# ME461_F28379D.net
KiCad netlist of a schematic drawn in EAGLE
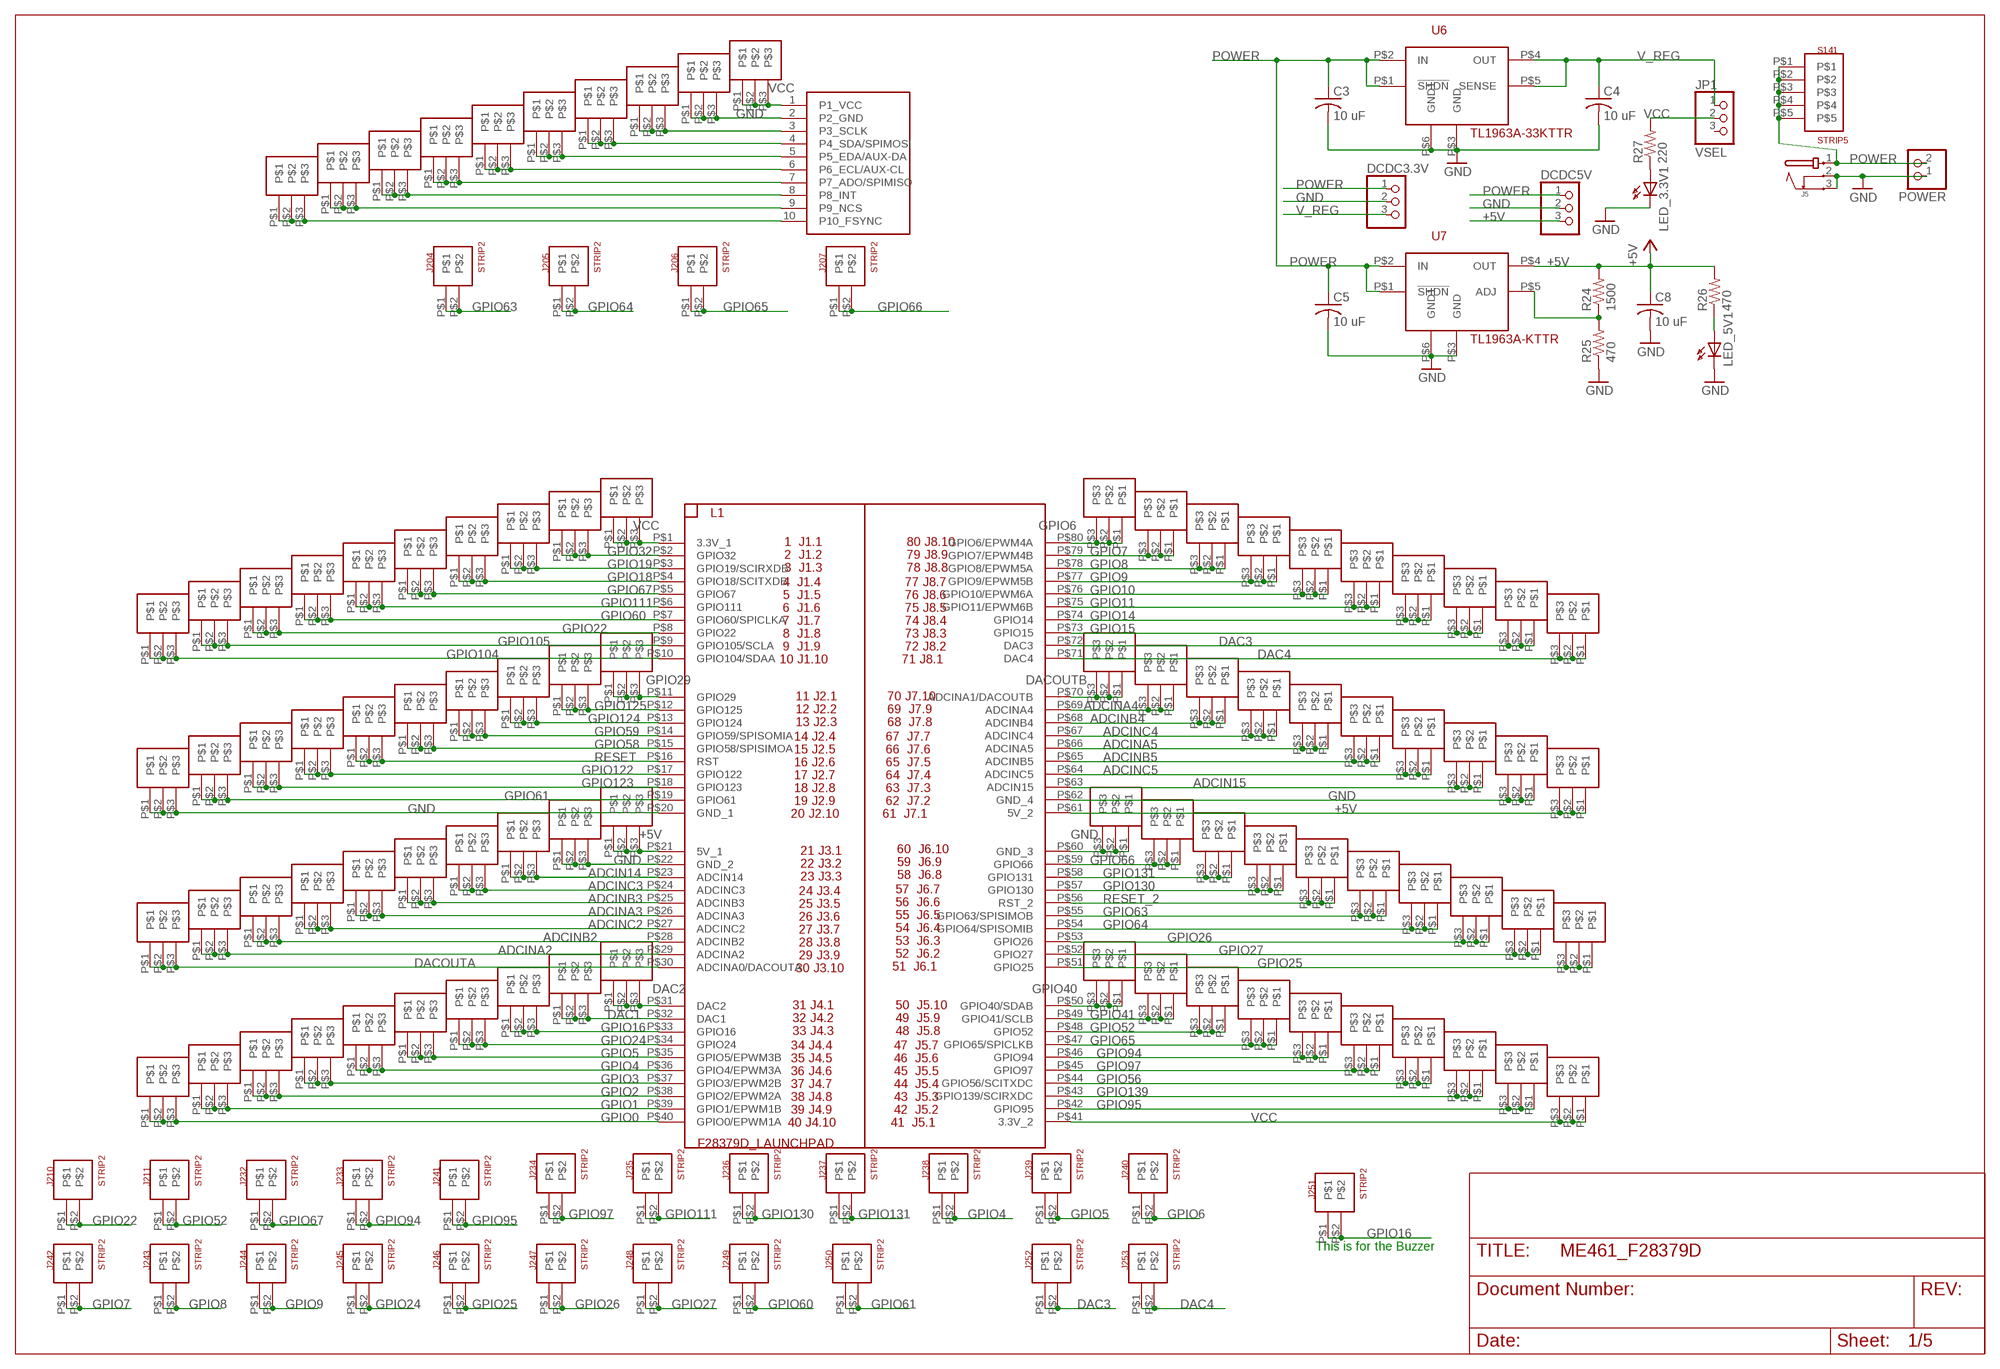
[diagram p0: schematic, sheet 1]
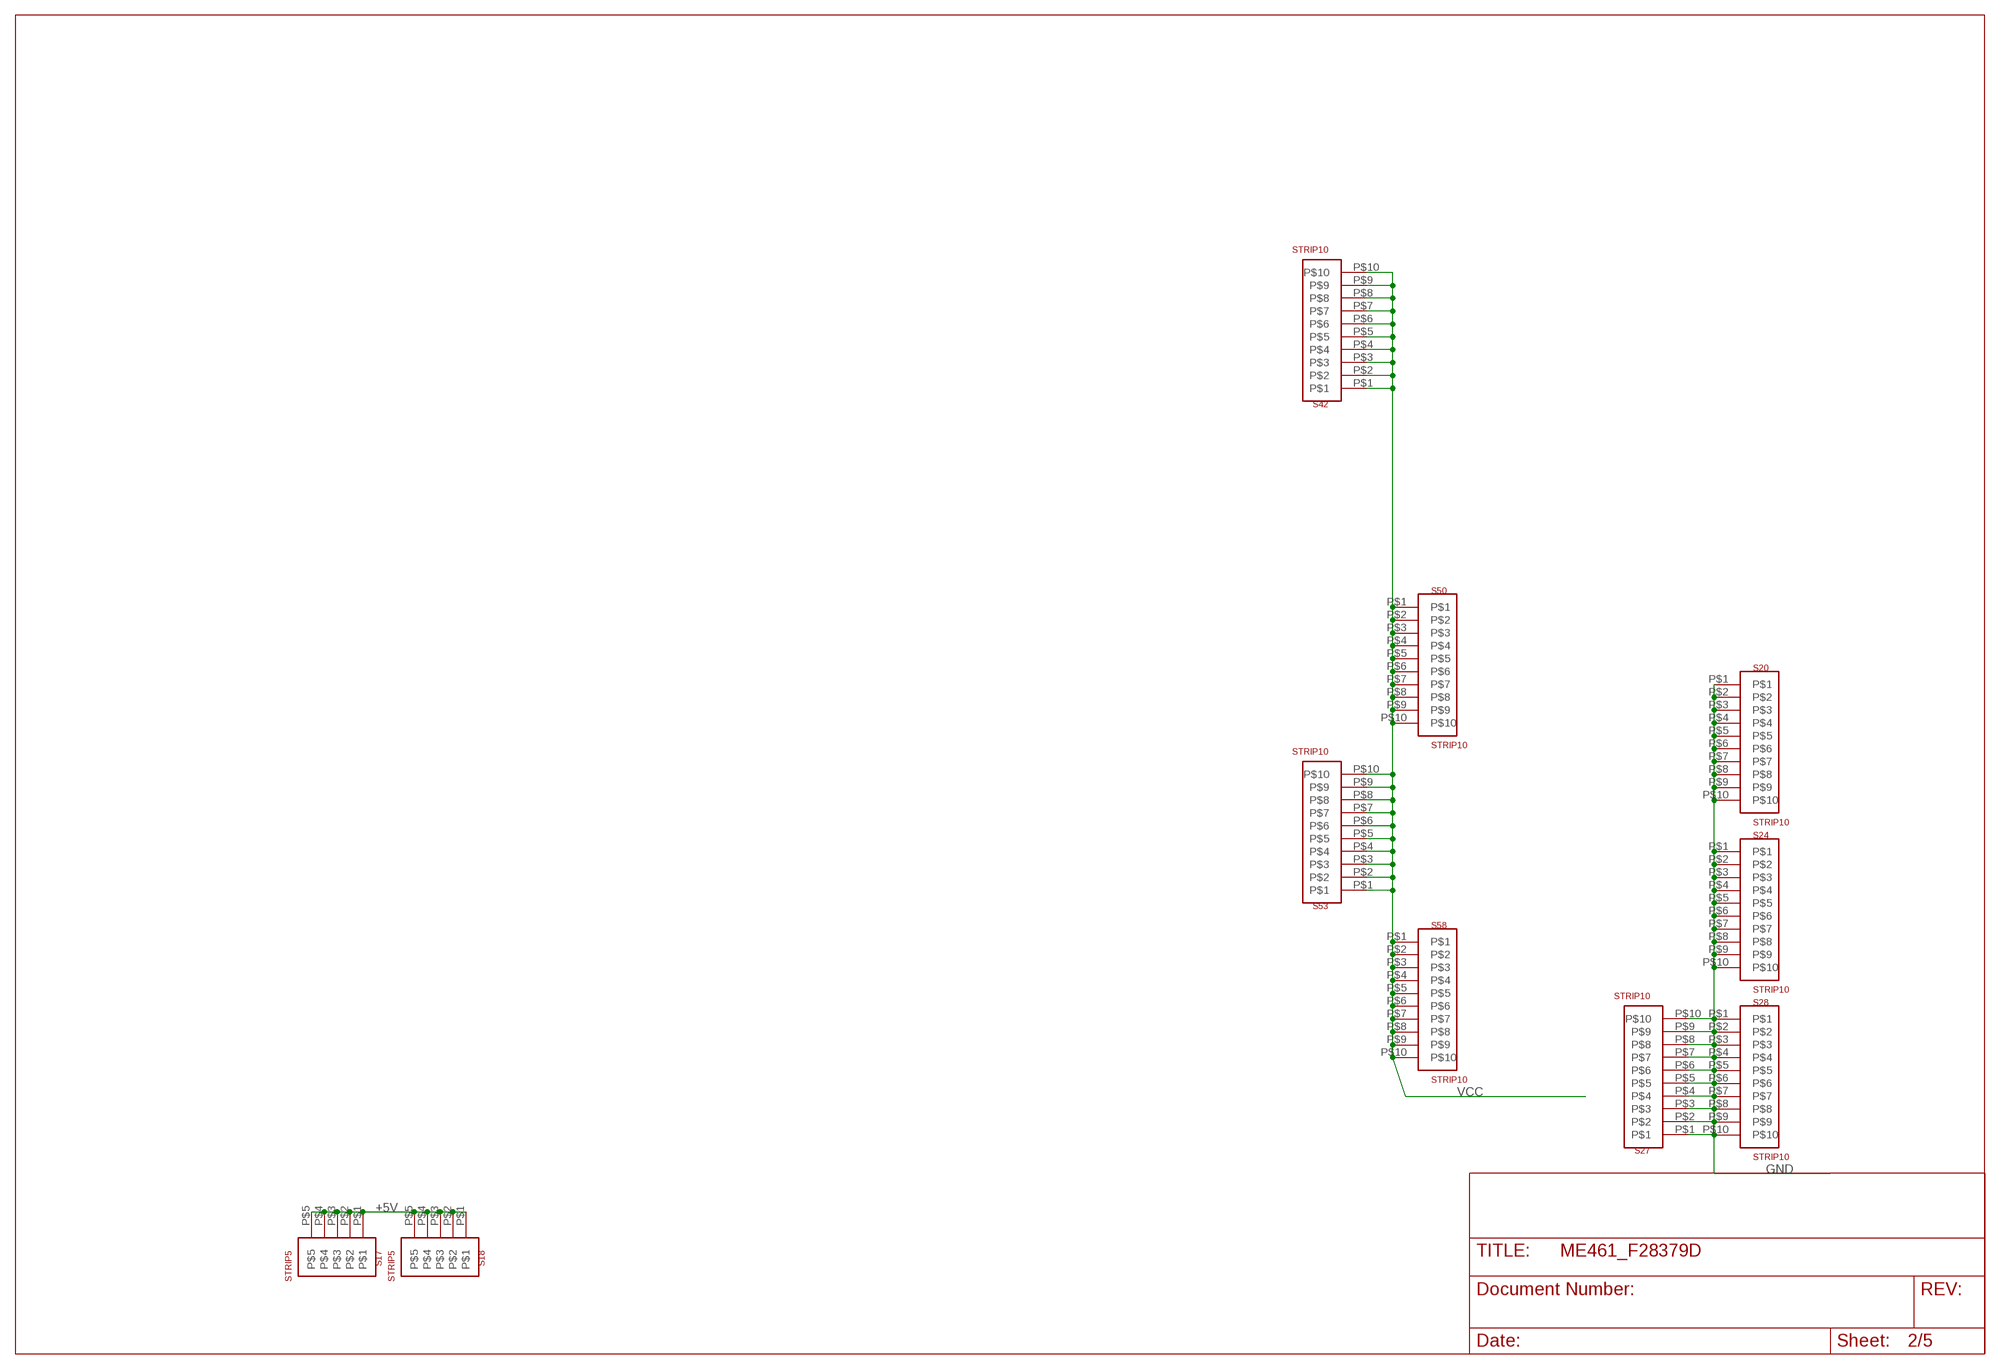
[diagram p1: schematic, sheet 2]
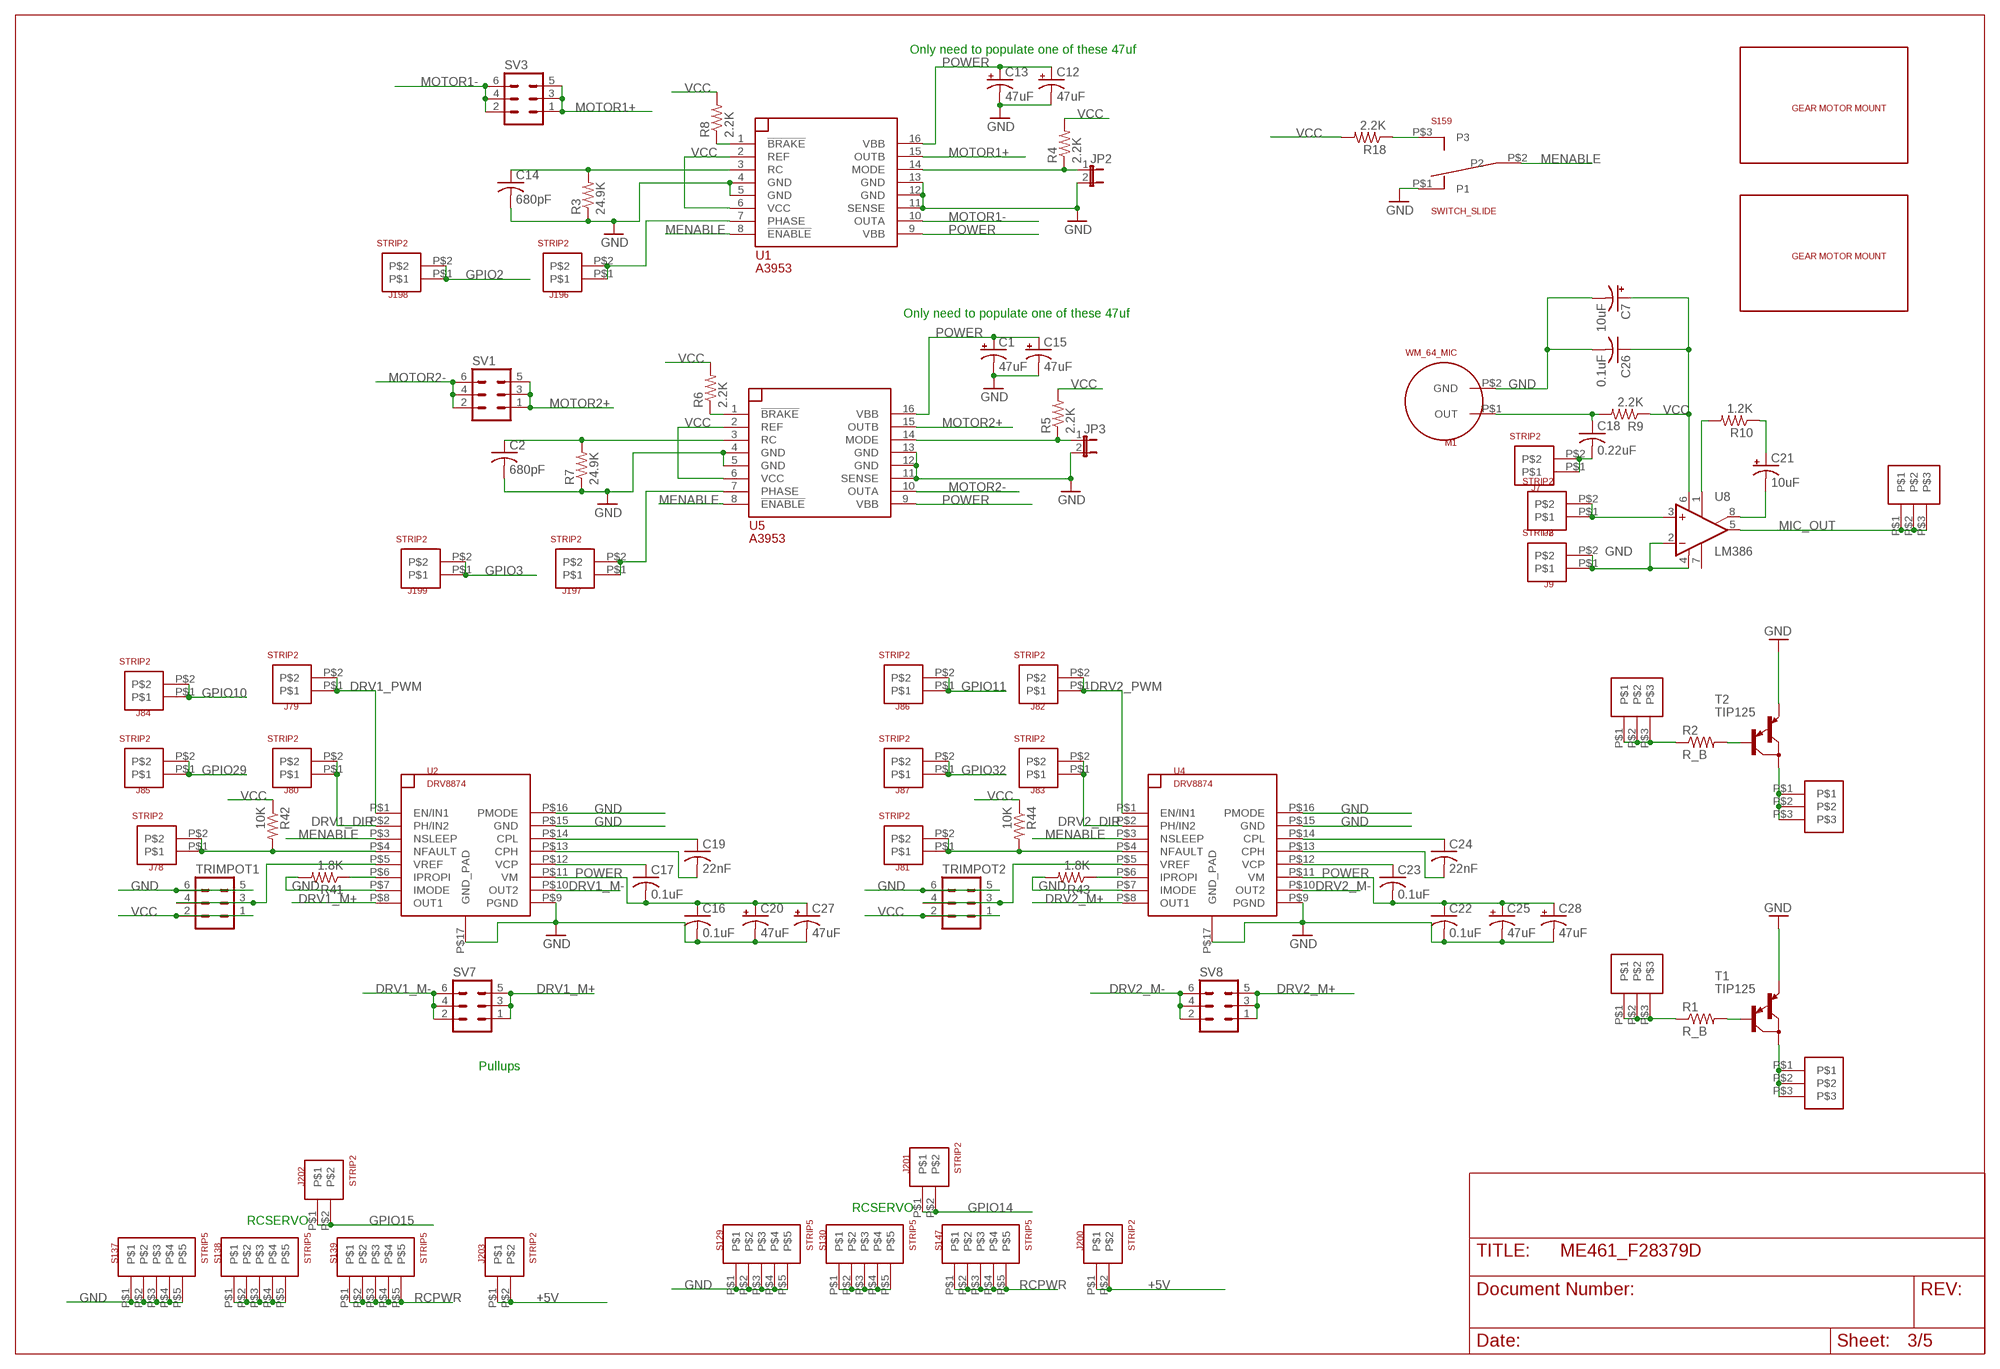
[diagram p2: schematic, sheet 3]
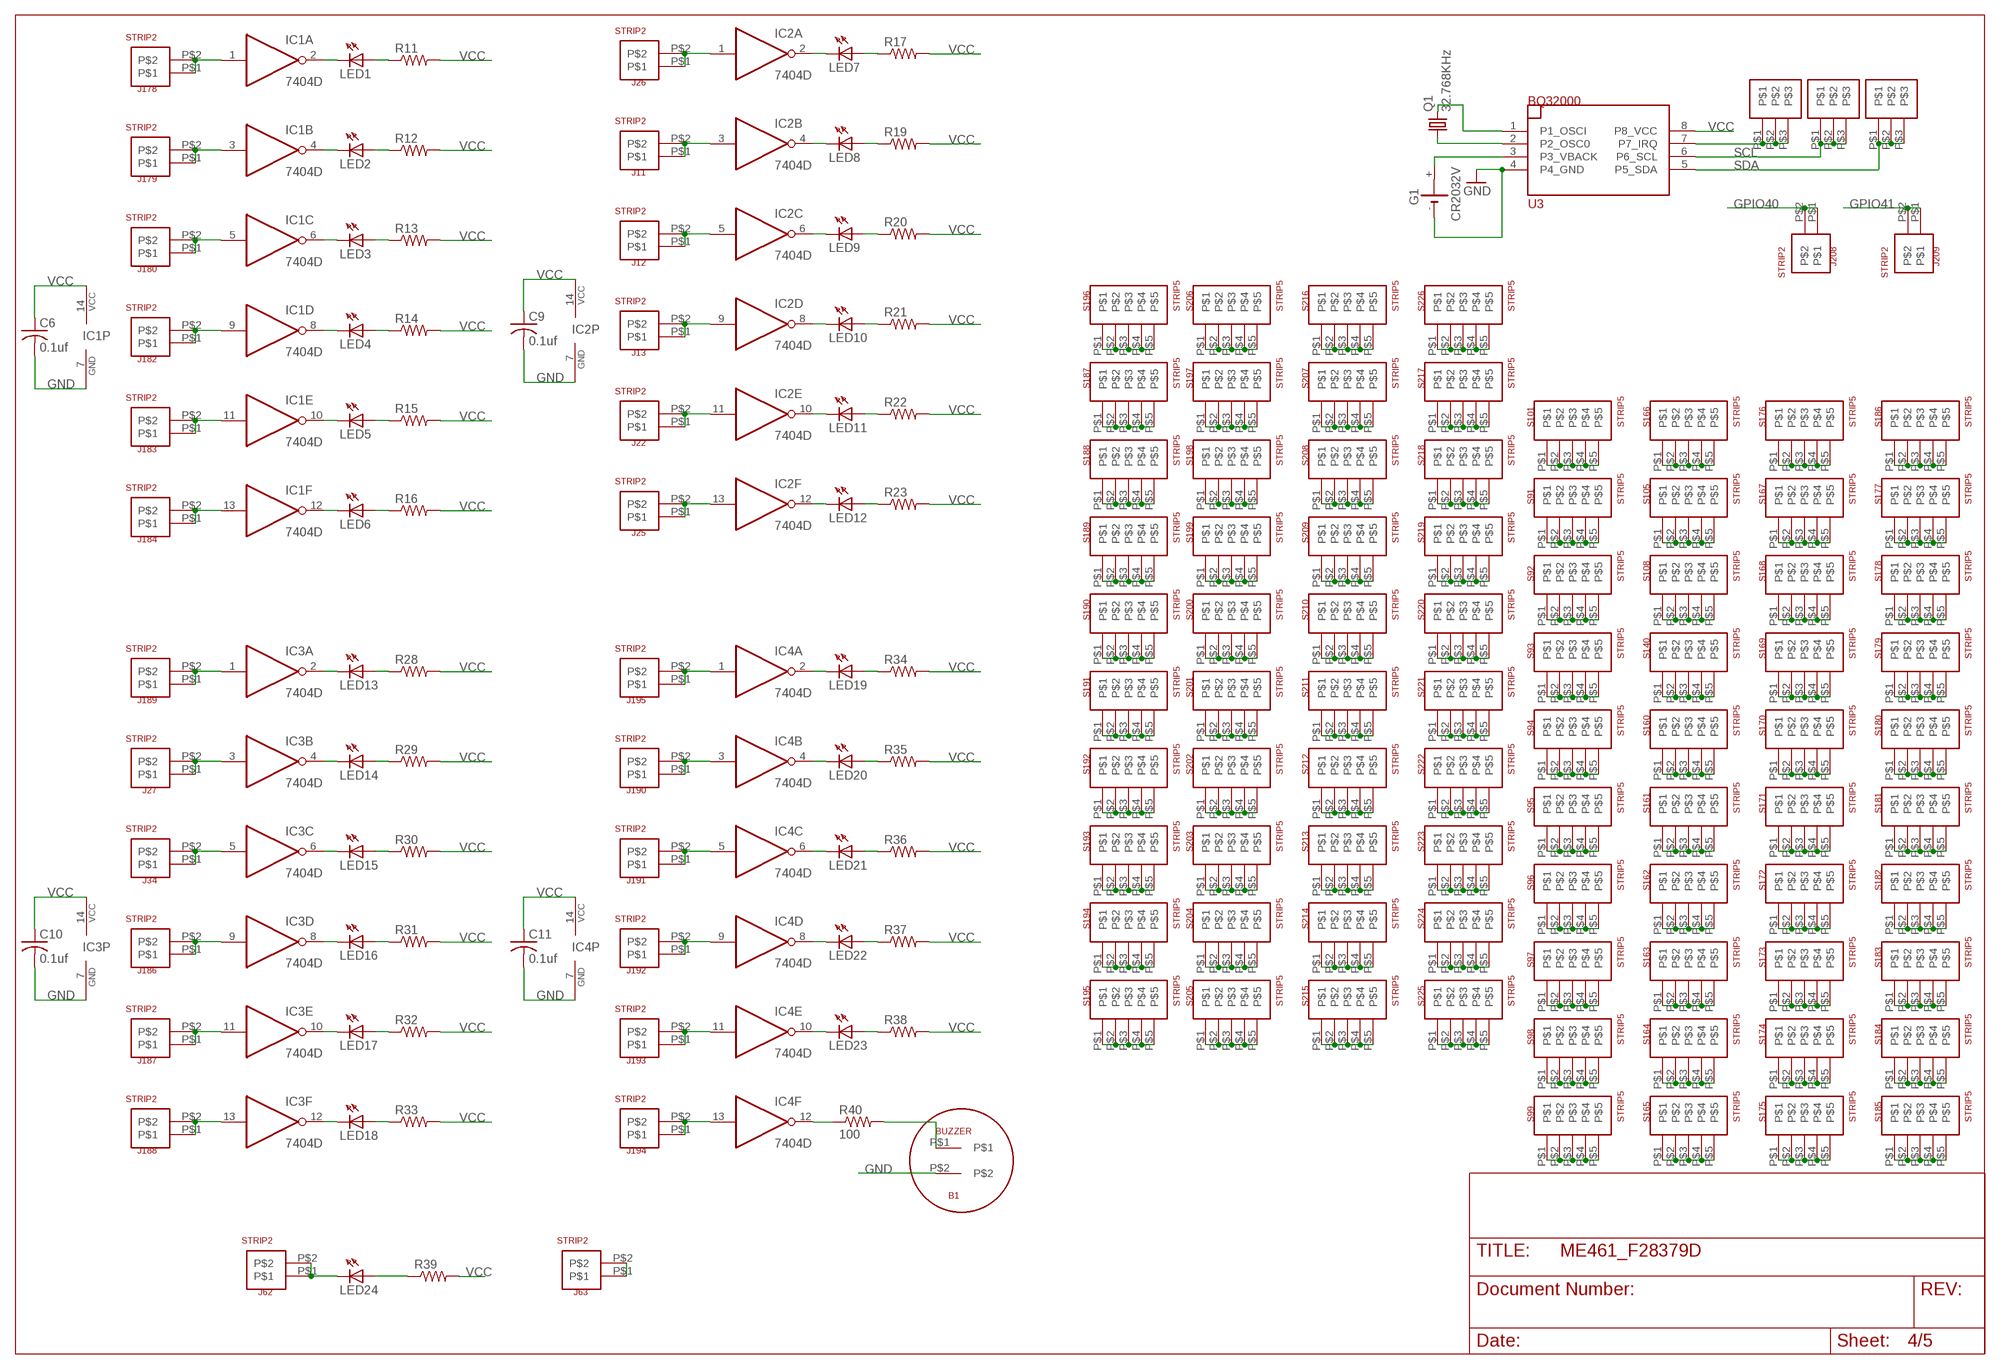
[diagram p3: schematic, sheet 4]
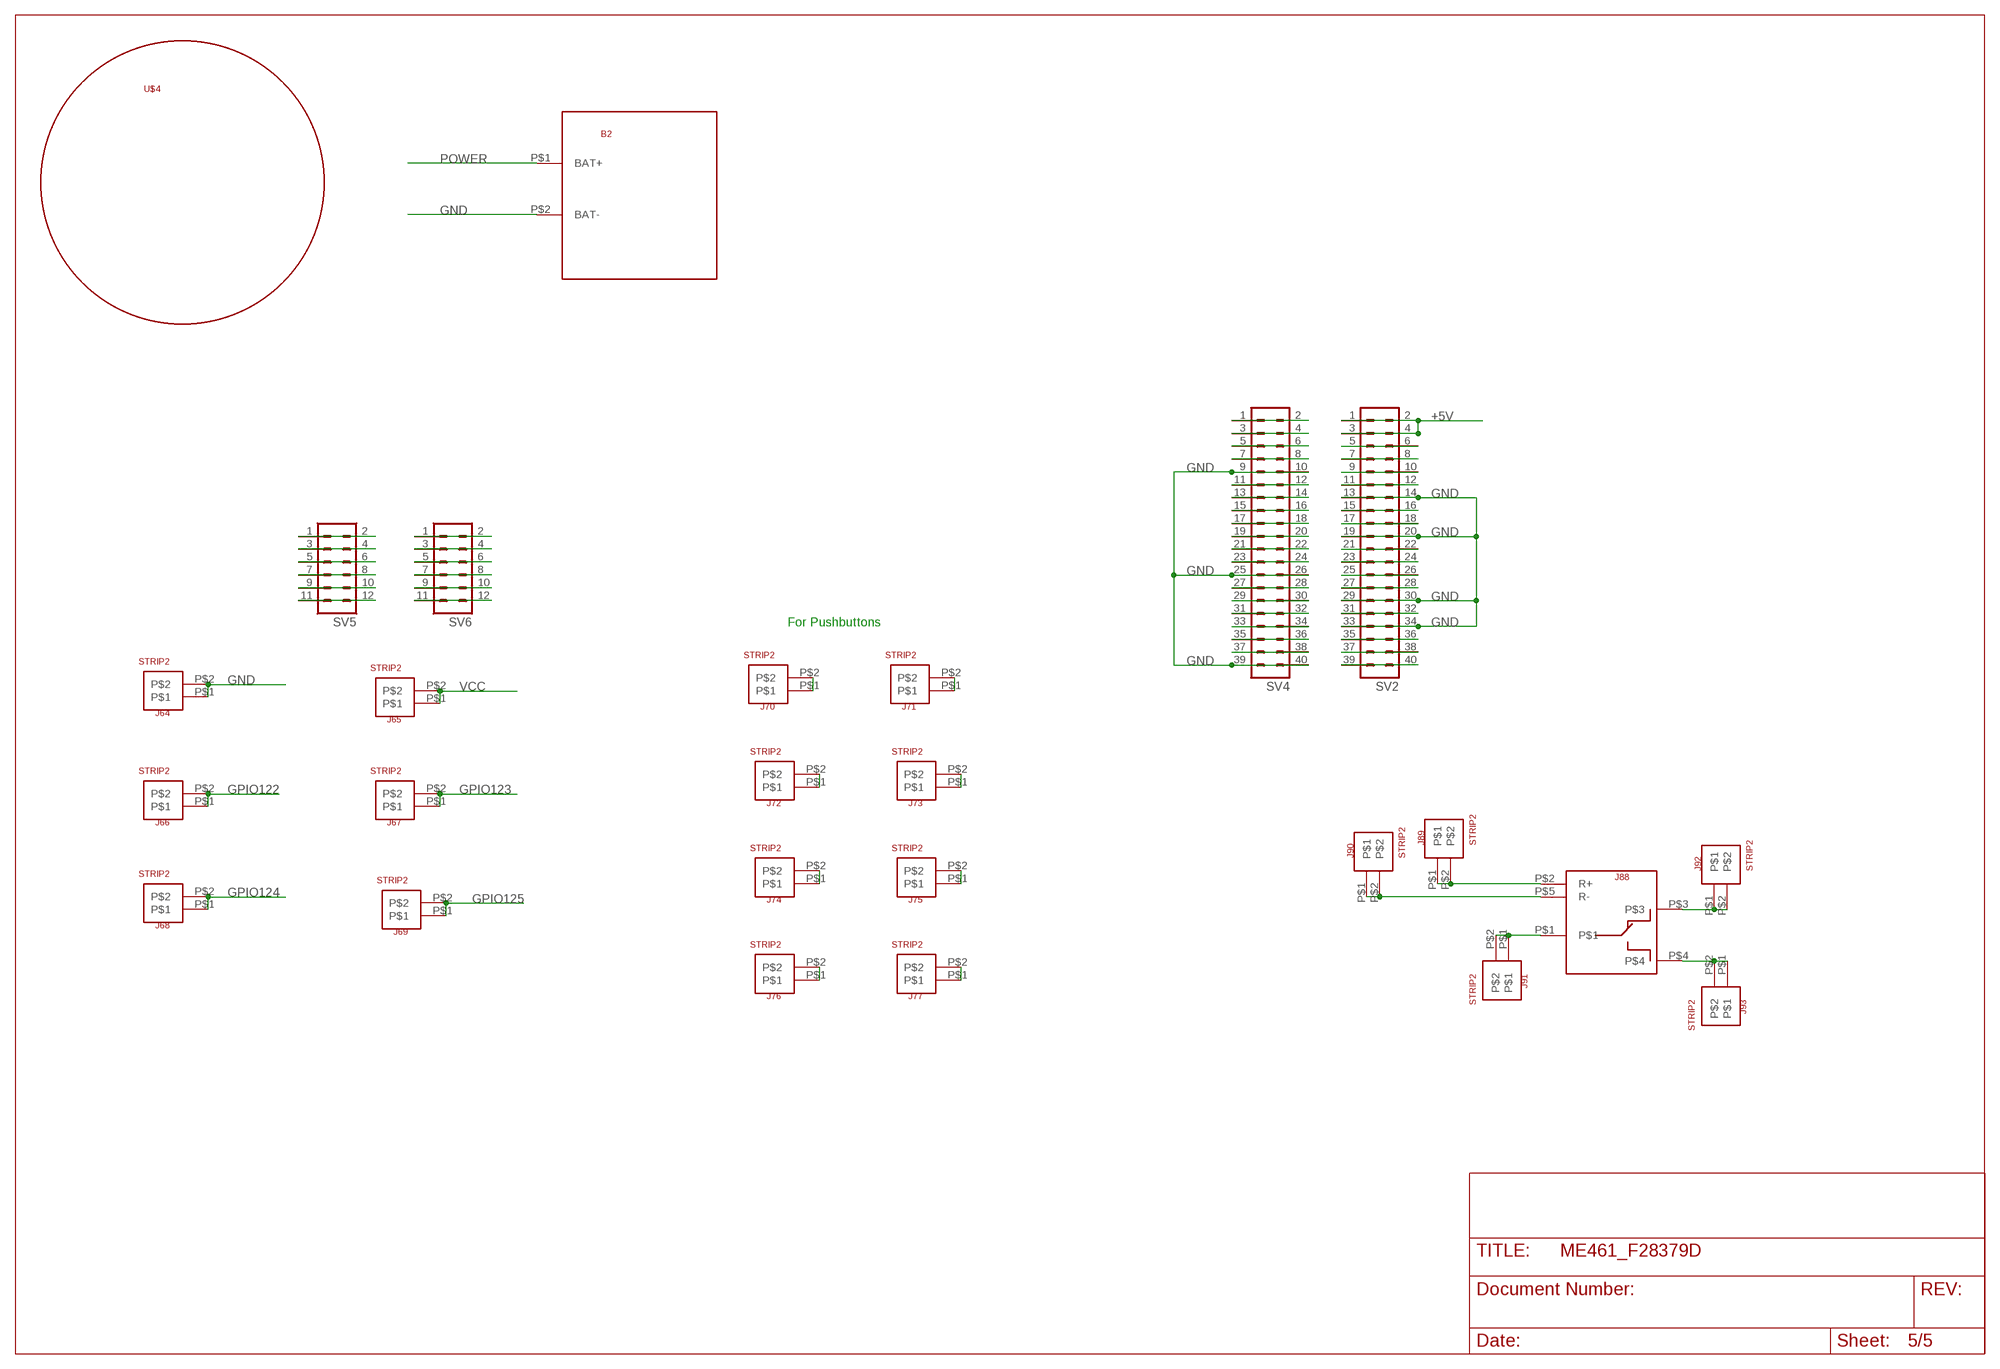
[diagram p4: schematic, sheet 5]

(export (version "E")
  (design (tool "Eeschema 10.0.6"))
  (components
    (comp (ref "B1")
      (value "BUZZER")
      (footprint "eagle-import:BUZZER")
      (libsource (lib "eagle-import") (part "BUZZER"))
    )
    (comp (ref "C6")
      (value "0.1uf")
      (footprint "eagle-import:C1206")
      (libsource (lib "eagle-import") (part "C-USC1206"))
    )
    (comp (ref "C9")
      (value "0.1uf")
      (footprint "eagle-import:C1206")
      (libsource (lib "eagle-import") (part "C-USC1206"))
    )
    (comp (ref "C10")
      (value "0.1uf")
      (footprint "eagle-import:C1206")
      (libsource (lib "eagle-import") (part "C-USC1206"))
    )
    (comp (ref "C11")
      (value "0.1uf")
      (footprint "eagle-import:C1206")
      (libsource (lib "eagle-import") (part "C-USC1206"))
    )
    (comp (ref "G1")
      (value "CR2032V")
      (footprint "eagle-import:CR2032V")
      (libsource (lib "eagle-import") (part "CR2032V"))
    )
    (comp (ref "IC1")
      (value "7404D")
      (footprint "eagle-import:SO14")
      (libsource (lib "eagle-import") (part "7404D"))
    )
    (comp (ref "IC2")
      (value "7404D")
      (footprint "eagle-import:SO14")
      (libsource (lib "eagle-import") (part "7404D"))
    )
    (comp (ref "IC3")
      (value "7404D")
      (footprint "eagle-import:SO14")
      (libsource (lib "eagle-import") (part "7404D"))
    )
    (comp (ref "IC4")
      (value "7404D")
      (footprint "eagle-import:SO14")
      (libsource (lib "eagle-import") (part "7404D"))
    )
    (comp (ref "J1")
      (value "STRIP3")
      (footprint "eagle-import:STRIP3")
      (libsource (lib "eagle-import") (part "STRIP3"))
    )
    (comp (ref "J2")
      (value "STRIP3")
      (footprint "eagle-import:STRIP3")
      (libsource (lib "eagle-import") (part "STRIP3"))
    )
    (comp (ref "J3")
      (value "STRIP3")
      (footprint "eagle-import:STRIP3")
      (libsource (lib "eagle-import") (part "STRIP3"))
    )
    (comp (ref "J11")
      (value "STRIP2")
      (footprint "eagle-import:STRIP2")
      (libsource (lib "eagle-import") (part "STRIP2"))
    )
    (comp (ref "J12")
      (value "STRIP2")
      (footprint "eagle-import:STRIP2")
      (libsource (lib "eagle-import") (part "STRIP2"))
    )
    (comp (ref "J13")
      (value "STRIP2")
      (footprint "eagle-import:STRIP2")
      (libsource (lib "eagle-import") (part "STRIP2"))
    )
    (comp (ref "J22")
      (value "STRIP2")
      (footprint "eagle-import:STRIP2")
      (libsource (lib "eagle-import") (part "STRIP2"))
    )
    (comp (ref "J25")
      (value "STRIP2")
      (footprint "eagle-import:STRIP2")
      (libsource (lib "eagle-import") (part "STRIP2"))
    )
    (comp (ref "J26")
      (value "STRIP2")
      (footprint "eagle-import:STRIP2")
      (libsource (lib "eagle-import") (part "STRIP2"))
    )
    (comp (ref "J27")
      (value "STRIP2")
      (footprint "eagle-import:STRIP2")
      (libsource (lib "eagle-import") (part "STRIP2"))
    )
    (comp (ref "J34")
      (value "STRIP2")
      (footprint "eagle-import:STRIP2")
      (libsource (lib "eagle-import") (part "STRIP2"))
    )
    (comp (ref "J62")
      (value "STRIP2")
      (footprint "eagle-import:STRIP2")
      (libsource (lib "eagle-import") (part "STRIP2"))
    )
    (comp (ref "J63")
      (value "STRIP2")
      (footprint "eagle-import:STRIP2")
      (libsource (lib "eagle-import") (part "STRIP2"))
    )
    (comp (ref "J178")
      (value "STRIP2")
      (footprint "eagle-import:STRIP2")
      (libsource (lib "eagle-import") (part "STRIP2"))
    )
    (comp (ref "J179")
      (value "STRIP2")
      (footprint "eagle-import:STRIP2")
      (libsource (lib "eagle-import") (part "STRIP2"))
    )
    (comp (ref "J180")
      (value "STRIP2")
      (footprint "eagle-import:STRIP2")
      (libsource (lib "eagle-import") (part "STRIP2"))
    )
    (comp (ref "J182")
      (value "STRIP2")
      (footprint "eagle-import:STRIP2")
      (libsource (lib "eagle-import") (part "STRIP2"))
    )
    (comp (ref "J183")
      (value "STRIP2")
      (footprint "eagle-import:STRIP2")
      (libsource (lib "eagle-import") (part "STRIP2"))
    )
    (comp (ref "J184")
      (value "STRIP2")
      (footprint "eagle-import:STRIP2")
      (libsource (lib "eagle-import") (part "STRIP2"))
    )
    (comp (ref "J186")
      (value "STRIP2")
      (footprint "eagle-import:STRIP2")
      (libsource (lib "eagle-import") (part "STRIP2"))
    )
    (comp (ref "J187")
      (value "STRIP2")
      (footprint "eagle-import:STRIP2")
      (libsource (lib "eagle-import") (part "STRIP2"))
    )
    (comp (ref "J188")
      (value "STRIP2")
      (footprint "eagle-import:STRIP2")
      (libsource (lib "eagle-import") (part "STRIP2"))
    )
    (comp (ref "J189")
      (value "STRIP2")
      (footprint "eagle-import:STRIP2")
      (libsource (lib "eagle-import") (part "STRIP2"))
    )
    (comp (ref "J190")
      (value "STRIP2")
      (footprint "eagle-import:STRIP2")
      (libsource (lib "eagle-import") (part "STRIP2"))
    )
    (comp (ref "J191")
      (value "STRIP2")
      (footprint "eagle-import:STRIP2")
      (libsource (lib "eagle-import") (part "STRIP2"))
    )
    (comp (ref "J192")
      (value "STRIP2")
      (footprint "eagle-import:STRIP2")
      (libsource (lib "eagle-import") (part "STRIP2"))
    )
    (comp (ref "J193")
      (value "STRIP2")
      (footprint "eagle-import:STRIP2")
      (libsource (lib "eagle-import") (part "STRIP2"))
    )
    (comp (ref "J194")
      (value "STRIP2")
      (footprint "eagle-import:STRIP2")
      (libsource (lib "eagle-import") (part "STRIP2"))
    )
    (comp (ref "J195")
      (value "STRIP2")
      (footprint "eagle-import:STRIP2")
      (libsource (lib "eagle-import") (part "STRIP2"))
    )
    (comp (ref "J208")
      (value "STRIP2")
      (footprint "eagle-import:STRIP2")
      (libsource (lib "eagle-import") (part "STRIP2"))
    )
    (comp (ref "J209")
      (value "STRIP2")
      (footprint "eagle-import:STRIP2")
      (libsource (lib "eagle-import") (part "STRIP2"))
    )
    (comp (ref "LED1")
      (value "LED3MM")
      (footprint "eagle-import:LED3MM")
      (libsource (lib "eagle-import") (part "LED3MM"))
    )
    (comp (ref "LED2")
      (value "LED3MM")
      (footprint "eagle-import:LED3MM")
      (libsource (lib "eagle-import") (part "LED3MM"))
    )
    (comp (ref "LED3")
      (value "LED3MM")
      (footprint "eagle-import:LED3MM")
      (libsource (lib "eagle-import") (part "LED3MM"))
    )
    (comp (ref "LED4")
      (value "LED3MM")
      (footprint "eagle-import:LED3MM")
      (libsource (lib "eagle-import") (part "LED3MM"))
    )
    (comp (ref "LED5")
      (value "LED3MM")
      (footprint "eagle-import:LED3MM")
      (libsource (lib "eagle-import") (part "LED3MM"))
    )
    (comp (ref "LED6")
      (value "LED3MM")
      (footprint "eagle-import:LED3MM")
      (libsource (lib "eagle-import") (part "LED3MM"))
    )
    (comp (ref "LED7")
      (value "LED3MM")
      (footprint "eagle-import:LED3MM")
      (libsource (lib "eagle-import") (part "LED3MM"))
    )
    (comp (ref "LED8")
      (value "LED3MM")
      (footprint "eagle-import:LED3MM")
      (libsource (lib "eagle-import") (part "LED3MM"))
    )
    (comp (ref "LED9")
      (value "LED3MM")
      (footprint "eagle-import:LED3MM")
      (libsource (lib "eagle-import") (part "LED3MM"))
    )
    (comp (ref "LED10")
      (value "LED3MM")
      (footprint "eagle-import:LED3MM")
      (libsource (lib "eagle-import") (part "LED3MM"))
    )
    (comp (ref "LED11")
      (value "LED3MM")
      (footprint "eagle-import:LED3MM")
      (libsource (lib "eagle-import") (part "LED3MM"))
    )
    (comp (ref "LED12")
      (value "LED3MM")
      (footprint "eagle-import:LED3MM")
      (libsource (lib "eagle-import") (part "LED3MM"))
    )
    (comp (ref "LED13")
      (value "LED3MM")
      (footprint "eagle-import:LED3MM")
      (libsource (lib "eagle-import") (part "LED3MM"))
    )
    (comp (ref "LED14")
      (value "LED3MM")
      (footprint "eagle-import:LED3MM")
      (libsource (lib "eagle-import") (part "LED3MM"))
    )
    (comp (ref "LED15")
      (value "LED3MM")
      (footprint "eagle-import:LED3MM")
      (libsource (lib "eagle-import") (part "LED3MM"))
    )
    (comp (ref "LED16")
      (value "LED3MM")
      (footprint "eagle-import:LED3MM")
      (libsource (lib "eagle-import") (part "LED3MM"))
    )
    (comp (ref "LED17")
      (value "LED3MM")
      (footprint "eagle-import:LED3MM")
      (libsource (lib "eagle-import") (part "LED3MM"))
    )
    (comp (ref "LED18")
      (value "LED3MM")
      (footprint "eagle-import:LED3MM")
      (libsource (lib "eagle-import") (part "LED3MM"))
    )
    (comp (ref "LED19")
      (value "LED3MM")
      (footprint "eagle-import:LED3MM")
      (libsource (lib "eagle-import") (part "LED3MM"))
    )
    (comp (ref "LED20")
      (value "LED3MM")
      (footprint "eagle-import:LED3MM")
      (libsource (lib "eagle-import") (part "LED3MM"))
    )
    (comp (ref "LED21")
      (value "LED3MM")
      (footprint "eagle-import:LED3MM")
      (libsource (lib "eagle-import") (part "LED3MM"))
    )
    (comp (ref "LED22")
      (value "LED3MM")
      (footprint "eagle-import:LED3MM")
      (libsource (lib "eagle-import") (part "LED3MM"))
    )
    (comp (ref "LED23")
      (value "LED3MM")
      (footprint "eagle-import:LED3MM")
      (libsource (lib "eagle-import") (part "LED3MM"))
    )
    (comp (ref "LED24")
      (value "LED3MM")
      (footprint "eagle-import:LED3MM")
      (libsource (lib "eagle-import") (part "LED3MM"))
    )
    (comp (ref "Q1")
      (value "32.768KHz")
      (footprint "eagle-import:TC26H")
      (libsource (lib "eagle-import") (part "CRYTALTC26H"))
    )
    (comp (ref "R11")
      (value "R-US_R1206")
      (footprint "eagle-import:R1206")
      (libsource (lib "eagle-import") (part "R-US_R1206"))
    )
    (comp (ref "R12")
      (value "R-US_R1206")
      (footprint "eagle-import:R1206")
      (libsource (lib "eagle-import") (part "R-US_R1206"))
    )
    (comp (ref "R13")
      (value "R-US_R1206")
      (footprint "eagle-import:R1206")
      (libsource (lib "eagle-import") (part "R-US_R1206"))
    )
    (comp (ref "R14")
      (value "R-US_R1206")
      (footprint "eagle-import:R1206")
      (libsource (lib "eagle-import") (part "R-US_R1206"))
    )
    (comp (ref "R15")
      (value "R-US_R1206")
      (footprint "eagle-import:R1206")
      (libsource (lib "eagle-import") (part "R-US_R1206"))
    )
    (comp (ref "R16")
      (value "R-US_R1206")
      (footprint "eagle-import:R1206")
      (libsource (lib "eagle-import") (part "R-US_R1206"))
    )
    (comp (ref "R17")
      (value "R-US_R1206")
      (footprint "eagle-import:R1206")
      (libsource (lib "eagle-import") (part "R-US_R1206"))
    )
    (comp (ref "R19")
      (value "R-US_R1206")
      (footprint "eagle-import:R1206")
      (libsource (lib "eagle-import") (part "R-US_R1206"))
    )
    (comp (ref "R20")
      (value "R-US_R1206")
      (footprint "eagle-import:R1206")
      (libsource (lib "eagle-import") (part "R-US_R1206"))
    )
    (comp (ref "R21")
      (value "R-US_R1206")
      (footprint "eagle-import:R1206")
      (libsource (lib "eagle-import") (part "R-US_R1206"))
    )
    (comp (ref "R22")
      (value "R-US_R1206")
      (footprint "eagle-import:R1206")
      (libsource (lib "eagle-import") (part "R-US_R1206"))
    )
    (comp (ref "R23")
      (value "R-US_R1206")
      (footprint "eagle-import:R1206")
      (libsource (lib "eagle-import") (part "R-US_R1206"))
    )
    (comp (ref "R28")
      (value "R-US_R1206")
      (footprint "eagle-import:R1206")
      (libsource (lib "eagle-import") (part "R-US_R1206"))
    )
    (comp (ref "R29")
      (value "R-US_R1206")
      (footprint "eagle-import:R1206")
      (libsource (lib "eagle-import") (part "R-US_R1206"))
    )
    (comp (ref "R30")
      (value "R-US_R1206")
      (footprint "eagle-import:R1206")
      (libsource (lib "eagle-import") (part "R-US_R1206"))
    )
    (comp (ref "R31")
      (value "R-US_R1206")
      (footprint "eagle-import:R1206")
      (libsource (lib "eagle-import") (part "R-US_R1206"))
    )
    (comp (ref "R32")
      (value "R-US_R1206")
      (footprint "eagle-import:R1206")
      (libsource (lib "eagle-import") (part "R-US_R1206"))
    )
    (comp (ref "R33")
      (value "R-US_R1206")
      (footprint "eagle-import:R1206")
      (libsource (lib "eagle-import") (part "R-US_R1206"))
    )
    (comp (ref "R34")
      (value "R-US_R1206")
      (footprint "eagle-import:R1206")
      (libsource (lib "eagle-import") (part "R-US_R1206"))
    )
    (comp (ref "R35")
      (value "R-US_R1206")
      (footprint "eagle-import:R1206")
      (libsource (lib "eagle-import") (part "R-US_R1206"))
    )
    (comp (ref "R36")
      (value "R-US_R1206")
      (footprint "eagle-import:R1206")
      (libsource (lib "eagle-import") (part "R-US_R1206"))
    )
    (comp (ref "R37")
      (value "R-US_R1206")
      (footprint "eagle-import:R1206")
      (libsource (lib "eagle-import") (part "R-US_R1206"))
    )
    (comp (ref "R38")
      (value "R-US_R1206")
      (footprint "eagle-import:R1206")
      (libsource (lib "eagle-import") (part "R-US_R1206"))
    )
    (comp (ref "R39")
      (value "R-US_R1206")
      (footprint "eagle-import:R1206")
      (libsource (lib "eagle-import") (part "R-US_R1206"))
    )
    (comp (ref "R40")
      (value "100")
      (footprint "eagle-import:R1206")
      (libsource (lib "eagle-import") (part "R-US_R1206"))
    )
    (comp (ref "S91")
      (value "STRIP5")
      (footprint "eagle-import:STRIP5")
      (libsource (lib "eagle-import") (part "STRIP5"))
    )
    (comp (ref "S92")
      (value "STRIP5")
      (footprint "eagle-import:STRIP5")
      (libsource (lib "eagle-import") (part "STRIP5"))
    )
    (comp (ref "S93")
      (value "STRIP5")
      (footprint "eagle-import:STRIP5")
      (libsource (lib "eagle-import") (part "STRIP5"))
    )
    (comp (ref "S94")
      (value "STRIP5")
      (footprint "eagle-import:STRIP5")
      (libsource (lib "eagle-import") (part "STRIP5"))
    )
    (comp (ref "S95")
      (value "STRIP5")
      (footprint "eagle-import:STRIP5")
      (libsource (lib "eagle-import") (part "STRIP5"))
    )
    (comp (ref "S96")
      (value "STRIP5")
      (footprint "eagle-import:STRIP5")
      (libsource (lib "eagle-import") (part "STRIP5"))
    )
    (comp (ref "S97")
      (value "STRIP5")
      (footprint "eagle-import:STRIP5")
      (libsource (lib "eagle-import") (part "STRIP5"))
    )
    (comp (ref "S98")
      (value "STRIP5")
      (footprint "eagle-import:STRIP5")
      (libsource (lib "eagle-import") (part "STRIP5"))
    )
    (comp (ref "S99")
      (value "STRIP5")
      (footprint "eagle-import:STRIP5")
      (libsource (lib "eagle-import") (part "STRIP5"))
    )
    (comp (ref "S101")
      (value "STRIP5")
      (footprint "eagle-import:STRIP5")
      (libsource (lib "eagle-import") (part "STRIP5"))
    )
    (comp (ref "S105")
      (value "STRIP5")
      (footprint "eagle-import:STRIP5")
      (libsource (lib "eagle-import") (part "STRIP5"))
    )
    (comp (ref "S108")
      (value "STRIP5")
      (footprint "eagle-import:STRIP5")
      (libsource (lib "eagle-import") (part "STRIP5"))
    )
    (comp (ref "S140")
      (value "STRIP5")
      (footprint "eagle-import:STRIP5")
      (libsource (lib "eagle-import") (part "STRIP5"))
    )
    (comp (ref "S160")
      (value "STRIP5")
      (footprint "eagle-import:STRIP5")
      (libsource (lib "eagle-import") (part "STRIP5"))
    )
    (comp (ref "S161")
      (value "STRIP5")
      (footprint "eagle-import:STRIP5")
      (libsource (lib "eagle-import") (part "STRIP5"))
    )
    (comp (ref "S162")
      (value "STRIP5")
      (footprint "eagle-import:STRIP5")
      (libsource (lib "eagle-import") (part "STRIP5"))
    )
    (comp (ref "S163")
      (value "STRIP5")
      (footprint "eagle-import:STRIP5")
      (libsource (lib "eagle-import") (part "STRIP5"))
    )
    (comp (ref "S164")
      (value "STRIP5")
      (footprint "eagle-import:STRIP5")
      (libsource (lib "eagle-import") (part "STRIP5"))
    )
    (comp (ref "S165")
      (value "STRIP5")
      (footprint "eagle-import:STRIP5")
      (libsource (lib "eagle-import") (part "STRIP5"))
    )
    (comp (ref "S166")
      (value "STRIP5")
      (footprint "eagle-import:STRIP5")
      (libsource (lib "eagle-import") (part "STRIP5"))
    )
    (comp (ref "S167")
      (value "STRIP5")
      (footprint "eagle-import:STRIP5")
      (libsource (lib "eagle-import") (part "STRIP5"))
    )
    (comp (ref "S168")
      (value "STRIP5")
      (footprint "eagle-import:STRIP5")
      (libsource (lib "eagle-import") (part "STRIP5"))
    )
    (comp (ref "S169")
      (value "STRIP5")
      (footprint "eagle-import:STRIP5")
      (libsource (lib "eagle-import") (part "STRIP5"))
    )
    (comp (ref "S170")
      (value "STRIP5")
      (footprint "eagle-import:STRIP5")
      (libsource (lib "eagle-import") (part "STRIP5"))
    )
    (comp (ref "S171")
      (value "STRIP5")
      (footprint "eagle-import:STRIP5")
      (libsource (lib "eagle-import") (part "STRIP5"))
    )
    (comp (ref "S172")
      (value "STRIP5")
      (footprint "eagle-import:STRIP5")
      (libsource (lib "eagle-import") (part "STRIP5"))
    )
    (comp (ref "S173")
      (value "STRIP5")
      (footprint "eagle-import:STRIP5")
      (libsource (lib "eagle-import") (part "STRIP5"))
    )
    (comp (ref "S174")
      (value "STRIP5")
      (footprint "eagle-import:STRIP5")
      (libsource (lib "eagle-import") (part "STRIP5"))
    )
    (comp (ref "S175")
      (value "STRIP5")
      (footprint "eagle-import:STRIP5")
      (libsource (lib "eagle-import") (part "STRIP5"))
    )
    (comp (ref "S176")
      (value "STRIP5")
      (footprint "eagle-import:STRIP5")
      (libsource (lib "eagle-import") (part "STRIP5"))
    )
    (comp (ref "S177")
      (value "STRIP5")
      (footprint "eagle-import:STRIP5")
      (libsource (lib "eagle-import") (part "STRIP5"))
    )
    (comp (ref "S178")
      (value "STRIP5")
      (footprint "eagle-import:STRIP5")
      (libsource (lib "eagle-import") (part "STRIP5"))
    )
    (comp (ref "S179")
      (value "STRIP5")
      (footprint "eagle-import:STRIP5")
      (libsource (lib "eagle-import") (part "STRIP5"))
    )
    (comp (ref "S180")
      (value "STRIP5")
      (footprint "eagle-import:STRIP5")
      (libsource (lib "eagle-import") (part "STRIP5"))
    )
    (comp (ref "S181")
      (value "STRIP5")
      (footprint "eagle-import:STRIP5")
      (libsource (lib "eagle-import") (part "STRIP5"))
    )
    (comp (ref "S182")
      (value "STRIP5")
      (footprint "eagle-import:STRIP5")
      (libsource (lib "eagle-import") (part "STRIP5"))
    )
    (comp (ref "S183")
      (value "STRIP5")
      (footprint "eagle-import:STRIP5")
      (libsource (lib "eagle-import") (part "STRIP5"))
    )
    (comp (ref "S184")
      (value "STRIP5")
      (footprint "eagle-import:STRIP5")
      (libsource (lib "eagle-import") (part "STRIP5"))
    )
    (comp (ref "S185")
      (value "STRIP5")
      (footprint "eagle-import:STRIP5")
      (libsource (lib "eagle-import") (part "STRIP5"))
    )
    (comp (ref "S186")
      (value "STRIP5")
      (footprint "eagle-import:STRIP5")
      (libsource (lib "eagle-import") (part "STRIP5"))
    )
    (comp (ref "S187")
      (value "STRIP5")
      (footprint "eagle-import:STRIP5")
      (libsource (lib "eagle-import") (part "STRIP5"))
    )
    (comp (ref "S188")
      (value "STRIP5")
      (footprint "eagle-import:STRIP5")
      (libsource (lib "eagle-import") (part "STRIP5"))
    )
    (comp (ref "S189")
      (value "STRIP5")
      (footprint "eagle-import:STRIP5")
      (libsource (lib "eagle-import") (part "STRIP5"))
    )
    (comp (ref "S190")
      (value "STRIP5")
      (footprint "eagle-import:STRIP5")
      (libsource (lib "eagle-import") (part "STRIP5"))
    )
    (comp (ref "S191")
      (value "STRIP5")
      (footprint "eagle-import:STRIP5")
      (libsource (lib "eagle-import") (part "STRIP5"))
    )
    (comp (ref "S192")
      (value "STRIP5")
      (footprint "eagle-import:STRIP5")
      (libsource (lib "eagle-import") (part "STRIP5"))
    )
    (comp (ref "S193")
      (value "STRIP5")
      (footprint "eagle-import:STRIP5")
      (libsource (lib "eagle-import") (part "STRIP5"))
    )
    (comp (ref "S194")
      (value "STRIP5")
      (footprint "eagle-import:STRIP5")
      (libsource (lib "eagle-import") (part "STRIP5"))
    )
    (comp (ref "S195")
      (value "STRIP5")
      (footprint "eagle-import:STRIP5")
      (libsource (lib "eagle-import") (part "STRIP5"))
    )
    (comp (ref "S196")
      (value "STRIP5")
      (footprint "eagle-import:STRIP5")
      (libsource (lib "eagle-import") (part "STRIP5"))
    )
    (comp (ref "S197")
      (value "STRIP5")
      (footprint "eagle-import:STRIP5")
      (libsource (lib "eagle-import") (part "STRIP5"))
    )
    (comp (ref "S198")
      (value "STRIP5")
      (footprint "eagle-import:STRIP5")
      (libsource (lib "eagle-import") (part "STRIP5"))
    )
    (comp (ref "S199")
      (value "STRIP5")
      (footprint "eagle-import:STRIP5")
      (libsource (lib "eagle-import") (part "STRIP5"))
    )
    (comp (ref "S200")
      (value "STRIP5")
      (footprint "eagle-import:STRIP5")
      (libsource (lib "eagle-import") (part "STRIP5"))
    )
    (comp (ref "S201")
      (value "STRIP5")
      (footprint "eagle-import:STRIP5")
      (libsource (lib "eagle-import") (part "STRIP5"))
    )
    (comp (ref "S202")
      (value "STRIP5")
      (footprint "eagle-import:STRIP5")
      (libsource (lib "eagle-import") (part "STRIP5"))
    )
    (comp (ref "S203")
      (value "STRIP5")
      (footprint "eagle-import:STRIP5")
      (libsource (lib "eagle-import") (part "STRIP5"))
    )
    (comp (ref "S204")
      (value "STRIP5")
      (footprint "eagle-import:STRIP5")
      (libsource (lib "eagle-import") (part "STRIP5"))
    )
    (comp (ref "S205")
      (value "STRIP5")
      (footprint "eagle-import:STRIP5")
      (libsource (lib "eagle-import") (part "STRIP5"))
    )
    (comp (ref "S206")
      (value "STRIP5")
      (footprint "eagle-import:STRIP5")
      (libsource (lib "eagle-import") (part "STRIP5"))
    )
    (comp (ref "S207")
      (value "STRIP5")
      (footprint "eagle-import:STRIP5")
      (libsource (lib "eagle-import") (part "STRIP5"))
    )
    (comp (ref "S208")
      (value "STRIP5")
      (footprint "eagle-import:STRIP5")
      (libsource (lib "eagle-import") (part "STRIP5"))
    )
    (comp (ref "S209")
      (value "STRIP5")
      (footprint "eagle-import:STRIP5")
      (libsource (lib "eagle-import") (part "STRIP5"))
    )
    (comp (ref "S210")
      (value "STRIP5")
      (footprint "eagle-import:STRIP5")
      (libsource (lib "eagle-import") (part "STRIP5"))
    )
    (comp (ref "S211")
      (value "STRIP5")
      (footprint "eagle-import:STRIP5")
      (libsource (lib "eagle-import") (part "STRIP5"))
    )
    (comp (ref "S212")
      (value "STRIP5")
      (footprint "eagle-import:STRIP5")
      (libsource (lib "eagle-import") (part "STRIP5"))
    )
    (comp (ref "S213")
      (value "STRIP5")
      (footprint "eagle-import:STRIP5")
      (libsource (lib "eagle-import") (part "STRIP5"))
    )
    (comp (ref "S214")
      (value "STRIP5")
      (footprint "eagle-import:STRIP5")
      (libsource (lib "eagle-import") (part "STRIP5"))
    )
    (comp (ref "S215")
      (value "STRIP5")
      (footprint "eagle-import:STRIP5")
      (libsource (lib "eagle-import") (part "STRIP5"))
    )
    (comp (ref "S216")
      (value "STRIP5")
      (footprint "eagle-import:STRIP5")
      (libsource (lib "eagle-import") (part "STRIP5"))
    )
    (comp (ref "S217")
      (value "STRIP5")
      (footprint "eagle-import:STRIP5")
      (libsource (lib "eagle-import") (part "STRIP5"))
    )
    (comp (ref "S218")
      (value "STRIP5")
      (footprint "eagle-import:STRIP5")
      (libsource (lib "eagle-import") (part "STRIP5"))
    )
    (comp (ref "S219")
      (value "STRIP5")
      (footprint "eagle-import:STRIP5")
      (libsource (lib "eagle-import") (part "STRIP5"))
    )
    (comp (ref "S220")
      (value "STRIP5")
      (footprint "eagle-import:STRIP5")
      (libsource (lib "eagle-import") (part "STRIP5"))
    )
    (comp (ref "S221")
      (value "STRIP5")
      (footprint "eagle-import:STRIP5")
      (libsource (lib "eagle-import") (part "STRIP5"))
    )
    (comp (ref "S222")
      (value "STRIP5")
      (footprint "eagle-import:STRIP5")
      (libsource (lib "eagle-import") (part "STRIP5"))
    )
    (comp (ref "S223")
      (value "STRIP5")
      (footprint "eagle-import:STRIP5")
      (libsource (lib "eagle-import") (part "STRIP5"))
    )
    (comp (ref "S224")
      (value "STRIP5")
      (footprint "eagle-import:STRIP5")
      (libsource (lib "eagle-import") (part "STRIP5"))
    )
    (comp (ref "S225")
      (value "STRIP5")
      (footprint "eagle-import:STRIP5")
      (libsource (lib "eagle-import") (part "STRIP5"))
    )
    (comp (ref "S226")
      (value "STRIP5")
      (footprint "eagle-import:STRIP5")
      (libsource (lib "eagle-import") (part "STRIP5"))
    )
    (comp (ref "U3")
      (value "BQ32000")
      (footprint "eagle-import:SO08")
      (libsource (lib "eagle-import") (part "BQ32000"))
    )
    (comp (ref "C3")
      (value "10 uF")
      (footprint "eagle-import:C1206")
      (libsource (lib "eagle-import") (part "C-USC1206"))
    )
    (comp (ref "C4")
      (value "10 uF")
      (footprint "eagle-import:C1206")
      (libsource (lib "eagle-import") (part "C-USC1206"))
    )
    (comp (ref "C5")
      (value "10 uF")
      (footprint "eagle-import:C1206")
      (libsource (lib "eagle-import") (part "C-USC1206"))
    )
    (comp (ref "C8")
      (value "10 uF")
      (footprint "eagle-import:C1206")
      (libsource (lib "eagle-import") (part "C-USC1206"))
    )
    (comp (ref "DCDC3.3V")
      (value "PINHD-1X3")
      (footprint "eagle-import:1X03")
      (libsource (lib "eagle-import") (part "PINHD-1X3"))
    )
    (comp (ref "DCDC5V")
      (value "PINHD-1X3")
      (footprint "eagle-import:1X03")
      (libsource (lib "eagle-import") (part "PINHD-1X3"))
    )
    (comp (ref "J5")
      (value "JACK-PMS")
      (footprint "eagle-import:JACK-PMS")
      (libsource (lib "eagle-import") (part "JACK-PMS"))
    )
    (comp (ref "J10")
      (value "STRIP3")
      (footprint "eagle-import:STRIP3")
      (libsource (lib "eagle-import") (part "STRIP3"))
    )
    (comp (ref "J14")
      (value "STRIP3")
      (footprint "eagle-import:STRIP3")
      (libsource (lib "eagle-import") (part "STRIP3"))
    )
    (comp (ref "J15")
      (value "STRIP3")
      (footprint "eagle-import:STRIP3")
      (libsource (lib "eagle-import") (part "STRIP3"))
    )
    (comp (ref "J16")
      (value "STRIP3")
      (footprint "eagle-import:STRIP3")
      (libsource (lib "eagle-import") (part "STRIP3"))
    )
    (comp (ref "J17")
      (value "STRIP3")
      (footprint "eagle-import:STRIP3")
      (libsource (lib "eagle-import") (part "STRIP3"))
    )
    (comp (ref "J18")
      (value "STRIP3")
      (footprint "eagle-import:STRIP3")
      (libsource (lib "eagle-import") (part "STRIP3"))
    )
    (comp (ref "J19")
      (value "STRIP3")
      (footprint "eagle-import:STRIP3")
      (libsource (lib "eagle-import") (part "STRIP3"))
    )
    (comp (ref "J20")
      (value "STRIP3")
      (footprint "eagle-import:STRIP3")
      (libsource (lib "eagle-import") (part "STRIP3"))
    )
    (comp (ref "J21")
      (value "STRIP3")
      (footprint "eagle-import:STRIP3")
      (libsource (lib "eagle-import") (part "STRIP3"))
    )
    (comp (ref "J28")
      (value "STRIP3")
      (footprint "eagle-import:STRIP3")
      (libsource (lib "eagle-import") (part "STRIP3"))
    )
    (comp (ref "J29")
      (value "STRIP3")
      (footprint "eagle-import:STRIP3")
      (libsource (lib "eagle-import") (part "STRIP3"))
    )
    (comp (ref "J30")
      (value "STRIP3")
      (footprint "eagle-import:STRIP3")
      (libsource (lib "eagle-import") (part "STRIP3"))
    )
    (comp (ref "J31")
      (value "STRIP3")
      (footprint "eagle-import:STRIP3")
      (libsource (lib "eagle-import") (part "STRIP3"))
    )
    (comp (ref "J32")
      (value "STRIP3")
      (footprint "eagle-import:STRIP3")
      (libsource (lib "eagle-import") (part "STRIP3"))
    )
    (comp (ref "J33")
      (value "STRIP3")
      (footprint "eagle-import:STRIP3")
      (libsource (lib "eagle-import") (part "STRIP3"))
    )
    (comp (ref "J98")
      (value "STRIP3")
      (footprint "eagle-import:STRIP3")
      (libsource (lib "eagle-import") (part "STRIP3"))
    )
    (comp (ref "J99")
      (value "STRIP3")
      (footprint "eagle-import:STRIP3")
      (libsource (lib "eagle-import") (part "STRIP3"))
    )
    (comp (ref "J100")
      (value "STRIP3")
      (footprint "eagle-import:STRIP3")
      (libsource (lib "eagle-import") (part "STRIP3"))
    )
    (comp (ref "J101")
      (value "STRIP3")
      (footprint "eagle-import:STRIP3")
      (libsource (lib "eagle-import") (part "STRIP3"))
    )
    (comp (ref "J102")
      (value "STRIP3")
      (footprint "eagle-import:STRIP3")
      (libsource (lib "eagle-import") (part "STRIP3"))
    )
    (comp (ref "J103")
      (value "STRIP3")
      (footprint "eagle-import:STRIP3")
      (libsource (lib "eagle-import") (part "STRIP3"))
    )
    (comp (ref "J104")
      (value "STRIP3")
      (footprint "eagle-import:STRIP3")
      (libsource (lib "eagle-import") (part "STRIP3"))
    )
    (comp (ref "J105")
      (value "STRIP3")
      (footprint "eagle-import:STRIP3")
      (libsource (lib "eagle-import") (part "STRIP3"))
    )
    (comp (ref "J106")
      (value "STRIP3")
      (footprint "eagle-import:STRIP3")
      (libsource (lib "eagle-import") (part "STRIP3"))
    )
    (comp (ref "J107")
      (value "STRIP3")
      (footprint "eagle-import:STRIP3")
      (libsource (lib "eagle-import") (part "STRIP3"))
    )
    (comp (ref "J108")
      (value "STRIP3")
      (footprint "eagle-import:STRIP3")
      (libsource (lib "eagle-import") (part "STRIP3"))
    )
    (comp (ref "J109")
      (value "STRIP3")
      (footprint "eagle-import:STRIP3")
      (libsource (lib "eagle-import") (part "STRIP3"))
    )
    (comp (ref "J110")
      (value "STRIP3")
      (footprint "eagle-import:STRIP3")
      (libsource (lib "eagle-import") (part "STRIP3"))
    )
    (comp (ref "J111")
      (value "STRIP3")
      (footprint "eagle-import:STRIP3")
      (libsource (lib "eagle-import") (part "STRIP3"))
    )
    (comp (ref "J112")
      (value "STRIP3")
      (footprint "eagle-import:STRIP3")
      (libsource (lib "eagle-import") (part "STRIP3"))
    )
    (comp (ref "J113")
      (value "STRIP3")
      (footprint "eagle-import:STRIP3")
      (libsource (lib "eagle-import") (part "STRIP3"))
    )
    (comp (ref "J114")
      (value "STRIP3")
      (footprint "eagle-import:STRIP3")
      (libsource (lib "eagle-import") (part "STRIP3"))
    )
    (comp (ref "J115")
      (value "STRIP3")
      (footprint "eagle-import:STRIP3")
      (libsource (lib "eagle-import") (part "STRIP3"))
    )
    (comp (ref "J116")
      (value "STRIP3")
      (footprint "eagle-import:STRIP3")
      (libsource (lib "eagle-import") (part "STRIP3"))
    )
    (comp (ref "J117")
      (value "STRIP3")
      (footprint "eagle-import:STRIP3")
      (libsource (lib "eagle-import") (part "STRIP3"))
    )
    (comp (ref "J118")
      (value "STRIP3")
      (footprint "eagle-import:STRIP3")
      (libsource (lib "eagle-import") (part "STRIP3"))
    )
    (comp (ref "J119")
      (value "STRIP3")
      (footprint "eagle-import:STRIP3")
      (libsource (lib "eagle-import") (part "STRIP3"))
    )
    (comp (ref "J120")
      (value "STRIP3")
      (footprint "eagle-import:STRIP3")
      (libsource (lib "eagle-import") (part "STRIP3"))
    )
    (comp (ref "J121")
      (value "STRIP3")
      (footprint "eagle-import:STRIP3")
      (libsource (lib "eagle-import") (part "STRIP3"))
    )
    (comp (ref "J122")
      (value "STRIP3")
      (footprint "eagle-import:STRIP3")
      (libsource (lib "eagle-import") (part "STRIP3"))
    )
    (comp (ref "J123")
      (value "STRIP3")
      (footprint "eagle-import:STRIP3")
      (libsource (lib "eagle-import") (part "STRIP3"))
    )
    (comp (ref "J124")
      (value "STRIP3")
      (footprint "eagle-import:STRIP3")
      (libsource (lib "eagle-import") (part "STRIP3"))
    )
    (comp (ref "J125")
      (value "STRIP3")
      (footprint "eagle-import:STRIP3")
      (libsource (lib "eagle-import") (part "STRIP3"))
    )
    (comp (ref "J126")
      (value "STRIP3")
      (footprint "eagle-import:STRIP3")
      (libsource (lib "eagle-import") (part "STRIP3"))
    )
    (comp (ref "J127")
      (value "STRIP3")
      (footprint "eagle-import:STRIP3")
      (libsource (lib "eagle-import") (part "STRIP3"))
    )
    (comp (ref "J128")
      (value "STRIP3")
      (footprint "eagle-import:STRIP3")
      (libsource (lib "eagle-import") (part "STRIP3"))
    )
    (comp (ref "J129")
      (value "STRIP3")
      (footprint "eagle-import:STRIP3")
      (libsource (lib "eagle-import") (part "STRIP3"))
    )
    (comp (ref "J130")
      (value "STRIP3")
      (footprint "eagle-import:STRIP3")
      (libsource (lib "eagle-import") (part "STRIP3"))
    )
    (comp (ref "J131")
      (value "STRIP3")
      (footprint "eagle-import:STRIP3")
      (libsource (lib "eagle-import") (part "STRIP3"))
    )
    (comp (ref "J132")
      (value "STRIP3")
      (footprint "eagle-import:STRIP3")
      (libsource (lib "eagle-import") (part "STRIP3"))
    )
    (comp (ref "J133")
      (value "STRIP3")
      (footprint "eagle-import:STRIP3")
      (libsource (lib "eagle-import") (part "STRIP3"))
    )
    (comp (ref "J134")
      (value "STRIP3")
      (footprint "eagle-import:STRIP3")
      (libsource (lib "eagle-import") (part "STRIP3"))
    )
    (comp (ref "J135")
      (value "STRIP3")
      (footprint "eagle-import:STRIP3")
      (libsource (lib "eagle-import") (part "STRIP3"))
    )
    (comp (ref "J136")
      (value "STRIP3")
      (footprint "eagle-import:STRIP3")
      (libsource (lib "eagle-import") (part "STRIP3"))
    )
    (comp (ref "J137")
      (value "STRIP3")
      (footprint "eagle-import:STRIP3")
      (libsource (lib "eagle-import") (part "STRIP3"))
    )
    (comp (ref "J138")
      (value "STRIP3")
      (footprint "eagle-import:STRIP3")
      (libsource (lib "eagle-import") (part "STRIP3"))
    )
    (comp (ref "J139")
      (value "STRIP3")
      (footprint "eagle-import:STRIP3")
      (libsource (lib "eagle-import") (part "STRIP3"))
    )
    (comp (ref "J140")
      (value "STRIP3")
      (footprint "eagle-import:STRIP3")
      (libsource (lib "eagle-import") (part "STRIP3"))
    )
    (comp (ref "J141")
      (value "STRIP3")
      (footprint "eagle-import:STRIP3")
      (libsource (lib "eagle-import") (part "STRIP3"))
    )
    (comp (ref "J142")
      (value "STRIP3")
      (footprint "eagle-import:STRIP3")
      (libsource (lib "eagle-import") (part "STRIP3"))
    )
    (comp (ref "J143")
      (value "STRIP3")
      (footprint "eagle-import:STRIP3")
      (libsource (lib "eagle-import") (part "STRIP3"))
    )
    (comp (ref "J144")
      (value "STRIP3")
      (footprint "eagle-import:STRIP3")
      (libsource (lib "eagle-import") (part "STRIP3"))
    )
    (comp (ref "J145")
      (value "STRIP3")
      (footprint "eagle-import:STRIP3")
      (libsource (lib "eagle-import") (part "STRIP3"))
    )
    (comp (ref "J146")
      (value "STRIP3")
      (footprint "eagle-import:STRIP3")
      (libsource (lib "eagle-import") (part "STRIP3"))
    )
    (comp (ref "J147")
      (value "STRIP3")
      (footprint "eagle-import:STRIP3")
      (libsource (lib "eagle-import") (part "STRIP3"))
    )
    (comp (ref "J148")
      (value "STRIP3")
      (footprint "eagle-import:STRIP3")
      (libsource (lib "eagle-import") (part "STRIP3"))
    )
    (comp (ref "J149")
      (value "STRIP3")
      (footprint "eagle-import:STRIP3")
      (libsource (lib "eagle-import") (part "STRIP3"))
    )
    (comp (ref "J150")
      (value "STRIP3")
      (footprint "eagle-import:STRIP3")
      (libsource (lib "eagle-import") (part "STRIP3"))
    )
    (comp (ref "J151")
      (value "STRIP3")
      (footprint "eagle-import:STRIP3")
      (libsource (lib "eagle-import") (part "STRIP3"))
    )
    (comp (ref "J152")
      (value "STRIP3")
      (footprint "eagle-import:STRIP3")
      (libsource (lib "eagle-import") (part "STRIP3"))
    )
    (comp (ref "J153")
      (value "STRIP3")
      (footprint "eagle-import:STRIP3")
      (libsource (lib "eagle-import") (part "STRIP3"))
    )
    (comp (ref "J154")
      (value "STRIP3")
      (footprint "eagle-import:STRIP3")
      (libsource (lib "eagle-import") (part "STRIP3"))
    )
    (comp (ref "J155")
      (value "STRIP3")
      (footprint "eagle-import:STRIP3")
      (libsource (lib "eagle-import") (part "STRIP3"))
    )
    (comp (ref "J156")
      (value "STRIP3")
      (footprint "eagle-import:STRIP3")
      (libsource (lib "eagle-import") (part "STRIP3"))
    )
    (comp (ref "J157")
      (value "STRIP3")
      (footprint "eagle-import:STRIP3")
      (libsource (lib "eagle-import") (part "STRIP3"))
    )
    (comp (ref "J158")
      (value "STRIP3")
      (footprint "eagle-import:STRIP3")
      (libsource (lib "eagle-import") (part "STRIP3"))
    )
    (comp (ref "J159")
      (value "STRIP3")
      (footprint "eagle-import:STRIP3")
      (libsource (lib "eagle-import") (part "STRIP3"))
    )
    (comp (ref "J160")
      (value "STRIP3")
      (footprint "eagle-import:STRIP3")
      (libsource (lib "eagle-import") (part "STRIP3"))
    )
    (comp (ref "J161")
      (value "STRIP3")
      (footprint "eagle-import:STRIP3")
      (libsource (lib "eagle-import") (part "STRIP3"))
    )
    (comp (ref "J162")
      (value "STRIP3")
      (footprint "eagle-import:STRIP3")
      (libsource (lib "eagle-import") (part "STRIP3"))
    )
    (comp (ref "J163")
      (value "STRIP3")
      (footprint "eagle-import:STRIP3")
      (libsource (lib "eagle-import") (part "STRIP3"))
    )
    (comp (ref "J164")
      (value "STRIP3")
      (footprint "eagle-import:STRIP3")
      (libsource (lib "eagle-import") (part "STRIP3"))
    )
    (comp (ref "J165")
      (value "STRIP3")
      (footprint "eagle-import:STRIP3")
      (libsource (lib "eagle-import") (part "STRIP3"))
    )
    (comp (ref "J166")
      (value "STRIP3")
      (footprint "eagle-import:STRIP3")
      (libsource (lib "eagle-import") (part "STRIP3"))
    )
    (comp (ref "J167")
      (value "STRIP3")
      (footprint "eagle-import:STRIP3")
      (libsource (lib "eagle-import") (part "STRIP3"))
    )
    (comp (ref "J168")
      (value "STRIP3")
      (footprint "eagle-import:STRIP3")
      (libsource (lib "eagle-import") (part "STRIP3"))
    )
    (comp (ref "J169")
      (value "STRIP3")
      (footprint "eagle-import:STRIP3")
      (libsource (lib "eagle-import") (part "STRIP3"))
    )
    (comp (ref "J170")
      (value "STRIP3")
      (footprint "eagle-import:STRIP3")
      (libsource (lib "eagle-import") (part "STRIP3"))
    )
    (comp (ref "J176")
      (value "STRIP3")
      (footprint "eagle-import:STRIP3")
      (libsource (lib "eagle-import") (part "STRIP3"))
    )
    (comp (ref "J177")
      (value "STRIP3")
      (footprint "eagle-import:STRIP3")
      (libsource (lib "eagle-import") (part "STRIP3"))
    )
    (comp (ref "J204")
      (value "STRIP2")
      (footprint "eagle-import:STRIP2")
      (libsource (lib "eagle-import") (part "STRIP2"))
    )
    (comp (ref "J205")
      (value "STRIP2")
      (footprint "eagle-import:STRIP2")
      (libsource (lib "eagle-import") (part "STRIP2"))
    )
    (comp (ref "J206")
      (value "STRIP2")
      (footprint "eagle-import:STRIP2")
      (libsource (lib "eagle-import") (part "STRIP2"))
    )
    (comp (ref "J207")
      (value "STRIP2")
      (footprint "eagle-import:STRIP2")
      (libsource (lib "eagle-import") (part "STRIP2"))
    )
    (comp (ref "J210")
      (value "STRIP2")
      (footprint "eagle-import:STRIP2")
      (libsource (lib "eagle-import") (part "STRIP2"))
    )
    (comp (ref "J211")
      (value "STRIP2")
      (footprint "eagle-import:STRIP2")
      (libsource (lib "eagle-import") (part "STRIP2"))
    )
    (comp (ref "J232")
      (value "STRIP2")
      (footprint "eagle-import:STRIP2")
      (libsource (lib "eagle-import") (part "STRIP2"))
    )
    (comp (ref "J233")
      (value "STRIP2")
      (footprint "eagle-import:STRIP2")
      (libsource (lib "eagle-import") (part "STRIP2"))
    )
    (comp (ref "J234")
      (value "STRIP2")
      (footprint "eagle-import:STRIP2")
      (libsource (lib "eagle-import") (part "STRIP2"))
    )
    (comp (ref "J235")
      (value "STRIP2")
      (footprint "eagle-import:STRIP2")
      (libsource (lib "eagle-import") (part "STRIP2"))
    )
    (comp (ref "J236")
      (value "STRIP2")
      (footprint "eagle-import:STRIP2")
      (libsource (lib "eagle-import") (part "STRIP2"))
    )
    (comp (ref "J237")
      (value "STRIP2")
      (footprint "eagle-import:STRIP2")
      (libsource (lib "eagle-import") (part "STRIP2"))
    )
    (comp (ref "J238")
      (value "STRIP2")
      (footprint "eagle-import:STRIP2")
      (libsource (lib "eagle-import") (part "STRIP2"))
    )
    (comp (ref "J239")
      (value "STRIP2")
      (footprint "eagle-import:STRIP2")
      (libsource (lib "eagle-import") (part "STRIP2"))
    )
    (comp (ref "J240")
      (value "STRIP2")
      (footprint "eagle-import:STRIP2")
      (libsource (lib "eagle-import") (part "STRIP2"))
    )
    (comp (ref "J241")
      (value "STRIP2")
      (footprint "eagle-import:STRIP2")
      (libsource (lib "eagle-import") (part "STRIP2"))
    )
    (comp (ref "J242")
      (value "STRIP2")
      (footprint "eagle-import:STRIP2")
      (libsource (lib "eagle-import") (part "STRIP2"))
    )
    (comp (ref "J243")
      (value "STRIP2")
      (footprint "eagle-import:STRIP2")
      (libsource (lib "eagle-import") (part "STRIP2"))
    )
    (comp (ref "J244")
      (value "STRIP2")
      (footprint "eagle-import:STRIP2")
      (libsource (lib "eagle-import") (part "STRIP2"))
    )
    (comp (ref "J245")
      (value "STRIP2")
      (footprint "eagle-import:STRIP2")
      (libsource (lib "eagle-import") (part "STRIP2"))
    )
    (comp (ref "J246")
      (value "STRIP2")
      (footprint "eagle-import:STRIP2")
      (libsource (lib "eagle-import") (part "STRIP2"))
    )
    (comp (ref "J247")
      (value "STRIP2")
      (footprint "eagle-import:STRIP2")
      (libsource (lib "eagle-import") (part "STRIP2"))
    )
    (comp (ref "J248")
      (value "STRIP2")
      (footprint "eagle-import:STRIP2")
      (libsource (lib "eagle-import") (part "STRIP2"))
    )
    (comp (ref "J249")
      (value "STRIP2")
      (footprint "eagle-import:STRIP2")
      (libsource (lib "eagle-import") (part "STRIP2"))
    )
    (comp (ref "J250")
      (value "STRIP2")
      (footprint "eagle-import:STRIP2")
      (libsource (lib "eagle-import") (part "STRIP2"))
    )
    (comp (ref "J251")
      (value "STRIP2")
      (footprint "eagle-import:STRIP2")
      (libsource (lib "eagle-import") (part "STRIP2"))
    )
    (comp (ref "J252")
      (value "STRIP2")
      (footprint "eagle-import:STRIP2")
      (libsource (lib "eagle-import") (part "STRIP2"))
    )
    (comp (ref "J253")
      (value "STRIP2")
      (footprint "eagle-import:STRIP2")
      (libsource (lib "eagle-import") (part "STRIP2"))
    )
    (comp (ref "JP1")
      (value "VSEL")
      (footprint "eagle-import:1X03")
      (libsource (lib "eagle-import") (part "PINHD-1X3"))
    )
    (comp (ref "L1")
      (value "F28379D_LAUNCHPAD")
      (footprint "eagle-import:F28379D_LAUNCHPAD")
      (libsource (lib "eagle-import") (part "F28379D_LAUNCHPAD"))
    )
    (comp (ref "LED_3.3V1")
      (value "LED3MM")
      (footprint "eagle-import:LED3MM")
      (libsource (lib "eagle-import") (part "LED3MM"))
    )
    (comp (ref "LED_5V1")
      (value "LED3MM")
      (footprint "eagle-import:LED3MM")
      (libsource (lib "eagle-import") (part "LED3MM"))
    )
    (comp (ref "POWER")
      (value "PINHD-1X2")
      (footprint "eagle-import:1X02")
      (libsource (lib "eagle-import") (part "PINHD-1X2"))
    )
    (comp (ref "R24")
      (value "1500")
      (footprint "eagle-import:M1206")
      (libsource (lib "eagle-import") (part "R-US_M1206"))
    )
    (comp (ref "R25")
      (value "470")
      (footprint "eagle-import:M1206")
      (libsource (lib "eagle-import") (part "R-US_M1206"))
    )
    (comp (ref "R26")
      (value "470")
      (footprint "eagle-import:M1206")
      (libsource (lib "eagle-import") (part "R-US_M1206"))
    )
    (comp (ref "R27")
      (value "220")
      (footprint "eagle-import:M1206")
      (libsource (lib "eagle-import") (part "R-US_M1206"))
    )
    (comp (ref "S141")
      (value "STRIP5")
      (footprint "eagle-import:STRIP5")
      (libsource (lib "eagle-import") (part "STRIP5"))
    )
    (comp (ref "U$1")
      (value "MPU-9250-BB")
      (footprint "eagle-import:MPU-9250-BB")
      (libsource (lib "eagle-import") (part "MPU-9250-BB"))
    )
    (comp (ref "U6")
      (value "TL1963A-33KTTR")
      (footprint "eagle-import:TL1963AKTTR")
      (libsource (lib "eagle-import") (part "TL1963A-33KTTR"))
    )
    (comp (ref "U7")
      (value "TL1963A-KTTR")
      (footprint "eagle-import:TL1963AKTTR")
      (libsource (lib "eagle-import") (part "TL1963A-KTTR"))
    )
    (comp (ref "C1")
      (value "47uF")
      (footprint "eagle-import:153CLV-0810")
      (libsource (lib "eagle-import") (part "CPOL-US153CLV-0810"))
    )
    (comp (ref "C2")
      (value "680pF")
      (footprint "eagle-import:C1206")
      (libsource (lib "eagle-import") (part "C-USC1206"))
    )
    (comp (ref "C7")
      (value "10uF")
      (footprint "eagle-import:E2,5-6")
      (libsource (lib "eagle-import") (part "CPOL-USE2.5-6"))
    )
    (comp (ref "C12")
      (value "47uF")
      (footprint "eagle-import:153CLV-0810")
      (libsource (lib "eagle-import") (part "CPOL-US153CLV-0810"))
    )
    (comp (ref "C13")
      (value "47uF")
      (footprint "eagle-import:153CLV-0810")
      (libsource (lib "eagle-import") (part "CPOL-US153CLV-0810"))
    )
    (comp (ref "C14")
      (value "680pF")
      (footprint "eagle-import:C1206")
      (libsource (lib "eagle-import") (part "C-USC1206"))
    )
    (comp (ref "C15")
      (value "47uF")
      (footprint "eagle-import:153CLV-0810")
      (libsource (lib "eagle-import") (part "CPOL-US153CLV-0810"))
    )
    (comp (ref "C16")
      (value "0.1uF")
      (footprint "eagle-import:C1206")
      (libsource (lib "eagle-import") (part "C-USC1206"))
    )
    (comp (ref "C17")
      (value "0.1uF")
      (footprint "eagle-import:C1206")
      (libsource (lib "eagle-import") (part "C-USC1206"))
    )
    (comp (ref "C18")
      (value "0.22uF")
      (footprint "eagle-import:C050-025X075")
      (libsource (lib "eagle-import") (part "C-US050-025X075"))
    )
    (comp (ref "C19")
      (value "22nF")
      (footprint "eagle-import:C1206")
      (libsource (lib "eagle-import") (part "C-USC1206"))
    )
    (comp (ref "C20")
      (value "47uF")
      (footprint "eagle-import:153CLV-0810")
      (libsource (lib "eagle-import") (part "CPOL-US153CLV-0810"))
    )
    (comp (ref "C21")
      (value "10uF")
      (footprint "eagle-import:E2,5-6")
      (libsource (lib "eagle-import") (part "CPOL-USE2.5-6"))
    )
    (comp (ref "C22")
      (value "0.1uF")
      (footprint "eagle-import:C1206")
      (libsource (lib "eagle-import") (part "C-USC1206"))
    )
    (comp (ref "C23")
      (value "0.1uF")
      (footprint "eagle-import:C1206")
      (libsource (lib "eagle-import") (part "C-USC1206"))
    )
    (comp (ref "C24")
      (value "22nF")
      (footprint "eagle-import:C1206")
      (libsource (lib "eagle-import") (part "C-USC1206"))
    )
    (comp (ref "C25")
      (value "47uF")
      (footprint "eagle-import:153CLV-0810")
      (libsource (lib "eagle-import") (part "CPOL-US153CLV-0810"))
    )
    (comp (ref "C26")
      (value "0.1uF")
      (footprint "eagle-import:C050-025X075")
      (libsource (lib "eagle-import") (part "C-US050-025X075"))
    )
    (comp (ref "C27")
      (value "47uF")
      (footprint "eagle-import:153CLV-0810")
      (libsource (lib "eagle-import") (part "CPOL-US153CLV-0810"))
    )
    (comp (ref "C28")
      (value "47uF")
      (footprint "eagle-import:153CLV-0810")
      (libsource (lib "eagle-import") (part "CPOL-US153CLV-0810"))
    )
    (comp (ref "J4")
      (value "STRIP3")
      (footprint "eagle-import:STRIP3")
      (libsource (lib "eagle-import") (part "STRIP3"))
    )
    (comp (ref "J6")
      (value "STRIP3")
      (footprint "eagle-import:STRIP3")
      (libsource (lib "eagle-import") (part "STRIP3"))
    )
    (comp (ref "J7")
      (value "STRIP2")
      (footprint "eagle-import:STRIP2")
      (libsource (lib "eagle-import") (part "STRIP2"))
    )
    (comp (ref "J8")
      (value "STRIP2")
      (footprint "eagle-import:STRIP2")
      (libsource (lib "eagle-import") (part "STRIP2"))
    )
    (comp (ref "J9")
      (value "STRIP2")
      (footprint "eagle-import:STRIP2")
      (libsource (lib "eagle-import") (part "STRIP2"))
    )
    (comp (ref "J23")
      (value "STRIP3")
      (footprint "eagle-import:STRIP3")
      (libsource (lib "eagle-import") (part "STRIP3"))
    )
    (comp (ref "J24")
      (value "STRIP3")
      (footprint "eagle-import:STRIP3")
      (libsource (lib "eagle-import") (part "STRIP3"))
    )
    (comp (ref "J49")
      (value "STRIP3")
      (footprint "eagle-import:STRIP3")
      (libsource (lib "eagle-import") (part "STRIP3"))
    )
    (comp (ref "J78")
      (value "STRIP2")
      (footprint "eagle-import:STRIP2")
      (libsource (lib "eagle-import") (part "STRIP2"))
    )
    (comp (ref "J79")
      (value "STRIP2")
      (footprint "eagle-import:STRIP2")
      (libsource (lib "eagle-import") (part "STRIP2"))
    )
    (comp (ref "J80")
      (value "STRIP2")
      (footprint "eagle-import:STRIP2")
      (libsource (lib "eagle-import") (part "STRIP2"))
    )
    (comp (ref "J81")
      (value "STRIP2")
      (footprint "eagle-import:STRIP2")
      (libsource (lib "eagle-import") (part "STRIP2"))
    )
    (comp (ref "J82")
      (value "STRIP2")
      (footprint "eagle-import:STRIP2")
      (libsource (lib "eagle-import") (part "STRIP2"))
    )
    (comp (ref "J83")
      (value "STRIP2")
      (footprint "eagle-import:STRIP2")
      (libsource (lib "eagle-import") (part "STRIP2"))
    )
    (comp (ref "J84")
      (value "STRIP2")
      (footprint "eagle-import:STRIP2")
      (libsource (lib "eagle-import") (part "STRIP2"))
    )
    (comp (ref "J85")
      (value "STRIP2")
      (footprint "eagle-import:STRIP2")
      (libsource (lib "eagle-import") (part "STRIP2"))
    )
    (comp (ref "J86")
      (value "STRIP2")
      (footprint "eagle-import:STRIP2")
      (libsource (lib "eagle-import") (part "STRIP2"))
    )
    (comp (ref "J87")
      (value "STRIP2")
      (footprint "eagle-import:STRIP2")
      (libsource (lib "eagle-import") (part "STRIP2"))
    )
    (comp (ref "J196")
      (value "STRIP2")
      (footprint "eagle-import:STRIP2")
      (libsource (lib "eagle-import") (part "STRIP2"))
    )
    (comp (ref "J197")
      (value "STRIP2")
      (footprint "eagle-import:STRIP2")
      (libsource (lib "eagle-import") (part "STRIP2"))
    )
    (comp (ref "J198")
      (value "STRIP2")
      (footprint "eagle-import:STRIP2")
      (libsource (lib "eagle-import") (part "STRIP2"))
    )
    (comp (ref "J199")
      (value "STRIP2")
      (footprint "eagle-import:STRIP2")
      (libsource (lib "eagle-import") (part "STRIP2"))
    )
    (comp (ref "J200")
      (value "STRIP2")
      (footprint "eagle-import:STRIP2")
      (libsource (lib "eagle-import") (part "STRIP2"))
    )
    (comp (ref "J201")
      (value "STRIP2")
      (footprint "eagle-import:STRIP2")
      (libsource (lib "eagle-import") (part "STRIP2"))
    )
    (comp (ref "J202")
      (value "STRIP2")
      (footprint "eagle-import:STRIP2")
      (libsource (lib "eagle-import") (part "STRIP2"))
    )
    (comp (ref "J203")
      (value "STRIP2")
      (footprint "eagle-import:STRIP2")
      (libsource (lib "eagle-import") (part "STRIP2"))
    )
    (comp (ref "JP2")
      (value "JP1E")
      (footprint "eagle-import:JP1")
      (libsource (lib "eagle-import") (part "JP1E"))
    )
    (comp (ref "JP3")
      (value "JP1E")
      (footprint "eagle-import:JP1")
      (libsource (lib "eagle-import") (part "JP1E"))
    )
    (comp (ref "M1")
      (value "WM_64_MIC")
      (footprint "eagle-import:WM_64_MIC")
      (libsource (lib "eagle-import") (part "WM_64_MIC"))
    )
    (comp (ref "R1")
      (value "R_B")
      (footprint "eagle-import:0207_10")
      (libsource (lib "eagle-import") (part "R-US_0207/10"))
    )
    (comp (ref "R2")
      (value "R_B")
      (footprint "eagle-import:0207_10")
      (libsource (lib "eagle-import") (part "R-US_0207/10"))
    )
    (comp (ref "R3")
      (value "24.9K")
      (footprint "eagle-import:M1206")
      (libsource (lib "eagle-import") (part "R-US_M1206"))
    )
    (comp (ref "R4")
      (value "2.2K")
      (footprint "eagle-import:M1206")
      (libsource (lib "eagle-import") (part "R-US_M1206"))
    )
    (comp (ref "R5")
      (value "2.2K")
      (footprint "eagle-import:M1206")
      (libsource (lib "eagle-import") (part "R-US_M1206"))
    )
    (comp (ref "R6")
      (value "2.2K")
      (footprint "eagle-import:M1206")
      (libsource (lib "eagle-import") (part "R-US_M1206"))
    )
    (comp (ref "R7")
      (value "24.9K")
      (footprint "eagle-import:M1206")
      (libsource (lib "eagle-import") (part "R-US_M1206"))
    )
    (comp (ref "R8")
      (value "2.2K")
      (footprint "eagle-import:M1206")
      (libsource (lib "eagle-import") (part "R-US_M1206"))
    )
    (comp (ref "R9")
      (value "2.2K")
      (footprint "eagle-import:0207_10")
      (libsource (lib "eagle-import") (part "R-US_0207/10"))
    )
    (comp (ref "R10")
      (value "1.2K")
      (footprint "eagle-import:0207_10")
      (libsource (lib "eagle-import") (part "R-US_0207/10"))
    )
    (comp (ref "R18")
      (value "2.2K")
      (footprint "eagle-import:M1206")
      (libsource (lib "eagle-import") (part "R-US_M1206"))
    )
    (comp (ref "R41")
      (value "1.8K")
      (footprint "eagle-import:M1206")
      (libsource (lib "eagle-import") (part "R-US_M1206"))
    )
    (comp (ref "R42")
      (value "10K")
      (footprint "eagle-import:M1206")
      (libsource (lib "eagle-import") (part "R-US_M1206"))
    )
    (comp (ref "R43")
      (value "1.8K")
      (footprint "eagle-import:M1206")
      (libsource (lib "eagle-import") (part "R-US_M1206"))
    )
    (comp (ref "R44")
      (value "10K")
      (footprint "eagle-import:M1206")
      (libsource (lib "eagle-import") (part "R-US_M1206"))
    )
    (comp (ref "S129")
      (value "STRIP5")
      (footprint "eagle-import:STRIP5")
      (libsource (lib "eagle-import") (part "STRIP5"))
    )
    (comp (ref "S130")
      (value "STRIP5")
      (footprint "eagle-import:STRIP5")
      (libsource (lib "eagle-import") (part "STRIP5"))
    )
    (comp (ref "S137")
      (value "STRIP5")
      (footprint "eagle-import:STRIP5")
      (libsource (lib "eagle-import") (part "STRIP5"))
    )
    (comp (ref "S138")
      (value "STRIP5")
      (footprint "eagle-import:STRIP5")
      (libsource (lib "eagle-import") (part "STRIP5"))
    )
    (comp (ref "S139")
      (value "STRIP5")
      (footprint "eagle-import:STRIP5")
      (libsource (lib "eagle-import") (part "STRIP5"))
    )
    (comp (ref "S147")
      (value "STRIP5")
      (footprint "eagle-import:STRIP5")
      (libsource (lib "eagle-import") (part "STRIP5"))
    )
    (comp (ref "S159")
      (value "SWITCH_SLIDE")
      (footprint "eagle-import:SWITCH_SLIDE")
      (libsource (lib "eagle-import") (part "SWITCH_SLIDE"))
    )
    (comp (ref "SV1")
      (value "MA03-2")
      (footprint "eagle-import:MA03-2")
      (libsource (lib "eagle-import") (part "MA03-2"))
    )
    (comp (ref "SV3")
      (value "MA03-2")
      (footprint "eagle-import:MA03-2")
      (libsource (lib "eagle-import") (part "MA03-2"))
    )
    (comp (ref "SV7")
      (value "MA03-2")
      (footprint "eagle-import:MA03-2")
      (libsource (lib "eagle-import") (part "MA03-2"))
    )
    (comp (ref "SV8")
      (value "MA03-2")
      (footprint "eagle-import:MA03-2")
      (libsource (lib "eagle-import") (part "MA03-2"))
    )
    (comp (ref "T1")
      (value "TIP125")
      (footprint "eagle-import:TO220")
      (libsource (lib "eagle-import") (part "TIP125"))
    )
    (comp (ref "T2")
      (value "TIP125")
      (footprint "eagle-import:TO220")
      (libsource (lib "eagle-import") (part "TIP125"))
    )
    (comp (ref "TRIMPOT1")
      (value "MA03-2")
      (footprint "eagle-import:MA03-2")
      (libsource (lib "eagle-import") (part "MA03-2"))
    )
    (comp (ref "TRIMPOT2")
      (value "MA03-2")
      (footprint "eagle-import:MA03-2")
      (libsource (lib "eagle-import") (part "MA03-2"))
    )
    (comp (ref "U$2")
      (value "GEARMOTOR_MOUNT")
      (footprint "eagle-import:GEARMOTOR_MOUNT")
      (libsource (lib "eagle-import") (part "GEARMOTOR_MOUNT"))
    )
    (comp (ref "U$3")
      (value "GEARMOTOR_MOUNT")
      (footprint "eagle-import:GEARMOTOR_MOUNT")
      (libsource (lib "eagle-import") (part "GEARMOTOR_MOUNT"))
    )
    (comp (ref "U1")
      (value "A3953")
      (footprint "eagle-import:SO16W")
      (libsource (lib "eagle-import") (part "A3953"))
    )
    (comp (ref "U2")
      (value "DRV8874")
      (footprint "eagle-import:HTSSOP16")
      (libsource (lib "eagle-import") (part "DRV8874"))
    )
    (comp (ref "U4")
      (value "DRV8874")
      (footprint "eagle-import:HTSSOP16")
      (libsource (lib "eagle-import") (part "DRV8874"))
    )
    (comp (ref "U5")
      (value "A3953")
      (footprint "eagle-import:SO16W")
      (libsource (lib "eagle-import") (part "A3953"))
    )
    (comp (ref "U8")
      (value "LM386")
      (footprint "eagle-import:DIL08")
      (libsource (lib "eagle-import") (part "LM386"))
    )
    (comp (ref "S17")
      (value "STRIP5")
      (footprint "eagle-import:STRIP5")
      (libsource (lib "eagle-import") (part "STRIP5"))
    )
    (comp (ref "S18")
      (value "STRIP5")
      (footprint "eagle-import:STRIP5")
      (libsource (lib "eagle-import") (part "STRIP5"))
    )
    (comp (ref "S20")
      (value "STRIP10")
      (footprint "eagle-import:STRIP10")
      (libsource (lib "eagle-import") (part "STRIP10"))
    )
    (comp (ref "S24")
      (value "STRIP10")
      (footprint "eagle-import:STRIP10")
      (libsource (lib "eagle-import") (part "STRIP10"))
    )
    (comp (ref "S27")
      (value "STRIP10")
      (footprint "eagle-import:STRIP10")
      (libsource (lib "eagle-import") (part "STRIP10"))
    )
    (comp (ref "S28")
      (value "STRIP10")
      (footprint "eagle-import:STRIP10")
      (libsource (lib "eagle-import") (part "STRIP10"))
    )
    (comp (ref "S42")
      (value "STRIP10")
      (footprint "eagle-import:STRIP10")
      (libsource (lib "eagle-import") (part "STRIP10"))
    )
    (comp (ref "S50")
      (value "STRIP10")
      (footprint "eagle-import:STRIP10")
      (libsource (lib "eagle-import") (part "STRIP10"))
    )
    (comp (ref "S53")
      (value "STRIP10")
      (footprint "eagle-import:STRIP10")
      (libsource (lib "eagle-import") (part "STRIP10"))
    )
    (comp (ref "S58")
      (value "STRIP10")
      (footprint "eagle-import:STRIP10")
      (libsource (lib "eagle-import") (part "STRIP10"))
    )
    (comp (ref "B2")
      (value "BATTERY_4AA_HOLDER")
      (footprint "eagle-import:BATTERY_4AA_HOLDER")
      (libsource (lib "eagle-import") (part "BATTERY_4AA_HOLDER"))
    )
    (comp (ref "J64")
      (value "STRIP2")
      (footprint "eagle-import:STRIP2")
      (libsource (lib "eagle-import") (part "STRIP2"))
    )
    (comp (ref "J65")
      (value "STRIP2")
      (footprint "eagle-import:STRIP2")
      (libsource (lib "eagle-import") (part "STRIP2"))
    )
    (comp (ref "J66")
      (value "STRIP2")
      (footprint "eagle-import:STRIP2")
      (libsource (lib "eagle-import") (part "STRIP2"))
    )
    (comp (ref "J67")
      (value "STRIP2")
      (footprint "eagle-import:STRIP2")
      (libsource (lib "eagle-import") (part "STRIP2"))
    )
    (comp (ref "J68")
      (value "STRIP2")
      (footprint "eagle-import:STRIP2")
      (libsource (lib "eagle-import") (part "STRIP2"))
    )
    (comp (ref "J69")
      (value "STRIP2")
      (footprint "eagle-import:STRIP2")
      (libsource (lib "eagle-import") (part "STRIP2"))
    )
    (comp (ref "J70")
      (value "STRIP2")
      (footprint "eagle-import:STRIP2")
      (libsource (lib "eagle-import") (part "STRIP2"))
    )
    (comp (ref "J71")
      (value "STRIP2")
      (footprint "eagle-import:STRIP2")
      (libsource (lib "eagle-import") (part "STRIP2"))
    )
    (comp (ref "J72")
      (value "STRIP2")
      (footprint "eagle-import:STRIP2")
      (libsource (lib "eagle-import") (part "STRIP2"))
    )
    (comp (ref "J73")
      (value "STRIP2")
      (footprint "eagle-import:STRIP2")
      (libsource (lib "eagle-import") (part "STRIP2"))
    )
    (comp (ref "J74")
      (value "STRIP2")
      (footprint "eagle-import:STRIP2")
      (libsource (lib "eagle-import") (part "STRIP2"))
    )
    (comp (ref "J75")
      (value "STRIP2")
      (footprint "eagle-import:STRIP2")
      (libsource (lib "eagle-import") (part "STRIP2"))
    )
    (comp (ref "J76")
      (value "STRIP2")
      (footprint "eagle-import:STRIP2")
      (libsource (lib "eagle-import") (part "STRIP2"))
    )
    (comp (ref "J77")
      (value "STRIP2")
      (footprint "eagle-import:STRIP2")
      (libsource (lib "eagle-import") (part "STRIP2"))
    )
    (comp (ref "J88")
      (value "RELAY_JQC-3F_5V")
      (footprint "eagle-import:RELAY_JQC-3F_5V")
      (libsource (lib "eagle-import") (part "RELAY_JQC-3F_5V"))
    )
    (comp (ref "J89")
      (value "STRIP2")
      (footprint "eagle-import:STRIP2")
      (libsource (lib "eagle-import") (part "STRIP2"))
    )
    (comp (ref "J90")
      (value "STRIP2")
      (footprint "eagle-import:STRIP2")
      (libsource (lib "eagle-import") (part "STRIP2"))
    )
    (comp (ref "J91")
      (value "STRIP2")
      (footprint "eagle-import:STRIP2")
      (libsource (lib "eagle-import") (part "STRIP2"))
    )
    (comp (ref "J92")
      (value "STRIP2")
      (footprint "eagle-import:STRIP2")
      (libsource (lib "eagle-import") (part "STRIP2"))
    )
    (comp (ref "J93")
      (value "STRIP2")
      (footprint "eagle-import:STRIP2")
      (libsource (lib "eagle-import") (part "STRIP2"))
    )
    (comp (ref "SV2")
      (value "MA20-2")
      (footprint "eagle-import:MA20-2")
      (libsource (lib "eagle-import") (part "MA20-2"))
    )
    (comp (ref "SV4")
      (value "MA20-2")
      (footprint "eagle-import:MA20-2")
      (libsource (lib "eagle-import") (part "MA20-2"))
    )
    (comp (ref "SV5")
      (value "MA06-2")
      (footprint "eagle-import:MA06-2")
      (libsource (lib "eagle-import") (part "MA06-2"))
    )
    (comp (ref "SV6")
      (value "MA06-2")
      (footprint "eagle-import:MA06-2")
      (libsource (lib "eagle-import") (part "MA06-2"))
    )
    (comp (ref "U$4")
      (value "CASTERWHEEL")
      (footprint "eagle-import:CASTERWHEEL")
      (libsource (lib "eagle-import") (part "CASTERWHEEL"))
    )
  )
  (nets
    (net (code "1") (name "+5V") (class "Default")
      (node (ref "C8") (pin "1") (pinfunction "1_1") (pintype "passive"))
      (node (ref "DCDC5V") (pin "3") (pinfunction "3_3") (pintype "passive"))
      (node (ref "J103") (pin "P$1") (pinfunction "P$1_P$1") (pintype "bidirectional"))
      (node (ref "J103") (pin "P$2") (pinfunction "P$2_P$2") (pintype "bidirectional"))
      (node (ref "J103") (pin "P$3") (pinfunction "P$3_P$3") (pintype "bidirectional"))
      (node (ref "J152") (pin "P$1") (pinfunction "P$1_P$1") (pintype "bidirectional"))
      (node (ref "J152") (pin "P$2") (pinfunction "P$2_P$2") (pintype "bidirectional"))
      (node (ref "J152") (pin "P$3") (pinfunction "P$3_P$3") (pintype "bidirectional"))
      (node (ref "J200") (pin "P$1") (pinfunction "P$1_P$1") (pintype "bidirectional"))
      (node (ref "J200") (pin "P$2") (pinfunction "P$2_P$2") (pintype "bidirectional"))
      (node (ref "J203") (pin "P$1") (pinfunction "P$1_P$1") (pintype "bidirectional"))
      (node (ref "J203") (pin "P$2") (pinfunction "P$2_P$2") (pintype "bidirectional"))
      (node (ref "L1") (pin "P$21") (pinfunction "5V_1_P$21") (pintype "bidirectional"))
      (node (ref "L1") (pin "P$61") (pinfunction "5V_2_P$61") (pintype "bidirectional"))
      (node (ref "R24") (pin "2") (pinfunction "2_2") (pintype "passive"))
      (node (ref "R26") (pin "2") (pinfunction "2_2") (pintype "passive"))
      (node (ref "S17") (pin "P$1") (pinfunction "P$1_P$1") (pintype "bidirectional"))
      (node (ref "S17") (pin "P$2") (pinfunction "P$2_P$2") (pintype "bidirectional"))
      (node (ref "S17") (pin "P$3") (pinfunction "P$3_P$3") (pintype "bidirectional"))
      (node (ref "S17") (pin "P$4") (pinfunction "P$4_P$4") (pintype "bidirectional"))
      (node (ref "S17") (pin "P$5") (pinfunction "P$5_P$5") (pintype "bidirectional"))
      (node (ref "S18") (pin "P$1") (pinfunction "P$1_P$1") (pintype "bidirectional"))
      (node (ref "S18") (pin "P$2") (pinfunction "P$2_P$2") (pintype "bidirectional"))
      (node (ref "S18") (pin "P$3") (pinfunction "P$3_P$3") (pintype "bidirectional"))
      (node (ref "S18") (pin "P$4") (pinfunction "P$4_P$4") (pintype "bidirectional"))
      (node (ref "S18") (pin "P$5") (pinfunction "P$5_P$5") (pintype "bidirectional"))
      (node (ref "SV2") (pin "1") (pinfunction "1_1") (pintype "passive"))
      (node (ref "SV2") (pin "2") (pinfunction "2_2") (pintype "passive"))
      (node (ref "SV2") (pin "3") (pinfunction "3_3") (pintype "passive"))
      (node (ref "SV2") (pin "4") (pinfunction "4_4") (pintype "passive"))
      (node (ref "U7") (pin "P$4") (pinfunction "OUT_P$4") (pintype "bidirectional"))
    )
    (net (code "2") (name "ADCIN14") (class "Default")
      (node (ref "J105") (pin "P$1") (pinfunction "P$1_P$1") (pintype "bidirectional"))
      (node (ref "J105") (pin "P$2") (pinfunction "P$2_P$2") (pintype "bidirectional"))
      (node (ref "J105") (pin "P$3") (pinfunction "P$3_P$3") (pintype "bidirectional"))
      (node (ref "L1") (pin "P$23") (pinfunction "ADCIN14_P$23") (pintype "bidirectional"))
    )
    (net (code "3") (name "ADCIN15") (class "Default")
      (node (ref "J150") (pin "P$1") (pinfunction "P$1_P$1") (pintype "bidirectional"))
      (node (ref "J150") (pin "P$2") (pinfunction "P$2_P$2") (pintype "bidirectional"))
      (node (ref "J150") (pin "P$3") (pinfunction "P$3_P$3") (pintype "bidirectional"))
      (node (ref "L1") (pin "P$63") (pinfunction "ADCIN15_P$63") (pintype "bidirectional"))
    )
    (net (code "4") (name "ADCINA2") (class "Default")
      (node (ref "J111") (pin "P$1") (pinfunction "P$1_P$1") (pintype "bidirectional"))
      (node (ref "J111") (pin "P$2") (pinfunction "P$2_P$2") (pintype "bidirectional"))
      (node (ref "J111") (pin "P$3") (pinfunction "P$3_P$3") (pintype "bidirectional"))
      (node (ref "L1") (pin "P$29") (pinfunction "ADCINA2_P$29") (pintype "bidirectional"))
    )
    (net (code "5") (name "ADCINA3") (class "Default")
      (node (ref "J108") (pin "P$1") (pinfunction "P$1_P$1") (pintype "bidirectional"))
      (node (ref "J108") (pin "P$2") (pinfunction "P$2_P$2") (pintype "bidirectional"))
      (node (ref "J108") (pin "P$3") (pinfunction "P$3_P$3") (pintype "bidirectional"))
      (node (ref "L1") (pin "P$26") (pinfunction "ADCINA3_P$26") (pintype "bidirectional"))
    )
    (net (code "6") (name "ADCINA4") (class "Default")
      (node (ref "J144") (pin "P$1") (pinfunction "P$1_P$1") (pintype "bidirectional"))
      (node (ref "J144") (pin "P$2") (pinfunction "P$2_P$2") (pintype "bidirectional"))
      (node (ref "J144") (pin "P$3") (pinfunction "P$3_P$3") (pintype "bidirectional"))
      (node (ref "L1") (pin "P$69") (pinfunction "ADCINA4_P$69") (pintype "bidirectional"))
    )
    (net (code "7") (name "ADCINA5") (class "Default")
      (node (ref "J147") (pin "P$1") (pinfunction "P$1_P$1") (pintype "bidirectional"))
      (node (ref "J147") (pin "P$2") (pinfunction "P$2_P$2") (pintype "bidirectional"))
      (node (ref "J147") (pin "P$3") (pinfunction "P$3_P$3") (pintype "bidirectional"))
      (node (ref "L1") (pin "P$66") (pinfunction "ADCINA5_P$66") (pintype "bidirectional"))
    )
    (net (code "8") (name "ADCINB2") (class "Default")
      (node (ref "J110") (pin "P$1") (pinfunction "P$1_P$1") (pintype "bidirectional"))
      (node (ref "J110") (pin "P$2") (pinfunction "P$2_P$2") (pintype "bidirectional"))
      (node (ref "J110") (pin "P$3") (pinfunction "P$3_P$3") (pintype "bidirectional"))
      (node (ref "L1") (pin "P$28") (pinfunction "ADCINB2_P$28") (pintype "bidirectional"))
    )
    (net (code "9") (name "ADCINB3") (class "Default")
      (node (ref "J107") (pin "P$1") (pinfunction "P$1_P$1") (pintype "bidirectional"))
      (node (ref "J107") (pin "P$2") (pinfunction "P$2_P$2") (pintype "bidirectional"))
      (node (ref "J107") (pin "P$3") (pinfunction "P$3_P$3") (pintype "bidirectional"))
      (node (ref "L1") (pin "P$25") (pinfunction "ADCINB3_P$25") (pintype "bidirectional"))
    )
    (net (code "10") (name "ADCINB4") (class "Default")
      (node (ref "J145") (pin "P$1") (pinfunction "P$1_P$1") (pintype "bidirectional"))
      (node (ref "J145") (pin "P$2") (pinfunction "P$2_P$2") (pintype "bidirectional"))
      (node (ref "J145") (pin "P$3") (pinfunction "P$3_P$3") (pintype "bidirectional"))
      (node (ref "L1") (pin "P$68") (pinfunction "ADCINB4_P$68") (pintype "bidirectional"))
    )
    (net (code "11") (name "ADCINB5") (class "Default")
      (node (ref "J148") (pin "P$1") (pinfunction "P$1_P$1") (pintype "bidirectional"))
      (node (ref "J148") (pin "P$2") (pinfunction "P$2_P$2") (pintype "bidirectional"))
      (node (ref "J148") (pin "P$3") (pinfunction "P$3_P$3") (pintype "bidirectional"))
      (node (ref "L1") (pin "P$65") (pinfunction "ADCINB5_P$65") (pintype "bidirectional"))
    )
    (net (code "12") (name "ADCINC2") (class "Default")
      (node (ref "J109") (pin "P$1") (pinfunction "P$1_P$1") (pintype "bidirectional"))
      (node (ref "J109") (pin "P$2") (pinfunction "P$2_P$2") (pintype "bidirectional"))
      (node (ref "J109") (pin "P$3") (pinfunction "P$3_P$3") (pintype "bidirectional"))
      (node (ref "L1") (pin "P$27") (pinfunction "ADCINC2_P$27") (pintype "bidirectional"))
    )
    (net (code "13") (name "ADCINC3") (class "Default")
      (node (ref "J106") (pin "P$1") (pinfunction "P$1_P$1") (pintype "bidirectional"))
      (node (ref "J106") (pin "P$2") (pinfunction "P$2_P$2") (pintype "bidirectional"))
      (node (ref "J106") (pin "P$3") (pinfunction "P$3_P$3") (pintype "bidirectional"))
      (node (ref "L1") (pin "P$24") (pinfunction "ADCINC3_P$24") (pintype "bidirectional"))
    )
    (net (code "14") (name "ADCINC4") (class "Default")
      (node (ref "J146") (pin "P$1") (pinfunction "P$1_P$1") (pintype "bidirectional"))
      (node (ref "J146") (pin "P$2") (pinfunction "P$2_P$2") (pintype "bidirectional"))
      (node (ref "J146") (pin "P$3") (pinfunction "P$3_P$3") (pintype "bidirectional"))
      (node (ref "L1") (pin "P$67") (pinfunction "ADCINC4_P$67") (pintype "bidirectional"))
    )
    (net (code "15") (name "ADCINC5") (class "Default")
      (node (ref "J149") (pin "P$1") (pinfunction "P$1_P$1") (pintype "bidirectional"))
      (node (ref "J149") (pin "P$2") (pinfunction "P$2_P$2") (pintype "bidirectional"))
      (node (ref "J149") (pin "P$3") (pinfunction "P$3_P$3") (pintype "bidirectional"))
      (node (ref "L1") (pin "P$64") (pinfunction "ADCINC5_P$64") (pintype "bidirectional"))
    )
    (net (code "16") (name "DAC1") (class "Default")
      (node (ref "J114") (pin "P$1") (pinfunction "P$1_P$1") (pintype "bidirectional"))
      (node (ref "J114") (pin "P$2") (pinfunction "P$2_P$2") (pintype "bidirectional"))
      (node (ref "J114") (pin "P$3") (pinfunction "P$3_P$3") (pintype "bidirectional"))
      (node (ref "L1") (pin "P$32") (pinfunction "DAC1_P$32") (pintype "bidirectional"))
    )
    (net (code "17") (name "DAC2") (class "Default")
      (node (ref "J113") (pin "P$1") (pinfunction "P$1_P$1") (pintype "bidirectional"))
      (node (ref "J113") (pin "P$2") (pinfunction "P$2_P$2") (pintype "bidirectional"))
      (node (ref "J113") (pin "P$3") (pinfunction "P$3_P$3") (pintype "bidirectional"))
      (node (ref "L1") (pin "P$31") (pinfunction "DAC2_P$31") (pintype "bidirectional"))
    )
    (net (code "18") (name "DAC3") (class "Default")
      (node (ref "J141") (pin "P$1") (pinfunction "P$1_P$1") (pintype "bidirectional"))
      (node (ref "J141") (pin "P$2") (pinfunction "P$2_P$2") (pintype "bidirectional"))
      (node (ref "J141") (pin "P$3") (pinfunction "P$3_P$3") (pintype "bidirectional"))
      (node (ref "J252") (pin "P$1") (pinfunction "P$1_P$1") (pintype "bidirectional"))
      (node (ref "J252") (pin "P$2") (pinfunction "P$2_P$2") (pintype "bidirectional"))
      (node (ref "L1") (pin "P$72") (pinfunction "DAC3_P$72") (pintype "bidirectional"))
    )
    (net (code "19") (name "DAC4") (class "Default")
      (node (ref "J142") (pin "P$1") (pinfunction "P$1_P$1") (pintype "bidirectional"))
      (node (ref "J142") (pin "P$2") (pinfunction "P$2_P$2") (pintype "bidirectional"))
      (node (ref "J142") (pin "P$3") (pinfunction "P$3_P$3") (pintype "bidirectional"))
      (node (ref "J253") (pin "P$1") (pinfunction "P$1_P$1") (pintype "bidirectional"))
      (node (ref "J253") (pin "P$2") (pinfunction "P$2_P$2") (pintype "bidirectional"))
      (node (ref "L1") (pin "P$71") (pinfunction "DAC4_P$71") (pintype "bidirectional"))
    )
    (net (code "20") (name "DACOUTA") (class "Default")
      (node (ref "J112") (pin "P$1") (pinfunction "P$1_P$1") (pintype "bidirectional"))
      (node (ref "J112") (pin "P$2") (pinfunction "P$2_P$2") (pintype "bidirectional"))
      (node (ref "J112") (pin "P$3") (pinfunction "P$3_P$3") (pintype "bidirectional"))
      (node (ref "L1") (pin "P$30") (pinfunction "ADCINA0/DACOUTA_P$30") (pintype "bidirectional"))
    )
    (net (code "21") (name "DACOUTB") (class "Default")
      (node (ref "J143") (pin "P$1") (pinfunction "P$1_P$1") (pintype "bidirectional"))
      (node (ref "J143") (pin "P$2") (pinfunction "P$2_P$2") (pintype "bidirectional"))
      (node (ref "J143") (pin "P$3") (pinfunction "P$3_P$3") (pintype "bidirectional"))
      (node (ref "L1") (pin "P$70") (pinfunction "ADCINA1/DACOUTB_P$70") (pintype "bidirectional"))
    )
    (net (code "22") (name "DRV1_DIR") (class "Default")
      (node (ref "J80") (pin "P$1") (pinfunction "P$1_P$1") (pintype "bidirectional"))
      (node (ref "J80") (pin "P$2") (pinfunction "P$2_P$2") (pintype "bidirectional"))
      (node (ref "U2") (pin "P$2") (pinfunction "PH/IN2_P$2") (pintype "bidirectional"))
    )
    (net (code "23") (name "DRV1_M+") (class "Default")
      (node (ref "SV7") (pin "1") (pinfunction "1_1") (pintype "passive"))
      (node (ref "SV7") (pin "3") (pinfunction "3_3") (pintype "passive"))
      (node (ref "SV7") (pin "5") (pinfunction "5_5") (pintype "passive"))
      (node (ref "U2") (pin "P$8") (pinfunction "OUT1_P$8") (pintype "bidirectional"))
    )
    (net (code "24") (name "DRV1_M-") (class "Default")
      (node (ref "SV7") (pin "2") (pinfunction "2_2") (pintype "passive"))
      (node (ref "SV7") (pin "4") (pinfunction "4_4") (pintype "passive"))
      (node (ref "SV7") (pin "6") (pinfunction "6_6") (pintype "passive"))
      (node (ref "U2") (pin "P$10") (pinfunction "OUT2_P$10") (pintype "bidirectional"))
    )
    (net (code "25") (name "DRV1_PWM") (class "Default")
      (node (ref "J79") (pin "P$1") (pinfunction "P$1_P$1") (pintype "bidirectional"))
      (node (ref "J79") (pin "P$2") (pinfunction "P$2_P$2") (pintype "bidirectional"))
      (node (ref "U2") (pin "P$1") (pinfunction "EN/IN1_P$1") (pintype "bidirectional"))
    )
    (net (code "26") (name "DRV2_DIR") (class "Default")
      (node (ref "J83") (pin "P$1") (pinfunction "P$1_P$1") (pintype "bidirectional"))
      (node (ref "J83") (pin "P$2") (pinfunction "P$2_P$2") (pintype "bidirectional"))
      (node (ref "U4") (pin "P$2") (pinfunction "PH/IN2_P$2") (pintype "bidirectional"))
    )
    (net (code "27") (name "DRV2_M+") (class "Default")
      (node (ref "SV8") (pin "1") (pinfunction "1_1") (pintype "passive"))
      (node (ref "SV8") (pin "3") (pinfunction "3_3") (pintype "passive"))
      (node (ref "SV8") (pin "5") (pinfunction "5_5") (pintype "passive"))
      (node (ref "U4") (pin "P$8") (pinfunction "OUT1_P$8") (pintype "bidirectional"))
    )
    (net (code "28") (name "DRV2_M-") (class "Default")
      (node (ref "SV8") (pin "2") (pinfunction "2_2") (pintype "passive"))
      (node (ref "SV8") (pin "4") (pinfunction "4_4") (pintype "passive"))
      (node (ref "SV8") (pin "6") (pinfunction "6_6") (pintype "passive"))
      (node (ref "U4") (pin "P$10") (pinfunction "OUT2_P$10") (pintype "bidirectional"))
    )
    (net (code "29") (name "DRV2_PWM") (class "Default")
      (node (ref "J82") (pin "P$1") (pinfunction "P$1_P$1") (pintype "bidirectional"))
      (node (ref "J82") (pin "P$2") (pinfunction "P$2_P$2") (pintype "bidirectional"))
      (node (ref "U4") (pin "P$1") (pinfunction "EN/IN1_P$1") (pintype "bidirectional"))
    )
    (net (code "30") (name "GND") (class "Default")
      (node (ref "B1") (pin "P$2") (pinfunction "P$2_P$2") (pintype "bidirectional"))
      (node (ref "B2") (pin "P$2") (pinfunction "BAT-_P$2") (pintype "bidirectional"))
      (node (ref "C1") (pin "-") (pinfunction "-_-") (pintype "passive"))
      (node (ref "C10") (pin "2") (pinfunction "2_2") (pintype "passive"))
      (node (ref "C11") (pin "2") (pinfunction "2_2") (pintype "passive"))
      (node (ref "C12") (pin "-") (pinfunction "-_-") (pintype "passive"))
      (node (ref "C13") (pin "-") (pinfunction "-_-") (pintype "passive"))
      (node (ref "C14") (pin "2") (pinfunction "2_2") (pintype "passive"))
      (node (ref "C15") (pin "-") (pinfunction "-_-") (pintype "passive"))
      (node (ref "C16") (pin "2") (pinfunction "2_2") (pintype "passive"))
      (node (ref "C2") (pin "2") (pinfunction "2_2") (pintype "passive"))
      (node (ref "C20") (pin "-") (pinfunction "-_-") (pintype "passive"))
      (node (ref "C22") (pin "2") (pinfunction "2_2") (pintype "passive"))
      (node (ref "C25") (pin "-") (pinfunction "-_-") (pintype "passive"))
      (node (ref "C26") (pin "2") (pinfunction "2_2") (pintype "passive"))
      (node (ref "C27") (pin "-") (pinfunction "-_-") (pintype "passive"))
      (node (ref "C28") (pin "-") (pinfunction "-_-") (pintype "passive"))
      (node (ref "C3") (pin "2") (pinfunction "2_2") (pintype "passive"))
      (node (ref "C4") (pin "2") (pinfunction "2_2") (pintype "passive"))
      (node (ref "C5") (pin "2") (pinfunction "2_2") (pintype "passive"))
      (node (ref "C6") (pin "2") (pinfunction "2_2") (pintype "passive"))
      (node (ref "C7") (pin "-") (pinfunction "-_-") (pintype "passive"))
      (node (ref "C8") (pin "2") (pinfunction "2_2") (pintype "passive"))
      (node (ref "C9") (pin "2") (pinfunction "2_2") (pintype "passive"))
      (node (ref "DCDC3.3V") (pin "2") (pinfunction "2_2") (pintype "passive"))
      (node (ref "DCDC5V") (pin "2") (pinfunction "2_2") (pintype "passive"))
      (node (ref "G1") (pin "-") (pinfunction "-_-") (pintype "passive"))
      (node (ref "IC1") (pin "7") (pinfunction "GND_7") (pintype "power_in"))
      (node (ref "IC2") (pin "7") (pinfunction "GND_7") (pintype "power_in"))
      (node (ref "IC3") (pin "7") (pinfunction "GND_7") (pintype "power_in"))
      (node (ref "IC4") (pin "7") (pinfunction "GND_7") (pintype "power_in"))
      (node (ref "J102") (pin "P$1") (pinfunction "P$1_P$1") (pintype "bidirectional"))
      (node (ref "J102") (pin "P$2") (pinfunction "P$2_P$2") (pintype "bidirectional"))
      (node (ref "J102") (pin "P$3") (pinfunction "P$3_P$3") (pintype "bidirectional"))
      (node (ref "J104") (pin "P$1") (pinfunction "P$1_P$1") (pintype "bidirectional"))
      (node (ref "J104") (pin "P$2") (pinfunction "P$2_P$2") (pintype "bidirectional"))
      (node (ref "J104") (pin "P$3") (pinfunction "P$3_P$3") (pintype "bidirectional"))
      (node (ref "J124") (pin "P$1") (pinfunction "P$1_P$1") (pintype "bidirectional"))
      (node (ref "J124") (pin "P$2") (pinfunction "P$2_P$2") (pintype "bidirectional"))
      (node (ref "J124") (pin "P$3") (pinfunction "P$3_P$3") (pintype "bidirectional"))
      (node (ref "J151") (pin "P$1") (pinfunction "P$1_P$1") (pintype "bidirectional"))
      (node (ref "J151") (pin "P$2") (pinfunction "P$2_P$2") (pintype "bidirectional"))
      (node (ref "J151") (pin "P$3") (pinfunction "P$3_P$3") (pintype "bidirectional"))
      (node (ref "J153") (pin "P$1") (pinfunction "P$1_P$1") (pintype "bidirectional"))
      (node (ref "J153") (pin "P$2") (pinfunction "P$2_P$2") (pintype "bidirectional"))
      (node (ref "J153") (pin "P$3") (pinfunction "P$3_P$3") (pintype "bidirectional"))
      (node (ref "J5") (pin "2") (pinfunction "2_2") (pintype "passive"))
      (node (ref "J5") (pin "3") (pinfunction "3_3") (pintype "passive"))
      (node (ref "J64") (pin "P$1") (pinfunction "P$1_P$1") (pintype "bidirectional"))
      (node (ref "J64") (pin "P$2") (pinfunction "P$2_P$2") (pintype "bidirectional"))
      (node (ref "J9") (pin "P$1") (pinfunction "P$1_P$1") (pintype "bidirectional"))
      (node (ref "J9") (pin "P$2") (pinfunction "P$2_P$2") (pintype "bidirectional"))
      (node (ref "JP2") (pin "2") (pinfunction "2_2") (pintype "passive"))
      (node (ref "JP3") (pin "2") (pinfunction "2_2") (pintype "passive"))
      (node (ref "L1") (pin "P$20") (pinfunction "GND_1_P$20") (pintype "bidirectional"))
      (node (ref "L1") (pin "P$22") (pinfunction "GND_2_P$22") (pintype "bidirectional"))
      (node (ref "L1") (pin "P$60") (pinfunction "GND_3_P$60") (pintype "bidirectional"))
      (node (ref "L1") (pin "P$62") (pinfunction "GND_4_P$62") (pintype "bidirectional"))
      (node (ref "LED_3.3V1") (pin "K") (pinfunction "C_K") (pintype "passive"))
      (node (ref "LED_5V1") (pin "K") (pinfunction "C_K") (pintype "passive"))
      (node (ref "M1") (pin "P$2") (pinfunction "GND_P$2") (pintype "bidirectional"))
      (node (ref "POWER") (pin "1") (pinfunction "1_1") (pintype "passive"))
      (node (ref "R25") (pin "1") (pinfunction "1_1") (pintype "passive"))
      (node (ref "R3") (pin "1") (pinfunction "1_1") (pintype "passive"))
      (node (ref "R41") (pin "2") (pinfunction "2_2") (pintype "passive"))
      (node (ref "R43") (pin "2") (pinfunction "2_2") (pintype "passive"))
      (node (ref "R7") (pin "1") (pinfunction "1_1") (pintype "passive"))
      (node (ref "S129") (pin "P$1") (pinfunction "P$1_P$1") (pintype "bidirectional"))
      (node (ref "S129") (pin "P$2") (pinfunction "P$2_P$2") (pintype "bidirectional"))
      (node (ref "S129") (pin "P$3") (pinfunction "P$3_P$3") (pintype "bidirectional"))
      (node (ref "S129") (pin "P$4") (pinfunction "P$4_P$4") (pintype "bidirectional"))
      (node (ref "S129") (pin "P$5") (pinfunction "P$5_P$5") (pintype "bidirectional"))
      (node (ref "S137") (pin "P$1") (pinfunction "P$1_P$1") (pintype "bidirectional"))
      (node (ref "S137") (pin "P$2") (pinfunction "P$2_P$2") (pintype "bidirectional"))
      (node (ref "S137") (pin "P$3") (pinfunction "P$3_P$3") (pintype "bidirectional"))
      (node (ref "S137") (pin "P$4") (pinfunction "P$4_P$4") (pintype "bidirectional"))
      (node (ref "S137") (pin "P$5") (pinfunction "P$5_P$5") (pintype "bidirectional"))
      (node (ref "S159") (pin "P$1") (pinfunction "P1_P$1") (pintype "bidirectional"))
      (node (ref "S20") (pin "P$1") (pinfunction "P$1_P$1") (pintype "bidirectional"))
      (node (ref "S20") (pin "P$10") (pinfunction "P$10_P$10") (pintype "bidirectional"))
      (node (ref "S20") (pin "P$2") (pinfunction "P$2_P$2") (pintype "bidirectional"))
      (node (ref "S20") (pin "P$3") (pinfunction "P$3_P$3") (pintype "bidirectional"))
      (node (ref "S20") (pin "P$4") (pinfunction "P$4_P$4") (pintype "bidirectional"))
      (node (ref "S20") (pin "P$5") (pinfunction "P$5_P$5") (pintype "bidirectional"))
      (node (ref "S20") (pin "P$6") (pinfunction "P$6_P$6") (pintype "bidirectional"))
      (node (ref "S20") (pin "P$7") (pinfunction "P$7_P$7") (pintype "bidirectional"))
      (node (ref "S20") (pin "P$8") (pinfunction "P$8_P$8") (pintype "bidirectional"))
      (node (ref "S20") (pin "P$9") (pinfunction "P$9_P$9") (pintype "bidirectional"))
      (node (ref "S24") (pin "P$1") (pinfunction "P$1_P$1") (pintype "bidirectional"))
      (node (ref "S24") (pin "P$10") (pinfunction "P$10_P$10") (pintype "bidirectional"))
      (node (ref "S24") (pin "P$2") (pinfunction "P$2_P$2") (pintype "bidirectional"))
      (node (ref "S24") (pin "P$3") (pinfunction "P$3_P$3") (pintype "bidirectional"))
      (node (ref "S24") (pin "P$4") (pinfunction "P$4_P$4") (pintype "bidirectional"))
      (node (ref "S24") (pin "P$5") (pinfunction "P$5_P$5") (pintype "bidirectional"))
      (node (ref "S24") (pin "P$6") (pinfunction "P$6_P$6") (pintype "bidirectional"))
      (node (ref "S24") (pin "P$7") (pinfunction "P$7_P$7") (pintype "bidirectional"))
      (node (ref "S24") (pin "P$8") (pinfunction "P$8_P$8") (pintype "bidirectional"))
      (node (ref "S24") (pin "P$9") (pinfunction "P$9_P$9") (pintype "bidirectional"))
      (node (ref "S27") (pin "P$1") (pinfunction "P$1_P$1") (pintype "bidirectional"))
      (node (ref "S27") (pin "P$10") (pinfunction "P$10_P$10") (pintype "bidirectional"))
      (node (ref "S27") (pin "P$2") (pinfunction "P$2_P$2") (pintype "bidirectional"))
      (node (ref "S27") (pin "P$3") (pinfunction "P$3_P$3") (pintype "bidirectional"))
      (node (ref "S27") (pin "P$4") (pinfunction "P$4_P$4") (pintype "bidirectional"))
      (node (ref "S27") (pin "P$5") (pinfunction "P$5_P$5") (pintype "bidirectional"))
      (node (ref "S27") (pin "P$6") (pinfunction "P$6_P$6") (pintype "bidirectional"))
      (node (ref "S27") (pin "P$7") (pinfunction "P$7_P$7") (pintype "bidirectional"))
      (node (ref "S27") (pin "P$8") (pinfunction "P$8_P$8") (pintype "bidirectional"))
      (node (ref "S27") (pin "P$9") (pinfunction "P$9_P$9") (pintype "bidirectional"))
      (node (ref "S28") (pin "P$1") (pinfunction "P$1_P$1") (pintype "bidirectional"))
      (node (ref "S28") (pin "P$10") (pinfunction "P$10_P$10") (pintype "bidirectional"))
      (node (ref "S28") (pin "P$2") (pinfunction "P$2_P$2") (pintype "bidirectional"))
      (node (ref "S28") (pin "P$3") (pinfunction "P$3_P$3") (pintype "bidirectional"))
      (node (ref "S28") (pin "P$4") (pinfunction "P$4_P$4") (pintype "bidirectional"))
      (node (ref "S28") (pin "P$5") (pinfunction "P$5_P$5") (pintype "bidirectional"))
      (node (ref "S28") (pin "P$6") (pinfunction "P$6_P$6") (pintype "bidirectional"))
      (node (ref "S28") (pin "P$7") (pinfunction "P$7_P$7") (pintype "bidirectional"))
      (node (ref "S28") (pin "P$8") (pinfunction "P$8_P$8") (pintype "bidirectional"))
      (node (ref "S28") (pin "P$9") (pinfunction "P$9_P$9") (pintype "bidirectional"))
      (node (ref "SV2") (pin "13") (pinfunction "13_13") (pintype "passive"))
      (node (ref "SV2") (pin "14") (pinfunction "14_14") (pintype "passive"))
      (node (ref "SV2") (pin "19") (pinfunction "19_19") (pintype "passive"))
      (node (ref "SV2") (pin "20") (pinfunction "20_20") (pintype "passive"))
      (node (ref "SV2") (pin "29") (pinfunction "29_29") (pintype "passive"))
      (node (ref "SV2") (pin "30") (pinfunction "30_30") (pintype "passive"))
      (node (ref "SV2") (pin "33") (pinfunction "33_33") (pintype "passive"))
      (node (ref "SV2") (pin "34") (pinfunction "34_34") (pintype "passive"))
      (node (ref "SV4") (pin "10") (pinfunction "10_10") (pintype "passive"))
      (node (ref "SV4") (pin "25") (pinfunction "25_25") (pintype "passive"))
      (node (ref "SV4") (pin "26") (pinfunction "26_26") (pintype "passive"))
      (node (ref "SV4") (pin "39") (pinfunction "39_39") (pintype "passive"))
      (node (ref "SV4") (pin "40") (pinfunction "40_40") (pintype "passive"))
      (node (ref "SV4") (pin "9") (pinfunction "9_9") (pintype "passive"))
      (node (ref "T1") (pin "3") (pinfunction "E_3") (pintype "passive"))
      (node (ref "T2") (pin "3") (pinfunction "E_3") (pintype "passive"))
      (node (ref "TRIMPOT1") (pin "5") (pinfunction "5_5") (pintype "passive"))
      (node (ref "TRIMPOT1") (pin "6") (pinfunction "6_6") (pintype "passive"))
      (node (ref "TRIMPOT2") (pin "5") (pinfunction "5_5") (pintype "passive"))
      (node (ref "TRIMPOT2") (pin "6") (pinfunction "6_6") (pintype "passive"))
      (node (ref "U$1") (pin "2") (pinfunction "P2_GND_2") (pintype "bidirectional"))
      (node (ref "U1") (pin "11") (pinfunction "SENSE_11") (pintype "bidirectional"))
      (node (ref "U1") (pin "12") (pinfunction "GND_12") (pintype "bidirectional"))
      (node (ref "U1") (pin "13") (pinfunction "GND_13") (pintype "bidirectional"))
      (node (ref "U1") (pin "4") (pinfunction "GND_4") (pintype "bidirectional"))
      (node (ref "U1") (pin "5") (pinfunction "GND_5") (pintype "bidirectional"))
      (node (ref "U2") (pin "P$15") (pinfunction "GND_P$15") (pintype "bidirectional"))
      (node (ref "U2") (pin "P$16") (pinfunction "PMODE_P$16") (pintype "bidirectional"))
      (node (ref "U2") (pin "P$17") (pinfunction "GND_PAD_P$17") (pintype "bidirectional"))
      (node (ref "U2") (pin "P$7") (pinfunction "IMODE_P$7") (pintype "bidirectional"))
      (node (ref "U2") (pin "P$9") (pinfunction "PGND_P$9") (pintype "bidirectional"))
      (node (ref "U3") (pin "4") (pinfunction "P4_GND_4") (pintype "bidirectional"))
      (node (ref "U4") (pin "P$15") (pinfunction "GND_P$15") (pintype "bidirectional"))
      (node (ref "U4") (pin "P$16") (pinfunction "PMODE_P$16") (pintype "bidirectional"))
      (node (ref "U4") (pin "P$17") (pinfunction "GND_PAD_P$17") (pintype "bidirectional"))
      (node (ref "U4") (pin "P$7") (pinfunction "IMODE_P$7") (pintype "bidirectional"))
      (node (ref "U4") (pin "P$9") (pinfunction "PGND_P$9") (pintype "bidirectional"))
      (node (ref "U5") (pin "11") (pinfunction "SENSE_11") (pintype "bidirectional"))
      (node (ref "U5") (pin "12") (pinfunction "GND_12") (pintype "bidirectional"))
      (node (ref "U5") (pin "13") (pinfunction "GND_13") (pintype "bidirectional"))
      (node (ref "U5") (pin "4") (pinfunction "GND_4") (pintype "bidirectional"))
      (node (ref "U5") (pin "5") (pinfunction "GND_5") (pintype "bidirectional"))
      (node (ref "U6") (pin "P$3") (pinfunction "GND_P$3") (pintype "bidirectional"))
      (node (ref "U6") (pin "P$6") (pinfunction "GND1_P$6") (pintype "bidirectional"))
      (node (ref "U7") (pin "P$3") (pinfunction "GND_P$3") (pintype "bidirectional"))
      (node (ref "U7") (pin "P$6") (pinfunction "GND1_P$6") (pintype "bidirectional"))
      (node (ref "U8") (pin "2") (pinfunction "-IN_2") (pintype "input"))
      (node (ref "U8") (pin "4") (pinfunction "GND_4") (pintype "power_in"))
    )
    (net (code "31") (name "GPIO0") (class "Default")
      (node (ref "J122") (pin "P$1") (pinfunction "P$1_P$1") (pintype "bidirectional"))
      (node (ref "J122") (pin "P$2") (pinfunction "P$2_P$2") (pintype "bidirectional"))
      (node (ref "J122") (pin "P$3") (pinfunction "P$3_P$3") (pintype "bidirectional"))
      (node (ref "L1") (pin "P$40") (pinfunction "GPIO0/EPWM1A_P$40") (pintype "bidirectional"))
    )
    (net (code "32") (name "GPIO1") (class "Default")
      (node (ref "J121") (pin "P$1") (pinfunction "P$1_P$1") (pintype "bidirectional"))
      (node (ref "J121") (pin "P$2") (pinfunction "P$2_P$2") (pintype "bidirectional"))
      (node (ref "J121") (pin "P$3") (pinfunction "P$3_P$3") (pintype "bidirectional"))
      (node (ref "L1") (pin "P$39") (pinfunction "GPIO1/EPWM1B_P$39") (pintype "bidirectional"))
    )
    (net (code "33") (name "GPIO2") (class "Default")
      (node (ref "J120") (pin "P$1") (pinfunction "P$1_P$1") (pintype "bidirectional"))
      (node (ref "J120") (pin "P$2") (pinfunction "P$2_P$2") (pintype "bidirectional"))
      (node (ref "J120") (pin "P$3") (pinfunction "P$3_P$3") (pintype "bidirectional"))
      (node (ref "J198") (pin "P$1") (pinfunction "P$1_P$1") (pintype "bidirectional"))
      (node (ref "J198") (pin "P$2") (pinfunction "P$2_P$2") (pintype "bidirectional"))
      (node (ref "L1") (pin "P$38") (pinfunction "GPIO2/EPWM2A_P$38") (pintype "bidirectional"))
    )
    (net (code "34") (name "GPIO3") (class "Default")
      (node (ref "J119") (pin "P$1") (pinfunction "P$1_P$1") (pintype "bidirectional"))
      (node (ref "J119") (pin "P$2") (pinfunction "P$2_P$2") (pintype "bidirectional"))
      (node (ref "J119") (pin "P$3") (pinfunction "P$3_P$3") (pintype "bidirectional"))
      (node (ref "J199") (pin "P$1") (pinfunction "P$1_P$1") (pintype "bidirectional"))
      (node (ref "J199") (pin "P$2") (pinfunction "P$2_P$2") (pintype "bidirectional"))
      (node (ref "L1") (pin "P$37") (pinfunction "GPIO3/EPWM2B_P$37") (pintype "bidirectional"))
    )
    (net (code "35") (name "GPIO4") (class "Default")
      (node (ref "J118") (pin "P$1") (pinfunction "P$1_P$1") (pintype "bidirectional"))
      (node (ref "J118") (pin "P$2") (pinfunction "P$2_P$2") (pintype "bidirectional"))
      (node (ref "J118") (pin "P$3") (pinfunction "P$3_P$3") (pintype "bidirectional"))
      (node (ref "J238") (pin "P$1") (pinfunction "P$1_P$1") (pintype "bidirectional"))
      (node (ref "J238") (pin "P$2") (pinfunction "P$2_P$2") (pintype "bidirectional"))
      (node (ref "L1") (pin "P$36") (pinfunction "GPIO4/EPWM3A_P$36") (pintype "bidirectional"))
    )
    (net (code "36") (name "GPIO5") (class "Default")
      (node (ref "J117") (pin "P$1") (pinfunction "P$1_P$1") (pintype "bidirectional"))
      (node (ref "J117") (pin "P$2") (pinfunction "P$2_P$2") (pintype "bidirectional"))
      (node (ref "J117") (pin "P$3") (pinfunction "P$3_P$3") (pintype "bidirectional"))
      (node (ref "J239") (pin "P$1") (pinfunction "P$1_P$1") (pintype "bidirectional"))
      (node (ref "J239") (pin "P$2") (pinfunction "P$2_P$2") (pintype "bidirectional"))
      (node (ref "L1") (pin "P$35") (pinfunction "GPIO5/EPWM3B_P$35") (pintype "bidirectional"))
    )
    (net (code "37") (name "GPIO6") (class "Default")
      (node (ref "J133") (pin "P$1") (pinfunction "P$1_P$1") (pintype "bidirectional"))
      (node (ref "J133") (pin "P$2") (pinfunction "P$2_P$2") (pintype "bidirectional"))
      (node (ref "J133") (pin "P$3") (pinfunction "P$3_P$3") (pintype "bidirectional"))
      (node (ref "J240") (pin "P$1") (pinfunction "P$1_P$1") (pintype "bidirectional"))
      (node (ref "J240") (pin "P$2") (pinfunction "P$2_P$2") (pintype "bidirectional"))
      (node (ref "L1") (pin "P$80") (pinfunction "GPIO6/EPWM4A_P$80") (pintype "bidirectional"))
    )
    (net (code "38") (name "GPIO7") (class "Default")
      (node (ref "J134") (pin "P$1") (pinfunction "P$1_P$1") (pintype "bidirectional"))
      (node (ref "J134") (pin "P$2") (pinfunction "P$2_P$2") (pintype "bidirectional"))
      (node (ref "J134") (pin "P$3") (pinfunction "P$3_P$3") (pintype "bidirectional"))
      (node (ref "J242") (pin "P$1") (pinfunction "P$1_P$1") (pintype "bidirectional"))
      (node (ref "J242") (pin "P$2") (pinfunction "P$2_P$2") (pintype "bidirectional"))
      (node (ref "L1") (pin "P$79") (pinfunction "GPIO7/EPWM4B_P$79") (pintype "bidirectional"))
    )
    (net (code "39") (name "GPIO8") (class "Default")
      (node (ref "J135") (pin "P$1") (pinfunction "P$1_P$1") (pintype "bidirectional"))
      (node (ref "J135") (pin "P$2") (pinfunction "P$2_P$2") (pintype "bidirectional"))
      (node (ref "J135") (pin "P$3") (pinfunction "P$3_P$3") (pintype "bidirectional"))
      (node (ref "J243") (pin "P$1") (pinfunction "P$1_P$1") (pintype "bidirectional"))
      (node (ref "J243") (pin "P$2") (pinfunction "P$2_P$2") (pintype "bidirectional"))
      (node (ref "L1") (pin "P$78") (pinfunction "GPIO8/EPWM5A_P$78") (pintype "bidirectional"))
    )
    (net (code "40") (name "GPIO9") (class "Default")
      (node (ref "J136") (pin "P$1") (pinfunction "P$1_P$1") (pintype "bidirectional"))
      (node (ref "J136") (pin "P$2") (pinfunction "P$2_P$2") (pintype "bidirectional"))
      (node (ref "J136") (pin "P$3") (pinfunction "P$3_P$3") (pintype "bidirectional"))
      (node (ref "J244") (pin "P$1") (pinfunction "P$1_P$1") (pintype "bidirectional"))
      (node (ref "J244") (pin "P$2") (pinfunction "P$2_P$2") (pintype "bidirectional"))
      (node (ref "L1") (pin "P$77") (pinfunction "GPIO9/EPWM5B_P$77") (pintype "bidirectional"))
    )
    (net (code "41") (name "GPIO10") (class "Default")
      (node (ref "J137") (pin "P$1") (pinfunction "P$1_P$1") (pintype "bidirectional"))
      (node (ref "J137") (pin "P$2") (pinfunction "P$2_P$2") (pintype "bidirectional"))
      (node (ref "J137") (pin "P$3") (pinfunction "P$3_P$3") (pintype "bidirectional"))
      (node (ref "J84") (pin "P$1") (pinfunction "P$1_P$1") (pintype "bidirectional"))
      (node (ref "J84") (pin "P$2") (pinfunction "P$2_P$2") (pintype "bidirectional"))
      (node (ref "L1") (pin "P$76") (pinfunction "GPIO10/EPWM6A_P$76") (pintype "bidirectional"))
    )
    (net (code "42") (name "GPIO11") (class "Default")
      (node (ref "J138") (pin "P$1") (pinfunction "P$1_P$1") (pintype "bidirectional"))
      (node (ref "J138") (pin "P$2") (pinfunction "P$2_P$2") (pintype "bidirectional"))
      (node (ref "J138") (pin "P$3") (pinfunction "P$3_P$3") (pintype "bidirectional"))
      (node (ref "J86") (pin "P$1") (pinfunction "P$1_P$1") (pintype "bidirectional"))
      (node (ref "J86") (pin "P$2") (pinfunction "P$2_P$2") (pintype "bidirectional"))
      (node (ref "L1") (pin "P$75") (pinfunction "GPIO11/EPWM6B_P$75") (pintype "bidirectional"))
    )
    (net (code "43") (name "GPIO14") (class "Default")
      (node (ref "J139") (pin "P$1") (pinfunction "P$1_P$1") (pintype "bidirectional"))
      (node (ref "J139") (pin "P$2") (pinfunction "P$2_P$2") (pintype "bidirectional"))
      (node (ref "J139") (pin "P$3") (pinfunction "P$3_P$3") (pintype "bidirectional"))
      (node (ref "J201") (pin "P$1") (pinfunction "P$1_P$1") (pintype "bidirectional"))
      (node (ref "J201") (pin "P$2") (pinfunction "P$2_P$2") (pintype "bidirectional"))
      (node (ref "L1") (pin "P$74") (pinfunction "GPIO14_P$74") (pintype "bidirectional"))
    )
    (net (code "44") (name "GPIO15") (class "Default")
      (node (ref "J140") (pin "P$1") (pinfunction "P$1_P$1") (pintype "bidirectional"))
      (node (ref "J140") (pin "P$2") (pinfunction "P$2_P$2") (pintype "bidirectional"))
      (node (ref "J140") (pin "P$3") (pinfunction "P$3_P$3") (pintype "bidirectional"))
      (node (ref "J202") (pin "P$1") (pinfunction "P$1_P$1") (pintype "bidirectional"))
      (node (ref "J202") (pin "P$2") (pinfunction "P$2_P$2") (pintype "bidirectional"))
      (node (ref "L1") (pin "P$73") (pinfunction "GPIO15_P$73") (pintype "bidirectional"))
    )
    (net (code "45") (name "GPIO16") (class "Default")
      (node (ref "J115") (pin "P$1") (pinfunction "P$1_P$1") (pintype "bidirectional"))
      (node (ref "J115") (pin "P$2") (pinfunction "P$2_P$2") (pintype "bidirectional"))
      (node (ref "J115") (pin "P$3") (pinfunction "P$3_P$3") (pintype "bidirectional"))
      (node (ref "J251") (pin "P$1") (pinfunction "P$1_P$1") (pintype "bidirectional"))
      (node (ref "J251") (pin "P$2") (pinfunction "P$2_P$2") (pintype "bidirectional"))
      (node (ref "L1") (pin "P$33") (pinfunction "GPIO16_P$33") (pintype "bidirectional"))
    )
    (net (code "46") (name "GPIO18") (class "Default")
      (node (ref "J16") (pin "P$1") (pinfunction "P$1_P$1") (pintype "bidirectional"))
      (node (ref "J16") (pin "P$2") (pinfunction "P$2_P$2") (pintype "bidirectional"))
      (node (ref "J16") (pin "P$3") (pinfunction "P$3_P$3") (pintype "bidirectional"))
      (node (ref "L1") (pin "P$4") (pinfunction "GPIO18/SCITXDB_P$4") (pintype "bidirectional"))
    )
    (net (code "47") (name "GPIO19") (class "Default")
      (node (ref "J15") (pin "P$1") (pinfunction "P$1_P$1") (pintype "bidirectional"))
      (node (ref "J15") (pin "P$2") (pinfunction "P$2_P$2") (pintype "bidirectional"))
      (node (ref "J15") (pin "P$3") (pinfunction "P$3_P$3") (pintype "bidirectional"))
      (node (ref "L1") (pin "P$3") (pinfunction "GPIO19/SCIRXDB_P$3") (pintype "bidirectional"))
    )
    (net (code "48") (name "GPIO22") (class "Default")
      (node (ref "J20") (pin "P$1") (pinfunction "P$1_P$1") (pintype "bidirectional"))
      (node (ref "J20") (pin "P$2") (pinfunction "P$2_P$2") (pintype "bidirectional"))
      (node (ref "J20") (pin "P$3") (pinfunction "P$3_P$3") (pintype "bidirectional"))
      (node (ref "J210") (pin "P$1") (pinfunction "P$1_P$1") (pintype "bidirectional"))
      (node (ref "J210") (pin "P$2") (pinfunction "P$2_P$2") (pintype "bidirectional"))
      (node (ref "L1") (pin "P$8") (pinfunction "GPIO22_P$8") (pintype "bidirectional"))
    )
    (net (code "49") (name "GPIO24") (class "Default")
      (node (ref "J116") (pin "P$1") (pinfunction "P$1_P$1") (pintype "bidirectional"))
      (node (ref "J116") (pin "P$2") (pinfunction "P$2_P$2") (pintype "bidirectional"))
      (node (ref "J116") (pin "P$3") (pinfunction "P$3_P$3") (pintype "bidirectional"))
      (node (ref "J245") (pin "P$1") (pinfunction "P$1_P$1") (pintype "bidirectional"))
      (node (ref "J245") (pin "P$2") (pinfunction "P$2_P$2") (pintype "bidirectional"))
      (node (ref "L1") (pin "P$34") (pinfunction "GPIO24_P$34") (pintype "bidirectional"))
    )
    (net (code "50") (name "GPIO25") (class "Default")
      (node (ref "J162") (pin "P$1") (pinfunction "P$1_P$1") (pintype "bidirectional"))
      (node (ref "J162") (pin "P$2") (pinfunction "P$2_P$2") (pintype "bidirectional"))
      (node (ref "J162") (pin "P$3") (pinfunction "P$3_P$3") (pintype "bidirectional"))
      (node (ref "J246") (pin "P$1") (pinfunction "P$1_P$1") (pintype "bidirectional"))
      (node (ref "J246") (pin "P$2") (pinfunction "P$2_P$2") (pintype "bidirectional"))
      (node (ref "L1") (pin "P$51") (pinfunction "GPIO25_P$51") (pintype "bidirectional"))
    )
    (net (code "51") (name "GPIO26") (class "Default")
      (node (ref "J160") (pin "P$1") (pinfunction "P$1_P$1") (pintype "bidirectional"))
      (node (ref "J160") (pin "P$2") (pinfunction "P$2_P$2") (pintype "bidirectional"))
      (node (ref "J160") (pin "P$3") (pinfunction "P$3_P$3") (pintype "bidirectional"))
      (node (ref "J247") (pin "P$1") (pinfunction "P$1_P$1") (pintype "bidirectional"))
      (node (ref "J247") (pin "P$2") (pinfunction "P$2_P$2") (pintype "bidirectional"))
      (node (ref "L1") (pin "P$53") (pinfunction "GPIO26_P$53") (pintype "bidirectional"))
    )
    (net (code "52") (name "GPIO27") (class "Default")
      (node (ref "J161") (pin "P$1") (pinfunction "P$1_P$1") (pintype "bidirectional"))
      (node (ref "J161") (pin "P$2") (pinfunction "P$2_P$2") (pintype "bidirectional"))
      (node (ref "J161") (pin "P$3") (pinfunction "P$3_P$3") (pintype "bidirectional"))
      (node (ref "J248") (pin "P$1") (pinfunction "P$1_P$1") (pintype "bidirectional"))
      (node (ref "J248") (pin "P$2") (pinfunction "P$2_P$2") (pintype "bidirectional"))
      (node (ref "L1") (pin "P$52") (pinfunction "GPIO27_P$52") (pintype "bidirectional"))
    )
    (net (code "53") (name "GPIO29") (class "Default")
      (node (ref "J29") (pin "P$1") (pinfunction "P$1_P$1") (pintype "bidirectional"))
      (node (ref "J29") (pin "P$2") (pinfunction "P$2_P$2") (pintype "bidirectional"))
      (node (ref "J29") (pin "P$3") (pinfunction "P$3_P$3") (pintype "bidirectional"))
      (node (ref "J85") (pin "P$1") (pinfunction "P$1_P$1") (pintype "bidirectional"))
      (node (ref "J85") (pin "P$2") (pinfunction "P$2_P$2") (pintype "bidirectional"))
      (node (ref "L1") (pin "P$11") (pinfunction "GPIO29_P$11") (pintype "bidirectional"))
    )
    (net (code "54") (name "GPIO32") (class "Default")
      (node (ref "J14") (pin "P$1") (pinfunction "P$1_P$1") (pintype "bidirectional"))
      (node (ref "J14") (pin "P$2") (pinfunction "P$2_P$2") (pintype "bidirectional"))
      (node (ref "J14") (pin "P$3") (pinfunction "P$3_P$3") (pintype "bidirectional"))
      (node (ref "J87") (pin "P$1") (pinfunction "P$1_P$1") (pintype "bidirectional"))
      (node (ref "J87") (pin "P$2") (pinfunction "P$2_P$2") (pintype "bidirectional"))
      (node (ref "L1") (pin "P$2") (pinfunction "GPIO32_P$2") (pintype "bidirectional"))
    )
    (net (code "55") (name "GPIO40") (class "Default")
      (node (ref "J163") (pin "P$1") (pinfunction "P$1_P$1") (pintype "bidirectional"))
      (node (ref "J163") (pin "P$2") (pinfunction "P$2_P$2") (pintype "bidirectional"))
      (node (ref "J163") (pin "P$3") (pinfunction "P$3_P$3") (pintype "bidirectional"))
      (node (ref "J208") (pin "P$1") (pinfunction "P$1_P$1") (pintype "bidirectional"))
      (node (ref "J208") (pin "P$2") (pinfunction "P$2_P$2") (pintype "bidirectional"))
      (node (ref "L1") (pin "P$50") (pinfunction "GPIO40/SDAB_P$50") (pintype "bidirectional"))
    )
    (net (code "56") (name "GPIO41") (class "Default")
      (node (ref "J164") (pin "P$1") (pinfunction "P$1_P$1") (pintype "bidirectional"))
      (node (ref "J164") (pin "P$2") (pinfunction "P$2_P$2") (pintype "bidirectional"))
      (node (ref "J164") (pin "P$3") (pinfunction "P$3_P$3") (pintype "bidirectional"))
      (node (ref "J209") (pin "P$1") (pinfunction "P$1_P$1") (pintype "bidirectional"))
      (node (ref "J209") (pin "P$2") (pinfunction "P$2_P$2") (pintype "bidirectional"))
      (node (ref "L1") (pin "P$49") (pinfunction "GPIO41/SCLB_P$49") (pintype "bidirectional"))
    )
    (net (code "57") (name "GPIO52") (class "Default")
      (node (ref "J165") (pin "P$1") (pinfunction "P$1_P$1") (pintype "bidirectional"))
      (node (ref "J165") (pin "P$2") (pinfunction "P$2_P$2") (pintype "bidirectional"))
      (node (ref "J165") (pin "P$3") (pinfunction "P$3_P$3") (pintype "bidirectional"))
      (node (ref "J211") (pin "P$1") (pinfunction "P$1_P$1") (pintype "bidirectional"))
      (node (ref "J211") (pin "P$2") (pinfunction "P$2_P$2") (pintype "bidirectional"))
      (node (ref "L1") (pin "P$48") (pinfunction "GPIO52_P$48") (pintype "bidirectional"))
    )
    (net (code "58") (name "GPIO56") (class "Default")
      (node (ref "J169") (pin "P$1") (pinfunction "P$1_P$1") (pintype "bidirectional"))
      (node (ref "J169") (pin "P$2") (pinfunction "P$2_P$2") (pintype "bidirectional"))
      (node (ref "J169") (pin "P$3") (pinfunction "P$3_P$3") (pintype "bidirectional"))
      (node (ref "L1") (pin "P$44") (pinfunction "GPIO56/SCITXDC_P$44") (pintype "bidirectional"))
    )
    (net (code "59") (name "GPIO58") (class "Default")
      (node (ref "J33") (pin "P$1") (pinfunction "P$1_P$1") (pintype "bidirectional"))
      (node (ref "J33") (pin "P$2") (pinfunction "P$2_P$2") (pintype "bidirectional"))
      (node (ref "J33") (pin "P$3") (pinfunction "P$3_P$3") (pintype "bidirectional"))
      (node (ref "L1") (pin "P$15") (pinfunction "GPIO58/SPISIMOA_P$15") (pintype "bidirectional"))
    )
    (net (code "60") (name "GPIO59") (class "Default")
      (node (ref "J32") (pin "P$1") (pinfunction "P$1_P$1") (pintype "bidirectional"))
      (node (ref "J32") (pin "P$2") (pinfunction "P$2_P$2") (pintype "bidirectional"))
      (node (ref "J32") (pin "P$3") (pinfunction "P$3_P$3") (pintype "bidirectional"))
      (node (ref "L1") (pin "P$14") (pinfunction "GPIO59/SPISOMIA_P$14") (pintype "bidirectional"))
    )
    (net (code "61") (name "GPIO60") (class "Default")
      (node (ref "J19") (pin "P$1") (pinfunction "P$1_P$1") (pintype "bidirectional"))
      (node (ref "J19") (pin "P$2") (pinfunction "P$2_P$2") (pintype "bidirectional"))
      (node (ref "J19") (pin "P$3") (pinfunction "P$3_P$3") (pintype "bidirectional"))
      (node (ref "J249") (pin "P$1") (pinfunction "P$1_P$1") (pintype "bidirectional"))
      (node (ref "J249") (pin "P$2") (pinfunction "P$2_P$2") (pintype "bidirectional"))
      (node (ref "L1") (pin "P$7") (pinfunction "GPIO60/SPICLKA_P$7") (pintype "bidirectional"))
    )
    (net (code "62") (name "GPIO61") (class "Default")
      (node (ref "J101") (pin "P$1") (pinfunction "P$1_P$1") (pintype "bidirectional"))
      (node (ref "J101") (pin "P$2") (pinfunction "P$2_P$2") (pintype "bidirectional"))
      (node (ref "J101") (pin "P$3") (pinfunction "P$3_P$3") (pintype "bidirectional"))
      (node (ref "J250") (pin "P$1") (pinfunction "P$1_P$1") (pintype "bidirectional"))
      (node (ref "J250") (pin "P$2") (pinfunction "P$2_P$2") (pintype "bidirectional"))
      (node (ref "L1") (pin "P$19") (pinfunction "GPIO61_P$19") (pintype "bidirectional"))
    )
    (net (code "63") (name "GPIO63") (class "Default")
      (node (ref "J158") (pin "P$1") (pinfunction "P$1_P$1") (pintype "bidirectional"))
      (node (ref "J158") (pin "P$2") (pinfunction "P$2_P$2") (pintype "bidirectional"))
      (node (ref "J158") (pin "P$3") (pinfunction "P$3_P$3") (pintype "bidirectional"))
      (node (ref "J204") (pin "P$1") (pinfunction "P$1_P$1") (pintype "bidirectional"))
      (node (ref "J204") (pin "P$2") (pinfunction "P$2_P$2") (pintype "bidirectional"))
      (node (ref "L1") (pin "P$55") (pinfunction "GPIO63/SPISIMOB_P$55") (pintype "bidirectional"))
    )
    (net (code "64") (name "GPIO64") (class "Default")
      (node (ref "J159") (pin "P$1") (pinfunction "P$1_P$1") (pintype "bidirectional"))
      (node (ref "J159") (pin "P$2") (pinfunction "P$2_P$2") (pintype "bidirectional"))
      (node (ref "J159") (pin "P$3") (pinfunction "P$3_P$3") (pintype "bidirectional"))
      (node (ref "J205") (pin "P$1") (pinfunction "P$1_P$1") (pintype "bidirectional"))
      (node (ref "J205") (pin "P$2") (pinfunction "P$2_P$2") (pintype "bidirectional"))
      (node (ref "L1") (pin "P$54") (pinfunction "GPIO64/SPISOMIB_P$54") (pintype "bidirectional"))
    )
    (net (code "65") (name "GPIO65") (class "Default")
      (node (ref "J166") (pin "P$1") (pinfunction "P$1_P$1") (pintype "bidirectional"))
      (node (ref "J166") (pin "P$2") (pinfunction "P$2_P$2") (pintype "bidirectional"))
      (node (ref "J166") (pin "P$3") (pinfunction "P$3_P$3") (pintype "bidirectional"))
      (node (ref "J206") (pin "P$1") (pinfunction "P$1_P$1") (pintype "bidirectional"))
      (node (ref "J206") (pin "P$2") (pinfunction "P$2_P$2") (pintype "bidirectional"))
      (node (ref "L1") (pin "P$47") (pinfunction "GPIO65/SPICLKB_P$47") (pintype "bidirectional"))
    )
    (net (code "66") (name "GPIO66") (class "Default")
      (node (ref "J154") (pin "P$1") (pinfunction "P$1_P$1") (pintype "bidirectional"))
      (node (ref "J154") (pin "P$2") (pinfunction "P$2_P$2") (pintype "bidirectional"))
      (node (ref "J154") (pin "P$3") (pinfunction "P$3_P$3") (pintype "bidirectional"))
      (node (ref "J207") (pin "P$1") (pinfunction "P$1_P$1") (pintype "bidirectional"))
      (node (ref "J207") (pin "P$2") (pinfunction "P$2_P$2") (pintype "bidirectional"))
      (node (ref "L1") (pin "P$59") (pinfunction "GPIO66_P$59") (pintype "bidirectional"))
    )
    (net (code "67") (name "GPIO67") (class "Default")
      (node (ref "J17") (pin "P$1") (pinfunction "P$1_P$1") (pintype "bidirectional"))
      (node (ref "J17") (pin "P$2") (pinfunction "P$2_P$2") (pintype "bidirectional"))
      (node (ref "J17") (pin "P$3") (pinfunction "P$3_P$3") (pintype "bidirectional"))
      (node (ref "J232") (pin "P$1") (pinfunction "P$1_P$1") (pintype "bidirectional"))
      (node (ref "J232") (pin "P$2") (pinfunction "P$2_P$2") (pintype "bidirectional"))
      (node (ref "L1") (pin "P$5") (pinfunction "GPIO67_P$5") (pintype "bidirectional"))
    )
    (net (code "68") (name "GPIO94") (class "Default")
      (node (ref "J167") (pin "P$1") (pinfunction "P$1_P$1") (pintype "bidirectional"))
      (node (ref "J167") (pin "P$2") (pinfunction "P$2_P$2") (pintype "bidirectional"))
      (node (ref "J167") (pin "P$3") (pinfunction "P$3_P$3") (pintype "bidirectional"))
      (node (ref "J233") (pin "P$1") (pinfunction "P$1_P$1") (pintype "bidirectional"))
      (node (ref "J233") (pin "P$2") (pinfunction "P$2_P$2") (pintype "bidirectional"))
      (node (ref "L1") (pin "P$46") (pinfunction "GPIO94_P$46") (pintype "bidirectional"))
    )
    (net (code "69") (name "GPIO95") (class "Default")
      (node (ref "J176") (pin "P$1") (pinfunction "P$1_P$1") (pintype "bidirectional"))
      (node (ref "J176") (pin "P$2") (pinfunction "P$2_P$2") (pintype "bidirectional"))
      (node (ref "J176") (pin "P$3") (pinfunction "P$3_P$3") (pintype "bidirectional"))
      (node (ref "J241") (pin "P$1") (pinfunction "P$1_P$1") (pintype "bidirectional"))
      (node (ref "J241") (pin "P$2") (pinfunction "P$2_P$2") (pintype "bidirectional"))
      (node (ref "L1") (pin "P$42") (pinfunction "GPIO95_P$42") (pintype "bidirectional"))
    )
    (net (code "70") (name "GPIO97") (class "Default")
      (node (ref "J168") (pin "P$1") (pinfunction "P$1_P$1") (pintype "bidirectional"))
      (node (ref "J168") (pin "P$2") (pinfunction "P$2_P$2") (pintype "bidirectional"))
      (node (ref "J168") (pin "P$3") (pinfunction "P$3_P$3") (pintype "bidirectional"))
      (node (ref "J234") (pin "P$1") (pinfunction "P$1_P$1") (pintype "bidirectional"))
      (node (ref "J234") (pin "P$2") (pinfunction "P$2_P$2") (pintype "bidirectional"))
      (node (ref "L1") (pin "P$45") (pinfunction "GPIO97_P$45") (pintype "bidirectional"))
    )
    (net (code "71") (name "GPIO104") (class "Default")
      (node (ref "J28") (pin "P$1") (pinfunction "P$1_P$1") (pintype "bidirectional"))
      (node (ref "J28") (pin "P$2") (pinfunction "P$2_P$2") (pintype "bidirectional"))
      (node (ref "J28") (pin "P$3") (pinfunction "P$3_P$3") (pintype "bidirectional"))
      (node (ref "L1") (pin "P$10") (pinfunction "GPIO104/SDAA_P$10") (pintype "bidirectional"))
    )
    (net (code "72") (name "GPIO105") (class "Default")
      (node (ref "J21") (pin "P$1") (pinfunction "P$1_P$1") (pintype "bidirectional"))
      (node (ref "J21") (pin "P$2") (pinfunction "P$2_P$2") (pintype "bidirectional"))
      (node (ref "J21") (pin "P$3") (pinfunction "P$3_P$3") (pintype "bidirectional"))
      (node (ref "L1") (pin "P$9") (pinfunction "GPIO105/SCLA_P$9") (pintype "bidirectional"))
    )
    (net (code "73") (name "GPIO111") (class "Default")
      (node (ref "J18") (pin "P$1") (pinfunction "P$1_P$1") (pintype "bidirectional"))
      (node (ref "J18") (pin "P$2") (pinfunction "P$2_P$2") (pintype "bidirectional"))
      (node (ref "J18") (pin "P$3") (pinfunction "P$3_P$3") (pintype "bidirectional"))
      (node (ref "J235") (pin "P$1") (pinfunction "P$1_P$1") (pintype "bidirectional"))
      (node (ref "J235") (pin "P$2") (pinfunction "P$2_P$2") (pintype "bidirectional"))
      (node (ref "L1") (pin "P$6") (pinfunction "GPIO111_P$6") (pintype "bidirectional"))
    )
    (net (code "74") (name "GPIO122") (class "Default")
      (node (ref "J66") (pin "P$1") (pinfunction "P$1_P$1") (pintype "bidirectional"))
      (node (ref "J66") (pin "P$2") (pinfunction "P$2_P$2") (pintype "bidirectional"))
      (node (ref "J99") (pin "P$1") (pinfunction "P$1_P$1") (pintype "bidirectional"))
      (node (ref "J99") (pin "P$2") (pinfunction "P$2_P$2") (pintype "bidirectional"))
      (node (ref "J99") (pin "P$3") (pinfunction "P$3_P$3") (pintype "bidirectional"))
      (node (ref "L1") (pin "P$17") (pinfunction "GPIO122_P$17") (pintype "bidirectional"))
    )
    (net (code "75") (name "GPIO123") (class "Default")
      (node (ref "J100") (pin "P$1") (pinfunction "P$1_P$1") (pintype "bidirectional"))
      (node (ref "J100") (pin "P$2") (pinfunction "P$2_P$2") (pintype "bidirectional"))
      (node (ref "J100") (pin "P$3") (pinfunction "P$3_P$3") (pintype "bidirectional"))
      (node (ref "J67") (pin "P$1") (pinfunction "P$1_P$1") (pintype "bidirectional"))
      (node (ref "J67") (pin "P$2") (pinfunction "P$2_P$2") (pintype "bidirectional"))
      (node (ref "L1") (pin "P$18") (pinfunction "GPIO123_P$18") (pintype "bidirectional"))
    )
    (net (code "76") (name "GPIO124") (class "Default")
      (node (ref "J31") (pin "P$1") (pinfunction "P$1_P$1") (pintype "bidirectional"))
      (node (ref "J31") (pin "P$2") (pinfunction "P$2_P$2") (pintype "bidirectional"))
      (node (ref "J31") (pin "P$3") (pinfunction "P$3_P$3") (pintype "bidirectional"))
      (node (ref "J68") (pin "P$1") (pinfunction "P$1_P$1") (pintype "bidirectional"))
      (node (ref "J68") (pin "P$2") (pinfunction "P$2_P$2") (pintype "bidirectional"))
      (node (ref "L1") (pin "P$13") (pinfunction "GPIO124_P$13") (pintype "bidirectional"))
    )
    (net (code "77") (name "GPIO125") (class "Default")
      (node (ref "J30") (pin "P$1") (pinfunction "P$1_P$1") (pintype "bidirectional"))
      (node (ref "J30") (pin "P$2") (pinfunction "P$2_P$2") (pintype "bidirectional"))
      (node (ref "J30") (pin "P$3") (pinfunction "P$3_P$3") (pintype "bidirectional"))
      (node (ref "J69") (pin "P$1") (pinfunction "P$1_P$1") (pintype "bidirectional"))
      (node (ref "J69") (pin "P$2") (pinfunction "P$2_P$2") (pintype "bidirectional"))
      (node (ref "L1") (pin "P$12") (pinfunction "GPIO125_P$12") (pintype "bidirectional"))
    )
    (net (code "78") (name "GPIO130") (class "Default")
      (node (ref "J156") (pin "P$1") (pinfunction "P$1_P$1") (pintype "bidirectional"))
      (node (ref "J156") (pin "P$2") (pinfunction "P$2_P$2") (pintype "bidirectional"))
      (node (ref "J156") (pin "P$3") (pinfunction "P$3_P$3") (pintype "bidirectional"))
      (node (ref "J236") (pin "P$1") (pinfunction "P$1_P$1") (pintype "bidirectional"))
      (node (ref "J236") (pin "P$2") (pinfunction "P$2_P$2") (pintype "bidirectional"))
      (node (ref "L1") (pin "P$57") (pinfunction "GPIO130_P$57") (pintype "bidirectional"))
    )
    (net (code "79") (name "GPIO131") (class "Default")
      (node (ref "J155") (pin "P$1") (pinfunction "P$1_P$1") (pintype "bidirectional"))
      (node (ref "J155") (pin "P$2") (pinfunction "P$2_P$2") (pintype "bidirectional"))
      (node (ref "J155") (pin "P$3") (pinfunction "P$3_P$3") (pintype "bidirectional"))
      (node (ref "J237") (pin "P$1") (pinfunction "P$1_P$1") (pintype "bidirectional"))
      (node (ref "J237") (pin "P$2") (pinfunction "P$2_P$2") (pintype "bidirectional"))
      (node (ref "L1") (pin "P$58") (pinfunction "GPIO131_P$58") (pintype "bidirectional"))
    )
    (net (code "80") (name "GPIO139") (class "Default")
      (node (ref "J170") (pin "P$1") (pinfunction "P$1_P$1") (pintype "bidirectional"))
      (node (ref "J170") (pin "P$2") (pinfunction "P$2_P$2") (pintype "bidirectional"))
      (node (ref "J170") (pin "P$3") (pinfunction "P$3_P$3") (pintype "bidirectional"))
      (node (ref "L1") (pin "P$43") (pinfunction "GPIO139/SCIRXDC_P$43") (pintype "bidirectional"))
    )
    (net (code "81") (name "MENABLE") (class "Default")
      (node (ref "S159") (pin "P$2") (pinfunction "P2_P$2") (pintype "bidirectional"))
      (node (ref "U1") (pin "8") (pinfunction "~{ENABLE}_8") (pintype "bidirectional"))
      (node (ref "U2") (pin "P$3") (pinfunction "NSLEEP_P$3") (pintype "bidirectional"))
      (node (ref "U4") (pin "P$3") (pinfunction "NSLEEP_P$3") (pintype "bidirectional"))
      (node (ref "U5") (pin "8") (pinfunction "~{ENABLE}_8") (pintype "bidirectional"))
    )
    (net (code "82") (name "MIC_OUT") (class "Default")
      (node (ref "J49") (pin "P$1") (pinfunction "P$1_P$1") (pintype "bidirectional"))
      (node (ref "J49") (pin "P$2") (pinfunction "P$2_P$2") (pintype "bidirectional"))
      (node (ref "J49") (pin "P$3") (pinfunction "P$3_P$3") (pintype "bidirectional"))
      (node (ref "U8") (pin "5") (pinfunction "OUT_5") (pintype "output"))
    )
    (net (code "83") (name "MOTOR1+") (class "Default")
      (node (ref "SV3") (pin "1") (pinfunction "1_1") (pintype "passive"))
      (node (ref "SV3") (pin "3") (pinfunction "3_3") (pintype "passive"))
      (node (ref "SV3") (pin "5") (pinfunction "5_5") (pintype "passive"))
      (node (ref "U1") (pin "15") (pinfunction "OUTB_15") (pintype "bidirectional"))
    )
    (net (code "84") (name "MOTOR1-") (class "Default")
      (node (ref "SV3") (pin "2") (pinfunction "2_2") (pintype "passive"))
      (node (ref "SV3") (pin "4") (pinfunction "4_4") (pintype "passive"))
      (node (ref "SV3") (pin "6") (pinfunction "6_6") (pintype "passive"))
      (node (ref "U1") (pin "10") (pinfunction "OUTA_10") (pintype "bidirectional"))
    )
    (net (code "85") (name "MOTOR2+") (class "Default")
      (node (ref "SV1") (pin "1") (pinfunction "1_1") (pintype "passive"))
      (node (ref "SV1") (pin "3") (pinfunction "3_3") (pintype "passive"))
      (node (ref "SV1") (pin "5") (pinfunction "5_5") (pintype "passive"))
      (node (ref "U5") (pin "15") (pinfunction "OUTB_15") (pintype "bidirectional"))
    )
    (net (code "86") (name "MOTOR2-") (class "Default")
      (node (ref "SV1") (pin "2") (pinfunction "2_2") (pintype "passive"))
      (node (ref "SV1") (pin "4") (pinfunction "4_4") (pintype "passive"))
      (node (ref "SV1") (pin "6") (pinfunction "6_6") (pintype "passive"))
      (node (ref "U5") (pin "10") (pinfunction "OUTA_10") (pintype "bidirectional"))
    )
    (net (code "87") (name "Net-(B1-PadP$1)") (class "Default")
      (node (ref "B1") (pin "P$1") (pinfunction "P$1_P$1") (pintype "bidirectional"))
      (node (ref "R40") (pin "2") (pinfunction "2_2") (pintype "passive"))
    )
    (net (code "88") (name "Net-(C18-Pad2)") (class "Default")
      (node (ref "C18") (pin "2") (pinfunction "2_2") (pintype "passive"))
      (node (ref "J7") (pin "P$1") (pinfunction "P$1_P$1") (pintype "bidirectional"))
      (node (ref "J7") (pin "P$2") (pinfunction "P$2_P$2") (pintype "bidirectional"))
    )
    (net (code "89") (name "Net-(C21-Pad+)") (class "Default")
      (node (ref "C21") (pin "+") (pinfunction "+_+") (pintype "passive"))
      (node (ref "R10") (pin "1") (pinfunction "1_1") (pintype "passive"))
    )
    (net (code "90") (name "Net-(IC1A-I)") (class "Default")
      (node (ref "IC1") (pin "1") (pinfunction "I_1") (pintype "input"))
      (node (ref "J178") (pin "P$1") (pinfunction "P$1_P$1") (pintype "bidirectional"))
      (node (ref "J178") (pin "P$2") (pinfunction "P$2_P$2") (pintype "bidirectional"))
    )
    (net (code "91") (name "Net-(IC1A-O)") (class "Default")
      (node (ref "IC1") (pin "2") (pinfunction "O_2") (pintype "output"))
      (node (ref "LED1") (pin "K") (pinfunction "C_K") (pintype "passive"))
    )
    (net (code "92") (name "Net-(IC1B-I)") (class "Default")
      (node (ref "IC1") (pin "3") (pinfunction "I_3") (pintype "input"))
      (node (ref "J179") (pin "P$1") (pinfunction "P$1_P$1") (pintype "bidirectional"))
      (node (ref "J179") (pin "P$2") (pinfunction "P$2_P$2") (pintype "bidirectional"))
    )
    (net (code "93") (name "Net-(IC1B-O)") (class "Default")
      (node (ref "IC1") (pin "4") (pinfunction "O_4") (pintype "output"))
      (node (ref "LED2") (pin "K") (pinfunction "C_K") (pintype "passive"))
    )
    (net (code "94") (name "Net-(IC1C-I)") (class "Default")
      (node (ref "IC1") (pin "5") (pinfunction "I_5") (pintype "input"))
      (node (ref "J180") (pin "P$1") (pinfunction "P$1_P$1") (pintype "bidirectional"))
      (node (ref "J180") (pin "P$2") (pinfunction "P$2_P$2") (pintype "bidirectional"))
    )
    (net (code "95") (name "Net-(IC1C-O)") (class "Default")
      (node (ref "IC1") (pin "6") (pinfunction "O_6") (pintype "output"))
      (node (ref "LED3") (pin "K") (pinfunction "C_K") (pintype "passive"))
    )
    (net (code "96") (name "Net-(IC1D-I)") (class "Default")
      (node (ref "IC1") (pin "9") (pinfunction "I_9") (pintype "input"))
      (node (ref "J182") (pin "P$1") (pinfunction "P$1_P$1") (pintype "bidirectional"))
      (node (ref "J182") (pin "P$2") (pinfunction "P$2_P$2") (pintype "bidirectional"))
    )
    (net (code "97") (name "Net-(IC1D-O)") (class "Default")
      (node (ref "IC1") (pin "8") (pinfunction "O_8") (pintype "output"))
      (node (ref "LED4") (pin "K") (pinfunction "C_K") (pintype "passive"))
    )
    (net (code "98") (name "Net-(IC1E-I)") (class "Default")
      (node (ref "IC1") (pin "11") (pinfunction "I_11") (pintype "input"))
      (node (ref "J183") (pin "P$1") (pinfunction "P$1_P$1") (pintype "bidirectional"))
      (node (ref "J183") (pin "P$2") (pinfunction "P$2_P$2") (pintype "bidirectional"))
    )
    (net (code "99") (name "Net-(IC1E-O)") (class "Default")
      (node (ref "IC1") (pin "10") (pinfunction "O_10") (pintype "output"))
      (node (ref "LED5") (pin "K") (pinfunction "C_K") (pintype "passive"))
    )
    (net (code "100") (name "Net-(IC1F-I)") (class "Default")
      (node (ref "IC1") (pin "13") (pinfunction "I_13") (pintype "input"))
      (node (ref "J184") (pin "P$1") (pinfunction "P$1_P$1") (pintype "bidirectional"))
      (node (ref "J184") (pin "P$2") (pinfunction "P$2_P$2") (pintype "bidirectional"))
    )
    (net (code "101") (name "Net-(IC1F-O)") (class "Default")
      (node (ref "IC1") (pin "12") (pinfunction "O_12") (pintype "output"))
      (node (ref "LED6") (pin "K") (pinfunction "C_K") (pintype "passive"))
    )
    (net (code "102") (name "Net-(IC2A-I)") (class "Default")
      (node (ref "IC2") (pin "1") (pinfunction "I_1") (pintype "input"))
      (node (ref "J26") (pin "P$1") (pinfunction "P$1_P$1") (pintype "bidirectional"))
      (node (ref "J26") (pin "P$2") (pinfunction "P$2_P$2") (pintype "bidirectional"))
    )
    (net (code "103") (name "Net-(IC2A-O)") (class "Default")
      (node (ref "IC2") (pin "2") (pinfunction "O_2") (pintype "output"))
      (node (ref "LED7") (pin "K") (pinfunction "C_K") (pintype "passive"))
    )
    (net (code "104") (name "Net-(IC2B-I)") (class "Default")
      (node (ref "IC2") (pin "3") (pinfunction "I_3") (pintype "input"))
      (node (ref "J11") (pin "P$1") (pinfunction "P$1_P$1") (pintype "bidirectional"))
      (node (ref "J11") (pin "P$2") (pinfunction "P$2_P$2") (pintype "bidirectional"))
    )
    (net (code "105") (name "Net-(IC2B-O)") (class "Default")
      (node (ref "IC2") (pin "4") (pinfunction "O_4") (pintype "output"))
      (node (ref "LED8") (pin "K") (pinfunction "C_K") (pintype "passive"))
    )
    (net (code "106") (name "Net-(IC2C-I)") (class "Default")
      (node (ref "IC2") (pin "5") (pinfunction "I_5") (pintype "input"))
      (node (ref "J12") (pin "P$1") (pinfunction "P$1_P$1") (pintype "bidirectional"))
      (node (ref "J12") (pin "P$2") (pinfunction "P$2_P$2") (pintype "bidirectional"))
    )
    (net (code "107") (name "Net-(IC2C-O)") (class "Default")
      (node (ref "IC2") (pin "6") (pinfunction "O_6") (pintype "output"))
      (node (ref "LED9") (pin "K") (pinfunction "C_K") (pintype "passive"))
    )
    (net (code "108") (name "Net-(IC2D-I)") (class "Default")
      (node (ref "IC2") (pin "9") (pinfunction "I_9") (pintype "input"))
      (node (ref "J13") (pin "P$1") (pinfunction "P$1_P$1") (pintype "bidirectional"))
      (node (ref "J13") (pin "P$2") (pinfunction "P$2_P$2") (pintype "bidirectional"))
    )
    (net (code "109") (name "Net-(IC2D-O)") (class "Default")
      (node (ref "IC2") (pin "8") (pinfunction "O_8") (pintype "output"))
      (node (ref "LED10") (pin "K") (pinfunction "C_K") (pintype "passive"))
    )
    (net (code "110") (name "Net-(IC2E-I)") (class "Default")
      (node (ref "IC2") (pin "11") (pinfunction "I_11") (pintype "input"))
      (node (ref "J22") (pin "P$1") (pinfunction "P$1_P$1") (pintype "bidirectional"))
      (node (ref "J22") (pin "P$2") (pinfunction "P$2_P$2") (pintype "bidirectional"))
    )
    (net (code "111") (name "Net-(IC2E-O)") (class "Default")
      (node (ref "IC2") (pin "10") (pinfunction "O_10") (pintype "output"))
      (node (ref "LED11") (pin "K") (pinfunction "C_K") (pintype "passive"))
    )
    (net (code "112") (name "Net-(IC2F-I)") (class "Default")
      (node (ref "IC2") (pin "13") (pinfunction "I_13") (pintype "input"))
      (node (ref "J25") (pin "P$1") (pinfunction "P$1_P$1") (pintype "bidirectional"))
      (node (ref "J25") (pin "P$2") (pinfunction "P$2_P$2") (pintype "bidirectional"))
    )
    (net (code "113") (name "Net-(IC2F-O)") (class "Default")
      (node (ref "IC2") (pin "12") (pinfunction "O_12") (pintype "output"))
      (node (ref "LED12") (pin "K") (pinfunction "C_K") (pintype "passive"))
    )
    (net (code "114") (name "Net-(IC3A-I)") (class "Default")
      (node (ref "IC3") (pin "1") (pinfunction "I_1") (pintype "input"))
      (node (ref "J189") (pin "P$1") (pinfunction "P$1_P$1") (pintype "bidirectional"))
      (node (ref "J189") (pin "P$2") (pinfunction "P$2_P$2") (pintype "bidirectional"))
    )
    (net (code "115") (name "Net-(IC3A-O)") (class "Default")
      (node (ref "IC3") (pin "2") (pinfunction "O_2") (pintype "output"))
      (node (ref "LED13") (pin "K") (pinfunction "C_K") (pintype "passive"))
    )
    (net (code "116") (name "Net-(IC3B-I)") (class "Default")
      (node (ref "IC3") (pin "3") (pinfunction "I_3") (pintype "input"))
      (node (ref "J27") (pin "P$1") (pinfunction "P$1_P$1") (pintype "bidirectional"))
      (node (ref "J27") (pin "P$2") (pinfunction "P$2_P$2") (pintype "bidirectional"))
    )
    (net (code "117") (name "Net-(IC3B-O)") (class "Default")
      (node (ref "IC3") (pin "4") (pinfunction "O_4") (pintype "output"))
      (node (ref "LED14") (pin "K") (pinfunction "C_K") (pintype "passive"))
    )
    (net (code "118") (name "Net-(IC3C-I)") (class "Default")
      (node (ref "IC3") (pin "5") (pinfunction "I_5") (pintype "input"))
      (node (ref "J34") (pin "P$1") (pinfunction "P$1_P$1") (pintype "bidirectional"))
      (node (ref "J34") (pin "P$2") (pinfunction "P$2_P$2") (pintype "bidirectional"))
    )
    (net (code "119") (name "Net-(IC3C-O)") (class "Default")
      (node (ref "IC3") (pin "6") (pinfunction "O_6") (pintype "output"))
      (node (ref "LED15") (pin "K") (pinfunction "C_K") (pintype "passive"))
    )
    (net (code "120") (name "Net-(IC3D-I)") (class "Default")
      (node (ref "IC3") (pin "9") (pinfunction "I_9") (pintype "input"))
      (node (ref "J186") (pin "P$1") (pinfunction "P$1_P$1") (pintype "bidirectional"))
      (node (ref "J186") (pin "P$2") (pinfunction "P$2_P$2") (pintype "bidirectional"))
    )
    (net (code "121") (name "Net-(IC3D-O)") (class "Default")
      (node (ref "IC3") (pin "8") (pinfunction "O_8") (pintype "output"))
      (node (ref "LED16") (pin "K") (pinfunction "C_K") (pintype "passive"))
    )
    (net (code "122") (name "Net-(IC3E-I)") (class "Default")
      (node (ref "IC3") (pin "11") (pinfunction "I_11") (pintype "input"))
      (node (ref "J187") (pin "P$1") (pinfunction "P$1_P$1") (pintype "bidirectional"))
      (node (ref "J187") (pin "P$2") (pinfunction "P$2_P$2") (pintype "bidirectional"))
    )
    (net (code "123") (name "Net-(IC3E-O)") (class "Default")
      (node (ref "IC3") (pin "10") (pinfunction "O_10") (pintype "output"))
      (node (ref "LED17") (pin "K") (pinfunction "C_K") (pintype "passive"))
    )
    (net (code "124") (name "Net-(IC3F-I)") (class "Default")
      (node (ref "IC3") (pin "13") (pinfunction "I_13") (pintype "input"))
      (node (ref "J188") (pin "P$1") (pinfunction "P$1_P$1") (pintype "bidirectional"))
      (node (ref "J188") (pin "P$2") (pinfunction "P$2_P$2") (pintype "bidirectional"))
    )
    (net (code "125") (name "Net-(IC3F-O)") (class "Default")
      (node (ref "IC3") (pin "12") (pinfunction "O_12") (pintype "output"))
      (node (ref "LED18") (pin "K") (pinfunction "C_K") (pintype "passive"))
    )
    (net (code "126") (name "Net-(IC4A-I)") (class "Default")
      (node (ref "IC4") (pin "1") (pinfunction "I_1") (pintype "input"))
      (node (ref "J195") (pin "P$1") (pinfunction "P$1_P$1") (pintype "bidirectional"))
      (node (ref "J195") (pin "P$2") (pinfunction "P$2_P$2") (pintype "bidirectional"))
    )
    (net (code "127") (name "Net-(IC4A-O)") (class "Default")
      (node (ref "IC4") (pin "2") (pinfunction "O_2") (pintype "output"))
      (node (ref "LED19") (pin "K") (pinfunction "C_K") (pintype "passive"))
    )
    (net (code "128") (name "Net-(IC4B-I)") (class "Default")
      (node (ref "IC4") (pin "3") (pinfunction "I_3") (pintype "input"))
      (node (ref "J190") (pin "P$1") (pinfunction "P$1_P$1") (pintype "bidirectional"))
      (node (ref "J190") (pin "P$2") (pinfunction "P$2_P$2") (pintype "bidirectional"))
    )
    (net (code "129") (name "Net-(IC4B-O)") (class "Default")
      (node (ref "IC4") (pin "4") (pinfunction "O_4") (pintype "output"))
      (node (ref "LED20") (pin "K") (pinfunction "C_K") (pintype "passive"))
    )
    (net (code "130") (name "Net-(IC4C-I)") (class "Default")
      (node (ref "IC4") (pin "5") (pinfunction "I_5") (pintype "input"))
      (node (ref "J191") (pin "P$1") (pinfunction "P$1_P$1") (pintype "bidirectional"))
      (node (ref "J191") (pin "P$2") (pinfunction "P$2_P$2") (pintype "bidirectional"))
    )
    (net (code "131") (name "Net-(IC4C-O)") (class "Default")
      (node (ref "IC4") (pin "6") (pinfunction "O_6") (pintype "output"))
      (node (ref "LED21") (pin "K") (pinfunction "C_K") (pintype "passive"))
    )
    (net (code "132") (name "Net-(IC4D-I)") (class "Default")
      (node (ref "IC4") (pin "9") (pinfunction "I_9") (pintype "input"))
      (node (ref "J192") (pin "P$1") (pinfunction "P$1_P$1") (pintype "bidirectional"))
      (node (ref "J192") (pin "P$2") (pinfunction "P$2_P$2") (pintype "bidirectional"))
    )
    (net (code "133") (name "Net-(IC4D-O)") (class "Default")
      (node (ref "IC4") (pin "8") (pinfunction "O_8") (pintype "output"))
      (node (ref "LED22") (pin "K") (pinfunction "C_K") (pintype "passive"))
    )
    (net (code "134") (name "Net-(IC4E-I)") (class "Default")
      (node (ref "IC4") (pin "11") (pinfunction "I_11") (pintype "input"))
      (node (ref "J193") (pin "P$1") (pinfunction "P$1_P$1") (pintype "bidirectional"))
      (node (ref "J193") (pin "P$2") (pinfunction "P$2_P$2") (pintype "bidirectional"))
    )
    (net (code "135") (name "Net-(IC4E-O)") (class "Default")
      (node (ref "IC4") (pin "10") (pinfunction "O_10") (pintype "output"))
      (node (ref "LED23") (pin "K") (pinfunction "C_K") (pintype "passive"))
    )
    (net (code "136") (name "Net-(IC4F-I)") (class "Default")
      (node (ref "IC4") (pin "13") (pinfunction "I_13") (pintype "input"))
      (node (ref "J194") (pin "P$1") (pinfunction "P$1_P$1") (pintype "bidirectional"))
      (node (ref "J194") (pin "P$2") (pinfunction "P$2_P$2") (pintype "bidirectional"))
    )
    (net (code "137") (name "Net-(IC4F-O)") (class "Default")
      (node (ref "IC4") (pin "12") (pinfunction "O_12") (pintype "output"))
      (node (ref "R40") (pin "1") (pinfunction "1_1") (pintype "passive"))
    )
    (net (code "138") (name "Net-(J6-PadP$1)") (class "Default")
      (node (ref "J6") (pin "P$1") (pinfunction "P$1_P$1") (pintype "bidirectional"))
      (node (ref "J6") (pin "P$2") (pinfunction "P$2_P$2") (pintype "bidirectional"))
      (node (ref "J6") (pin "P$3") (pinfunction "P$3_P$3") (pintype "bidirectional"))
      (node (ref "R1") (pin "1") (pinfunction "1_1") (pintype "passive"))
    )
    (net (code "139") (name "Net-(J24-PadP$1)") (class "Default")
      (node (ref "J24") (pin "P$1") (pinfunction "P$1_P$1") (pintype "bidirectional"))
      (node (ref "J24") (pin "P$2") (pinfunction "P$2_P$2") (pintype "bidirectional"))
      (node (ref "J24") (pin "P$3") (pinfunction "P$3_P$3") (pintype "bidirectional"))
      (node (ref "R2") (pin "1") (pinfunction "1_1") (pintype "passive"))
    )
    (net (code "140") (name "Net-(J63-PadP$1)") (class "Default")
      (node (ref "J63") (pin "P$1") (pinfunction "P$1_P$1") (pintype "bidirectional"))
      (node (ref "J63") (pin "P$2") (pinfunction "P$2_P$2") (pintype "bidirectional"))
    )
    (net (code "141") (name "Net-(J70-PadP$1)") (class "Default")
      (node (ref "J70") (pin "P$1") (pinfunction "P$1_P$1") (pintype "bidirectional"))
      (node (ref "J70") (pin "P$2") (pinfunction "P$2_P$2") (pintype "bidirectional"))
    )
    (net (code "142") (name "Net-(J71-PadP$1)") (class "Default")
      (node (ref "J71") (pin "P$1") (pinfunction "P$1_P$1") (pintype "bidirectional"))
      (node (ref "J71") (pin "P$2") (pinfunction "P$2_P$2") (pintype "bidirectional"))
    )
    (net (code "143") (name "Net-(J72-PadP$1)") (class "Default")
      (node (ref "J72") (pin "P$1") (pinfunction "P$1_P$1") (pintype "bidirectional"))
      (node (ref "J72") (pin "P$2") (pinfunction "P$2_P$2") (pintype "bidirectional"))
    )
    (net (code "144") (name "Net-(J73-PadP$1)") (class "Default")
      (node (ref "J73") (pin "P$1") (pinfunction "P$1_P$1") (pintype "bidirectional"))
      (node (ref "J73") (pin "P$2") (pinfunction "P$2_P$2") (pintype "bidirectional"))
    )
    (net (code "145") (name "Net-(J74-PadP$1)") (class "Default")
      (node (ref "J74") (pin "P$1") (pinfunction "P$1_P$1") (pintype "bidirectional"))
      (node (ref "J74") (pin "P$2") (pinfunction "P$2_P$2") (pintype "bidirectional"))
    )
    (net (code "146") (name "Net-(J75-PadP$1)") (class "Default")
      (node (ref "J75") (pin "P$1") (pinfunction "P$1_P$1") (pintype "bidirectional"))
      (node (ref "J75") (pin "P$2") (pinfunction "P$2_P$2") (pintype "bidirectional"))
    )
    (net (code "147") (name "Net-(J76-PadP$1)") (class "Default")
      (node (ref "J76") (pin "P$1") (pinfunction "P$1_P$1") (pintype "bidirectional"))
      (node (ref "J76") (pin "P$2") (pinfunction "P$2_P$2") (pintype "bidirectional"))
    )
    (net (code "148") (name "Net-(J77-PadP$1)") (class "Default")
      (node (ref "J77") (pin "P$1") (pinfunction "P$1_P$1") (pintype "bidirectional"))
      (node (ref "J77") (pin "P$2") (pinfunction "P$2_P$2") (pintype "bidirectional"))
    )
    (net (code "149") (name "Net-(J88-PadP$1)") (class "Default")
      (node (ref "J88") (pin "P$1") (pinfunction "P$1_P$1") (pintype "bidirectional"))
      (node (ref "J91") (pin "P$1") (pinfunction "P$1_P$1") (pintype "bidirectional"))
      (node (ref "J91") (pin "P$2") (pinfunction "P$2_P$2") (pintype "bidirectional"))
    )
    (net (code "150") (name "Net-(J88-PadP$3)") (class "Default")
      (node (ref "J88") (pin "P$3") (pinfunction "P$3_P$3") (pintype "bidirectional"))
      (node (ref "J92") (pin "P$1") (pinfunction "P$1_P$1") (pintype "bidirectional"))
      (node (ref "J92") (pin "P$2") (pinfunction "P$2_P$2") (pintype "bidirectional"))
    )
    (net (code "151") (name "Net-(J88-PadP$4)") (class "Default")
      (node (ref "J88") (pin "P$4") (pinfunction "P$4_P$4") (pintype "bidirectional"))
      (node (ref "J93") (pin "P$1") (pinfunction "P$1_P$1") (pintype "bidirectional"))
      (node (ref "J93") (pin "P$2") (pinfunction "P$2_P$2") (pintype "bidirectional"))
    )
    (net (code "152") (name "Net-(J88-R+)") (class "Default")
      (node (ref "J88") (pin "P$2") (pinfunction "R+_P$2") (pintype "bidirectional"))
      (node (ref "J89") (pin "P$1") (pinfunction "P$1_P$1") (pintype "bidirectional"))
      (node (ref "J89") (pin "P$2") (pinfunction "P$2_P$2") (pintype "bidirectional"))
    )
    (net (code "153") (name "Net-(J88-R-)") (class "Default")
      (node (ref "J88") (pin "P$5") (pinfunction "R-_P$5") (pintype "bidirectional"))
      (node (ref "J90") (pin "P$1") (pinfunction "P$1_P$1") (pintype "bidirectional"))
      (node (ref "J90") (pin "P$2") (pinfunction "P$2_P$2") (pintype "bidirectional"))
    )
    (net (code "154") (name "Net-(LED1-PadA)") (class "Default")
      (node (ref "LED1") (pin "A") (pinfunction "A_A") (pintype "passive"))
      (node (ref "R11") (pin "1") (pinfunction "1_1") (pintype "passive"))
    )
    (net (code "155") (name "Net-(LED2-PadA)") (class "Default")
      (node (ref "LED2") (pin "A") (pinfunction "A_A") (pintype "passive"))
      (node (ref "R12") (pin "1") (pinfunction "1_1") (pintype "passive"))
    )
    (net (code "156") (name "Net-(LED3-PadA)") (class "Default")
      (node (ref "LED3") (pin "A") (pinfunction "A_A") (pintype "passive"))
      (node (ref "R13") (pin "1") (pinfunction "1_1") (pintype "passive"))
    )
    (net (code "157") (name "Net-(LED4-PadA)") (class "Default")
      (node (ref "LED4") (pin "A") (pinfunction "A_A") (pintype "passive"))
      (node (ref "R14") (pin "1") (pinfunction "1_1") (pintype "passive"))
    )
    (net (code "158") (name "Net-(LED5-PadA)") (class "Default")
      (node (ref "LED5") (pin "A") (pinfunction "A_A") (pintype "passive"))
      (node (ref "R15") (pin "1") (pinfunction "1_1") (pintype "passive"))
    )
    (net (code "159") (name "Net-(LED6-PadA)") (class "Default")
      (node (ref "LED6") (pin "A") (pinfunction "A_A") (pintype "passive"))
      (node (ref "R16") (pin "1") (pinfunction "1_1") (pintype "passive"))
    )
    (net (code "160") (name "Net-(LED7-PadA)") (class "Default")
      (node (ref "LED7") (pin "A") (pinfunction "A_A") (pintype "passive"))
      (node (ref "R17") (pin "1") (pinfunction "1_1") (pintype "passive"))
    )
    (net (code "161") (name "Net-(LED8-PadA)") (class "Default")
      (node (ref "LED8") (pin "A") (pinfunction "A_A") (pintype "passive"))
      (node (ref "R19") (pin "1") (pinfunction "1_1") (pintype "passive"))
    )
    (net (code "162") (name "Net-(LED9-PadA)") (class "Default")
      (node (ref "LED9") (pin "A") (pinfunction "A_A") (pintype "passive"))
      (node (ref "R20") (pin "1") (pinfunction "1_1") (pintype "passive"))
    )
    (net (code "163") (name "Net-(LED10-PadA)") (class "Default")
      (node (ref "LED10") (pin "A") (pinfunction "A_A") (pintype "passive"))
      (node (ref "R21") (pin "1") (pinfunction "1_1") (pintype "passive"))
    )
    (net (code "164") (name "Net-(LED11-PadA)") (class "Default")
      (node (ref "LED11") (pin "A") (pinfunction "A_A") (pintype "passive"))
      (node (ref "R22") (pin "1") (pinfunction "1_1") (pintype "passive"))
    )
    (net (code "165") (name "Net-(LED12-PadA)") (class "Default")
      (node (ref "LED12") (pin "A") (pinfunction "A_A") (pintype "passive"))
      (node (ref "R23") (pin "1") (pinfunction "1_1") (pintype "passive"))
    )
    (net (code "166") (name "Net-(LED13-PadA)") (class "Default")
      (node (ref "LED13") (pin "A") (pinfunction "A_A") (pintype "passive"))
      (node (ref "R28") (pin "1") (pinfunction "1_1") (pintype "passive"))
    )
    (net (code "167") (name "Net-(LED14-PadA)") (class "Default")
      (node (ref "LED14") (pin "A") (pinfunction "A_A") (pintype "passive"))
      (node (ref "R29") (pin "1") (pinfunction "1_1") (pintype "passive"))
    )
    (net (code "168") (name "Net-(LED15-PadA)") (class "Default")
      (node (ref "LED15") (pin "A") (pinfunction "A_A") (pintype "passive"))
      (node (ref "R30") (pin "1") (pinfunction "1_1") (pintype "passive"))
    )
    (net (code "169") (name "Net-(LED16-PadA)") (class "Default")
      (node (ref "LED16") (pin "A") (pinfunction "A_A") (pintype "passive"))
      (node (ref "R31") (pin "1") (pinfunction "1_1") (pintype "passive"))
    )
    (net (code "170") (name "Net-(LED17-PadA)") (class "Default")
      (node (ref "LED17") (pin "A") (pinfunction "A_A") (pintype "passive"))
      (node (ref "R32") (pin "1") (pinfunction "1_1") (pintype "passive"))
    )
    (net (code "171") (name "Net-(LED18-PadA)") (class "Default")
      (node (ref "LED18") (pin "A") (pinfunction "A_A") (pintype "passive"))
      (node (ref "R33") (pin "1") (pinfunction "1_1") (pintype "passive"))
    )
    (net (code "172") (name "Net-(LED19-PadA)") (class "Default")
      (node (ref "LED19") (pin "A") (pinfunction "A_A") (pintype "passive"))
      (node (ref "R34") (pin "1") (pinfunction "1_1") (pintype "passive"))
    )
    (net (code "173") (name "Net-(LED20-PadA)") (class "Default")
      (node (ref "LED20") (pin "A") (pinfunction "A_A") (pintype "passive"))
      (node (ref "R35") (pin "1") (pinfunction "1_1") (pintype "passive"))
    )
    (net (code "174") (name "Net-(LED21-PadA)") (class "Default")
      (node (ref "LED21") (pin "A") (pinfunction "A_A") (pintype "passive"))
      (node (ref "R36") (pin "1") (pinfunction "1_1") (pintype "passive"))
    )
    (net (code "175") (name "Net-(LED22-PadA)") (class "Default")
      (node (ref "LED22") (pin "A") (pinfunction "A_A") (pintype "passive"))
      (node (ref "R37") (pin "1") (pinfunction "1_1") (pintype "passive"))
    )
    (net (code "176") (name "Net-(LED23-PadA)") (class "Default")
      (node (ref "LED23") (pin "A") (pinfunction "A_A") (pintype "passive"))
      (node (ref "R38") (pin "1") (pinfunction "1_1") (pintype "passive"))
    )
    (net (code "177") (name "Net-(LED24-C)") (class "Default")
      (node (ref "J62") (pin "P$1") (pinfunction "P$1_P$1") (pintype "bidirectional"))
      (node (ref "J62") (pin "P$2") (pinfunction "P$2_P$2") (pintype "bidirectional"))
      (node (ref "LED24") (pin "K") (pinfunction "C_K") (pintype "passive"))
    )
    (net (code "178") (name "Net-(LED24-PadA)") (class "Default")
      (node (ref "LED24") (pin "A") (pinfunction "A_A") (pintype "passive"))
      (node (ref "R39") (pin "1") (pinfunction "1_1") (pintype "passive"))
    )
    (net (code "179") (name "Net-(LED_3.3V1-PadA)") (class "Default")
      (node (ref "LED_3.3V1") (pin "A") (pinfunction "A_A") (pintype "passive"))
      (node (ref "R27") (pin "1") (pinfunction "1_1") (pintype "passive"))
    )
    (net (code "180") (name "Net-(LED_5V1-PadA)") (class "Default")
      (node (ref "LED_5V1") (pin "A") (pinfunction "A_A") (pintype "passive"))
      (node (ref "R26") (pin "1") (pinfunction "1_1") (pintype "passive"))
    )
    (net (code "181") (name "Net-(M1-OUT)") (class "Default")
      (node (ref "C18") (pin "1") (pinfunction "1_1") (pintype "passive"))
      (node (ref "M1") (pin "P$1") (pinfunction "OUT_P$1") (pintype "bidirectional"))
      (node (ref "R9") (pin "2") (pinfunction "2_2") (pintype "passive"))
    )
    (net (code "182") (name "Net-(S91-PadP$1)") (class "Default")
      (node (ref "S91") (pin "P$1") (pinfunction "P$1_P$1") (pintype "bidirectional"))
      (node (ref "S91") (pin "P$2") (pinfunction "P$2_P$2") (pintype "bidirectional"))
      (node (ref "S91") (pin "P$3") (pinfunction "P$3_P$3") (pintype "bidirectional"))
      (node (ref "S91") (pin "P$4") (pinfunction "P$4_P$4") (pintype "bidirectional"))
      (node (ref "S91") (pin "P$5") (pinfunction "P$5_P$5") (pintype "bidirectional"))
    )
    (net (code "183") (name "Net-(S92-PadP$1)") (class "Default")
      (node (ref "S92") (pin "P$1") (pinfunction "P$1_P$1") (pintype "bidirectional"))
      (node (ref "S92") (pin "P$2") (pinfunction "P$2_P$2") (pintype "bidirectional"))
      (node (ref "S92") (pin "P$3") (pinfunction "P$3_P$3") (pintype "bidirectional"))
      (node (ref "S92") (pin "P$4") (pinfunction "P$4_P$4") (pintype "bidirectional"))
      (node (ref "S92") (pin "P$5") (pinfunction "P$5_P$5") (pintype "bidirectional"))
    )
    (net (code "184") (name "Net-(S93-PadP$1)") (class "Default")
      (node (ref "S93") (pin "P$1") (pinfunction "P$1_P$1") (pintype "bidirectional"))
      (node (ref "S93") (pin "P$2") (pinfunction "P$2_P$2") (pintype "bidirectional"))
      (node (ref "S93") (pin "P$3") (pinfunction "P$3_P$3") (pintype "bidirectional"))
      (node (ref "S93") (pin "P$4") (pinfunction "P$4_P$4") (pintype "bidirectional"))
      (node (ref "S93") (pin "P$5") (pinfunction "P$5_P$5") (pintype "bidirectional"))
    )
    (net (code "185") (name "Net-(S94-PadP$1)") (class "Default")
      (node (ref "S94") (pin "P$1") (pinfunction "P$1_P$1") (pintype "bidirectional"))
      (node (ref "S94") (pin "P$2") (pinfunction "P$2_P$2") (pintype "bidirectional"))
      (node (ref "S94") (pin "P$3") (pinfunction "P$3_P$3") (pintype "bidirectional"))
      (node (ref "S94") (pin "P$4") (pinfunction "P$4_P$4") (pintype "bidirectional"))
      (node (ref "S94") (pin "P$5") (pinfunction "P$5_P$5") (pintype "bidirectional"))
    )
    (net (code "186") (name "Net-(S95-PadP$1)") (class "Default")
      (node (ref "S95") (pin "P$1") (pinfunction "P$1_P$1") (pintype "bidirectional"))
      (node (ref "S95") (pin "P$2") (pinfunction "P$2_P$2") (pintype "bidirectional"))
      (node (ref "S95") (pin "P$3") (pinfunction "P$3_P$3") (pintype "bidirectional"))
      (node (ref "S95") (pin "P$4") (pinfunction "P$4_P$4") (pintype "bidirectional"))
      (node (ref "S95") (pin "P$5") (pinfunction "P$5_P$5") (pintype "bidirectional"))
    )
    (net (code "187") (name "Net-(S96-PadP$1)") (class "Default")
      (node (ref "S96") (pin "P$1") (pinfunction "P$1_P$1") (pintype "bidirectional"))
      (node (ref "S96") (pin "P$2") (pinfunction "P$2_P$2") (pintype "bidirectional"))
      (node (ref "S96") (pin "P$3") (pinfunction "P$3_P$3") (pintype "bidirectional"))
      (node (ref "S96") (pin "P$4") (pinfunction "P$4_P$4") (pintype "bidirectional"))
      (node (ref "S96") (pin "P$5") (pinfunction "P$5_P$5") (pintype "bidirectional"))
    )
    (net (code "188") (name "Net-(S97-PadP$1)") (class "Default")
      (node (ref "S97") (pin "P$1") (pinfunction "P$1_P$1") (pintype "bidirectional"))
      (node (ref "S97") (pin "P$2") (pinfunction "P$2_P$2") (pintype "bidirectional"))
      (node (ref "S97") (pin "P$3") (pinfunction "P$3_P$3") (pintype "bidirectional"))
      (node (ref "S97") (pin "P$4") (pinfunction "P$4_P$4") (pintype "bidirectional"))
      (node (ref "S97") (pin "P$5") (pinfunction "P$5_P$5") (pintype "bidirectional"))
    )
    (net (code "189") (name "Net-(S98-PadP$1)") (class "Default")
      (node (ref "S98") (pin "P$1") (pinfunction "P$1_P$1") (pintype "bidirectional"))
      (node (ref "S98") (pin "P$2") (pinfunction "P$2_P$2") (pintype "bidirectional"))
      (node (ref "S98") (pin "P$3") (pinfunction "P$3_P$3") (pintype "bidirectional"))
      (node (ref "S98") (pin "P$4") (pinfunction "P$4_P$4") (pintype "bidirectional"))
      (node (ref "S98") (pin "P$5") (pinfunction "P$5_P$5") (pintype "bidirectional"))
    )
    (net (code "190") (name "Net-(S99-PadP$1)") (class "Default")
      (node (ref "S99") (pin "P$1") (pinfunction "P$1_P$1") (pintype "bidirectional"))
      (node (ref "S99") (pin "P$2") (pinfunction "P$2_P$2") (pintype "bidirectional"))
      (node (ref "S99") (pin "P$3") (pinfunction "P$3_P$3") (pintype "bidirectional"))
      (node (ref "S99") (pin "P$4") (pinfunction "P$4_P$4") (pintype "bidirectional"))
      (node (ref "S99") (pin "P$5") (pinfunction "P$5_P$5") (pintype "bidirectional"))
    )
    (net (code "191") (name "Net-(S101-PadP$1)") (class "Default")
      (node (ref "S101") (pin "P$1") (pinfunction "P$1_P$1") (pintype "bidirectional"))
      (node (ref "S101") (pin "P$2") (pinfunction "P$2_P$2") (pintype "bidirectional"))
      (node (ref "S101") (pin "P$3") (pinfunction "P$3_P$3") (pintype "bidirectional"))
      (node (ref "S101") (pin "P$4") (pinfunction "P$4_P$4") (pintype "bidirectional"))
      (node (ref "S101") (pin "P$5") (pinfunction "P$5_P$5") (pintype "bidirectional"))
    )
    (net (code "192") (name "Net-(S105-PadP$1)") (class "Default")
      (node (ref "S105") (pin "P$1") (pinfunction "P$1_P$1") (pintype "bidirectional"))
      (node (ref "S105") (pin "P$2") (pinfunction "P$2_P$2") (pintype "bidirectional"))
      (node (ref "S105") (pin "P$3") (pinfunction "P$3_P$3") (pintype "bidirectional"))
      (node (ref "S105") (pin "P$4") (pinfunction "P$4_P$4") (pintype "bidirectional"))
      (node (ref "S105") (pin "P$5") (pinfunction "P$5_P$5") (pintype "bidirectional"))
    )
    (net (code "193") (name "Net-(S108-PadP$1)") (class "Default")
      (node (ref "S108") (pin "P$1") (pinfunction "P$1_P$1") (pintype "bidirectional"))
      (node (ref "S108") (pin "P$2") (pinfunction "P$2_P$2") (pintype "bidirectional"))
      (node (ref "S108") (pin "P$3") (pinfunction "P$3_P$3") (pintype "bidirectional"))
      (node (ref "S108") (pin "P$4") (pinfunction "P$4_P$4") (pintype "bidirectional"))
      (node (ref "S108") (pin "P$5") (pinfunction "P$5_P$5") (pintype "bidirectional"))
    )
    (net (code "194") (name "Net-(S130-PadP$1)") (class "Default")
      (node (ref "S130") (pin "P$1") (pinfunction "P$1_P$1") (pintype "bidirectional"))
      (node (ref "S130") (pin "P$2") (pinfunction "P$2_P$2") (pintype "bidirectional"))
      (node (ref "S130") (pin "P$3") (pinfunction "P$3_P$3") (pintype "bidirectional"))
      (node (ref "S130") (pin "P$4") (pinfunction "P$4_P$4") (pintype "bidirectional"))
      (node (ref "S130") (pin "P$5") (pinfunction "P$5_P$5") (pintype "bidirectional"))
    )
    (net (code "195") (name "Net-(S138-PadP$1)") (class "Default")
      (node (ref "S138") (pin "P$1") (pinfunction "P$1_P$1") (pintype "bidirectional"))
      (node (ref "S138") (pin "P$2") (pinfunction "P$2_P$2") (pintype "bidirectional"))
      (node (ref "S138") (pin "P$3") (pinfunction "P$3_P$3") (pintype "bidirectional"))
      (node (ref "S138") (pin "P$4") (pinfunction "P$4_P$4") (pintype "bidirectional"))
      (node (ref "S138") (pin "P$5") (pinfunction "P$5_P$5") (pintype "bidirectional"))
    )
    (net (code "196") (name "Net-(S140-PadP$1)") (class "Default")
      (node (ref "S140") (pin "P$1") (pinfunction "P$1_P$1") (pintype "bidirectional"))
      (node (ref "S140") (pin "P$2") (pinfunction "P$2_P$2") (pintype "bidirectional"))
      (node (ref "S140") (pin "P$3") (pinfunction "P$3_P$3") (pintype "bidirectional"))
      (node (ref "S140") (pin "P$4") (pinfunction "P$4_P$4") (pintype "bidirectional"))
      (node (ref "S140") (pin "P$5") (pinfunction "P$5_P$5") (pintype "bidirectional"))
    )
    (net (code "197") (name "Net-(S159-P3)") (class "Default")
      (node (ref "R18") (pin "1") (pinfunction "1_1") (pintype "passive"))
      (node (ref "S159") (pin "P$3") (pinfunction "P3_P$3") (pintype "bidirectional"))
    )
    (net (code "198") (name "Net-(S160-PadP$1)") (class "Default")
      (node (ref "S160") (pin "P$1") (pinfunction "P$1_P$1") (pintype "bidirectional"))
      (node (ref "S160") (pin "P$2") (pinfunction "P$2_P$2") (pintype "bidirectional"))
      (node (ref "S160") (pin "P$3") (pinfunction "P$3_P$3") (pintype "bidirectional"))
      (node (ref "S160") (pin "P$4") (pinfunction "P$4_P$4") (pintype "bidirectional"))
      (node (ref "S160") (pin "P$5") (pinfunction "P$5_P$5") (pintype "bidirectional"))
    )
    (net (code "199") (name "Net-(S161-PadP$1)") (class "Default")
      (node (ref "S161") (pin "P$1") (pinfunction "P$1_P$1") (pintype "bidirectional"))
      (node (ref "S161") (pin "P$2") (pinfunction "P$2_P$2") (pintype "bidirectional"))
      (node (ref "S161") (pin "P$3") (pinfunction "P$3_P$3") (pintype "bidirectional"))
      (node (ref "S161") (pin "P$4") (pinfunction "P$4_P$4") (pintype "bidirectional"))
      (node (ref "S161") (pin "P$5") (pinfunction "P$5_P$5") (pintype "bidirectional"))
    )
    (net (code "200") (name "Net-(S162-PadP$1)") (class "Default")
      (node (ref "S162") (pin "P$1") (pinfunction "P$1_P$1") (pintype "bidirectional"))
      (node (ref "S162") (pin "P$2") (pinfunction "P$2_P$2") (pintype "bidirectional"))
      (node (ref "S162") (pin "P$3") (pinfunction "P$3_P$3") (pintype "bidirectional"))
      (node (ref "S162") (pin "P$4") (pinfunction "P$4_P$4") (pintype "bidirectional"))
      (node (ref "S162") (pin "P$5") (pinfunction "P$5_P$5") (pintype "bidirectional"))
    )
    (net (code "201") (name "Net-(S163-PadP$1)") (class "Default")
      (node (ref "S163") (pin "P$1") (pinfunction "P$1_P$1") (pintype "bidirectional"))
      (node (ref "S163") (pin "P$2") (pinfunction "P$2_P$2") (pintype "bidirectional"))
      (node (ref "S163") (pin "P$3") (pinfunction "P$3_P$3") (pintype "bidirectional"))
      (node (ref "S163") (pin "P$4") (pinfunction "P$4_P$4") (pintype "bidirectional"))
      (node (ref "S163") (pin "P$5") (pinfunction "P$5_P$5") (pintype "bidirectional"))
    )
    (net (code "202") (name "Net-(S164-PadP$1)") (class "Default")
      (node (ref "S164") (pin "P$1") (pinfunction "P$1_P$1") (pintype "bidirectional"))
      (node (ref "S164") (pin "P$2") (pinfunction "P$2_P$2") (pintype "bidirectional"))
      (node (ref "S164") (pin "P$3") (pinfunction "P$3_P$3") (pintype "bidirectional"))
      (node (ref "S164") (pin "P$4") (pinfunction "P$4_P$4") (pintype "bidirectional"))
      (node (ref "S164") (pin "P$5") (pinfunction "P$5_P$5") (pintype "bidirectional"))
    )
    (net (code "203") (name "Net-(S165-PadP$1)") (class "Default")
      (node (ref "S165") (pin "P$1") (pinfunction "P$1_P$1") (pintype "bidirectional"))
      (node (ref "S165") (pin "P$2") (pinfunction "P$2_P$2") (pintype "bidirectional"))
      (node (ref "S165") (pin "P$3") (pinfunction "P$3_P$3") (pintype "bidirectional"))
      (node (ref "S165") (pin "P$4") (pinfunction "P$4_P$4") (pintype "bidirectional"))
      (node (ref "S165") (pin "P$5") (pinfunction "P$5_P$5") (pintype "bidirectional"))
    )
    (net (code "204") (name "Net-(S166-PadP$1)") (class "Default")
      (node (ref "S166") (pin "P$1") (pinfunction "P$1_P$1") (pintype "bidirectional"))
      (node (ref "S166") (pin "P$2") (pinfunction "P$2_P$2") (pintype "bidirectional"))
      (node (ref "S166") (pin "P$3") (pinfunction "P$3_P$3") (pintype "bidirectional"))
      (node (ref "S166") (pin "P$4") (pinfunction "P$4_P$4") (pintype "bidirectional"))
      (node (ref "S166") (pin "P$5") (pinfunction "P$5_P$5") (pintype "bidirectional"))
    )
    (net (code "205") (name "Net-(S167-PadP$1)") (class "Default")
      (node (ref "S167") (pin "P$1") (pinfunction "P$1_P$1") (pintype "bidirectional"))
      (node (ref "S167") (pin "P$2") (pinfunction "P$2_P$2") (pintype "bidirectional"))
      (node (ref "S167") (pin "P$3") (pinfunction "P$3_P$3") (pintype "bidirectional"))
      (node (ref "S167") (pin "P$4") (pinfunction "P$4_P$4") (pintype "bidirectional"))
      (node (ref "S167") (pin "P$5") (pinfunction "P$5_P$5") (pintype "bidirectional"))
    )
    (net (code "206") (name "Net-(S168-PadP$1)") (class "Default")
      (node (ref "S168") (pin "P$1") (pinfunction "P$1_P$1") (pintype "bidirectional"))
      (node (ref "S168") (pin "P$2") (pinfunction "P$2_P$2") (pintype "bidirectional"))
      (node (ref "S168") (pin "P$3") (pinfunction "P$3_P$3") (pintype "bidirectional"))
      (node (ref "S168") (pin "P$4") (pinfunction "P$4_P$4") (pintype "bidirectional"))
      (node (ref "S168") (pin "P$5") (pinfunction "P$5_P$5") (pintype "bidirectional"))
    )
    (net (code "207") (name "Net-(S169-PadP$1)") (class "Default")
      (node (ref "S169") (pin "P$1") (pinfunction "P$1_P$1") (pintype "bidirectional"))
      (node (ref "S169") (pin "P$2") (pinfunction "P$2_P$2") (pintype "bidirectional"))
      (node (ref "S169") (pin "P$3") (pinfunction "P$3_P$3") (pintype "bidirectional"))
      (node (ref "S169") (pin "P$4") (pinfunction "P$4_P$4") (pintype "bidirectional"))
      (node (ref "S169") (pin "P$5") (pinfunction "P$5_P$5") (pintype "bidirectional"))
    )
    (net (code "208") (name "Net-(S170-PadP$1)") (class "Default")
      (node (ref "S170") (pin "P$1") (pinfunction "P$1_P$1") (pintype "bidirectional"))
      (node (ref "S170") (pin "P$2") (pinfunction "P$2_P$2") (pintype "bidirectional"))
      (node (ref "S170") (pin "P$3") (pinfunction "P$3_P$3") (pintype "bidirectional"))
      (node (ref "S170") (pin "P$4") (pinfunction "P$4_P$4") (pintype "bidirectional"))
      (node (ref "S170") (pin "P$5") (pinfunction "P$5_P$5") (pintype "bidirectional"))
    )
    (net (code "209") (name "Net-(S171-PadP$1)") (class "Default")
      (node (ref "S171") (pin "P$1") (pinfunction "P$1_P$1") (pintype "bidirectional"))
      (node (ref "S171") (pin "P$2") (pinfunction "P$2_P$2") (pintype "bidirectional"))
      (node (ref "S171") (pin "P$3") (pinfunction "P$3_P$3") (pintype "bidirectional"))
      (node (ref "S171") (pin "P$4") (pinfunction "P$4_P$4") (pintype "bidirectional"))
      (node (ref "S171") (pin "P$5") (pinfunction "P$5_P$5") (pintype "bidirectional"))
    )
    (net (code "210") (name "Net-(S172-PadP$1)") (class "Default")
      (node (ref "S172") (pin "P$1") (pinfunction "P$1_P$1") (pintype "bidirectional"))
      (node (ref "S172") (pin "P$2") (pinfunction "P$2_P$2") (pintype "bidirectional"))
      (node (ref "S172") (pin "P$3") (pinfunction "P$3_P$3") (pintype "bidirectional"))
      (node (ref "S172") (pin "P$4") (pinfunction "P$4_P$4") (pintype "bidirectional"))
      (node (ref "S172") (pin "P$5") (pinfunction "P$5_P$5") (pintype "bidirectional"))
    )
    (net (code "211") (name "Net-(S173-PadP$1)") (class "Default")
      (node (ref "S173") (pin "P$1") (pinfunction "P$1_P$1") (pintype "bidirectional"))
      (node (ref "S173") (pin "P$2") (pinfunction "P$2_P$2") (pintype "bidirectional"))
      (node (ref "S173") (pin "P$3") (pinfunction "P$3_P$3") (pintype "bidirectional"))
      (node (ref "S173") (pin "P$4") (pinfunction "P$4_P$4") (pintype "bidirectional"))
      (node (ref "S173") (pin "P$5") (pinfunction "P$5_P$5") (pintype "bidirectional"))
    )
    (net (code "212") (name "Net-(S174-PadP$1)") (class "Default")
      (node (ref "S174") (pin "P$1") (pinfunction "P$1_P$1") (pintype "bidirectional"))
      (node (ref "S174") (pin "P$2") (pinfunction "P$2_P$2") (pintype "bidirectional"))
      (node (ref "S174") (pin "P$3") (pinfunction "P$3_P$3") (pintype "bidirectional"))
      (node (ref "S174") (pin "P$4") (pinfunction "P$4_P$4") (pintype "bidirectional"))
      (node (ref "S174") (pin "P$5") (pinfunction "P$5_P$5") (pintype "bidirectional"))
    )
    (net (code "213") (name "Net-(S175-PadP$1)") (class "Default")
      (node (ref "S175") (pin "P$1") (pinfunction "P$1_P$1") (pintype "bidirectional"))
      (node (ref "S175") (pin "P$2") (pinfunction "P$2_P$2") (pintype "bidirectional"))
      (node (ref "S175") (pin "P$3") (pinfunction "P$3_P$3") (pintype "bidirectional"))
      (node (ref "S175") (pin "P$4") (pinfunction "P$4_P$4") (pintype "bidirectional"))
      (node (ref "S175") (pin "P$5") (pinfunction "P$5_P$5") (pintype "bidirectional"))
    )
    (net (code "214") (name "Net-(S176-PadP$1)") (class "Default")
      (node (ref "S176") (pin "P$1") (pinfunction "P$1_P$1") (pintype "bidirectional"))
      (node (ref "S176") (pin "P$2") (pinfunction "P$2_P$2") (pintype "bidirectional"))
      (node (ref "S176") (pin "P$3") (pinfunction "P$3_P$3") (pintype "bidirectional"))
      (node (ref "S176") (pin "P$4") (pinfunction "P$4_P$4") (pintype "bidirectional"))
      (node (ref "S176") (pin "P$5") (pinfunction "P$5_P$5") (pintype "bidirectional"))
    )
    (net (code "215") (name "Net-(S177-PadP$1)") (class "Default")
      (node (ref "S177") (pin "P$1") (pinfunction "P$1_P$1") (pintype "bidirectional"))
      (node (ref "S177") (pin "P$2") (pinfunction "P$2_P$2") (pintype "bidirectional"))
      (node (ref "S177") (pin "P$3") (pinfunction "P$3_P$3") (pintype "bidirectional"))
      (node (ref "S177") (pin "P$4") (pinfunction "P$4_P$4") (pintype "bidirectional"))
      (node (ref "S177") (pin "P$5") (pinfunction "P$5_P$5") (pintype "bidirectional"))
    )
    (net (code "216") (name "Net-(S178-PadP$1)") (class "Default")
      (node (ref "S178") (pin "P$1") (pinfunction "P$1_P$1") (pintype "bidirectional"))
      (node (ref "S178") (pin "P$2") (pinfunction "P$2_P$2") (pintype "bidirectional"))
      (node (ref "S178") (pin "P$3") (pinfunction "P$3_P$3") (pintype "bidirectional"))
      (node (ref "S178") (pin "P$4") (pinfunction "P$4_P$4") (pintype "bidirectional"))
      (node (ref "S178") (pin "P$5") (pinfunction "P$5_P$5") (pintype "bidirectional"))
    )
    (net (code "217") (name "Net-(S179-PadP$1)") (class "Default")
      (node (ref "S179") (pin "P$1") (pinfunction "P$1_P$1") (pintype "bidirectional"))
      (node (ref "S179") (pin "P$2") (pinfunction "P$2_P$2") (pintype "bidirectional"))
      (node (ref "S179") (pin "P$3") (pinfunction "P$3_P$3") (pintype "bidirectional"))
      (node (ref "S179") (pin "P$4") (pinfunction "P$4_P$4") (pintype "bidirectional"))
      (node (ref "S179") (pin "P$5") (pinfunction "P$5_P$5") (pintype "bidirectional"))
    )
    (net (code "218") (name "Net-(S180-PadP$1)") (class "Default")
      (node (ref "S180") (pin "P$1") (pinfunction "P$1_P$1") (pintype "bidirectional"))
      (node (ref "S180") (pin "P$2") (pinfunction "P$2_P$2") (pintype "bidirectional"))
      (node (ref "S180") (pin "P$3") (pinfunction "P$3_P$3") (pintype "bidirectional"))
      (node (ref "S180") (pin "P$4") (pinfunction "P$4_P$4") (pintype "bidirectional"))
      (node (ref "S180") (pin "P$5") (pinfunction "P$5_P$5") (pintype "bidirectional"))
    )
    (net (code "219") (name "Net-(S181-PadP$1)") (class "Default")
      (node (ref "S181") (pin "P$1") (pinfunction "P$1_P$1") (pintype "bidirectional"))
      (node (ref "S181") (pin "P$2") (pinfunction "P$2_P$2") (pintype "bidirectional"))
      (node (ref "S181") (pin "P$3") (pinfunction "P$3_P$3") (pintype "bidirectional"))
      (node (ref "S181") (pin "P$4") (pinfunction "P$4_P$4") (pintype "bidirectional"))
      (node (ref "S181") (pin "P$5") (pinfunction "P$5_P$5") (pintype "bidirectional"))
    )
    (net (code "220") (name "Net-(S182-PadP$1)") (class "Default")
      (node (ref "S182") (pin "P$1") (pinfunction "P$1_P$1") (pintype "bidirectional"))
      (node (ref "S182") (pin "P$2") (pinfunction "P$2_P$2") (pintype "bidirectional"))
      (node (ref "S182") (pin "P$3") (pinfunction "P$3_P$3") (pintype "bidirectional"))
      (node (ref "S182") (pin "P$4") (pinfunction "P$4_P$4") (pintype "bidirectional"))
      (node (ref "S182") (pin "P$5") (pinfunction "P$5_P$5") (pintype "bidirectional"))
    )
    (net (code "221") (name "Net-(S183-PadP$1)") (class "Default")
      (node (ref "S183") (pin "P$1") (pinfunction "P$1_P$1") (pintype "bidirectional"))
      (node (ref "S183") (pin "P$2") (pinfunction "P$2_P$2") (pintype "bidirectional"))
      (node (ref "S183") (pin "P$3") (pinfunction "P$3_P$3") (pintype "bidirectional"))
      (node (ref "S183") (pin "P$4") (pinfunction "P$4_P$4") (pintype "bidirectional"))
      (node (ref "S183") (pin "P$5") (pinfunction "P$5_P$5") (pintype "bidirectional"))
    )
    (net (code "222") (name "Net-(S184-PadP$1)") (class "Default")
      (node (ref "S184") (pin "P$1") (pinfunction "P$1_P$1") (pintype "bidirectional"))
      (node (ref "S184") (pin "P$2") (pinfunction "P$2_P$2") (pintype "bidirectional"))
      (node (ref "S184") (pin "P$3") (pinfunction "P$3_P$3") (pintype "bidirectional"))
      (node (ref "S184") (pin "P$4") (pinfunction "P$4_P$4") (pintype "bidirectional"))
      (node (ref "S184") (pin "P$5") (pinfunction "P$5_P$5") (pintype "bidirectional"))
    )
    (net (code "223") (name "Net-(S185-PadP$1)") (class "Default")
      (node (ref "S185") (pin "P$1") (pinfunction "P$1_P$1") (pintype "bidirectional"))
      (node (ref "S185") (pin "P$2") (pinfunction "P$2_P$2") (pintype "bidirectional"))
      (node (ref "S185") (pin "P$3") (pinfunction "P$3_P$3") (pintype "bidirectional"))
      (node (ref "S185") (pin "P$4") (pinfunction "P$4_P$4") (pintype "bidirectional"))
      (node (ref "S185") (pin "P$5") (pinfunction "P$5_P$5") (pintype "bidirectional"))
    )
    (net (code "224") (name "Net-(S186-PadP$1)") (class "Default")
      (node (ref "S186") (pin "P$1") (pinfunction "P$1_P$1") (pintype "bidirectional"))
      (node (ref "S186") (pin "P$2") (pinfunction "P$2_P$2") (pintype "bidirectional"))
      (node (ref "S186") (pin "P$3") (pinfunction "P$3_P$3") (pintype "bidirectional"))
      (node (ref "S186") (pin "P$4") (pinfunction "P$4_P$4") (pintype "bidirectional"))
      (node (ref "S186") (pin "P$5") (pinfunction "P$5_P$5") (pintype "bidirectional"))
    )
    (net (code "225") (name "Net-(S187-PadP$1)") (class "Default")
      (node (ref "S187") (pin "P$1") (pinfunction "P$1_P$1") (pintype "bidirectional"))
      (node (ref "S187") (pin "P$2") (pinfunction "P$2_P$2") (pintype "bidirectional"))
      (node (ref "S187") (pin "P$3") (pinfunction "P$3_P$3") (pintype "bidirectional"))
      (node (ref "S187") (pin "P$4") (pinfunction "P$4_P$4") (pintype "bidirectional"))
      (node (ref "S187") (pin "P$5") (pinfunction "P$5_P$5") (pintype "bidirectional"))
    )
    (net (code "226") (name "Net-(S188-PadP$1)") (class "Default")
      (node (ref "S188") (pin "P$1") (pinfunction "P$1_P$1") (pintype "bidirectional"))
      (node (ref "S188") (pin "P$2") (pinfunction "P$2_P$2") (pintype "bidirectional"))
      (node (ref "S188") (pin "P$3") (pinfunction "P$3_P$3") (pintype "bidirectional"))
      (node (ref "S188") (pin "P$4") (pinfunction "P$4_P$4") (pintype "bidirectional"))
      (node (ref "S188") (pin "P$5") (pinfunction "P$5_P$5") (pintype "bidirectional"))
    )
    (net (code "227") (name "Net-(S189-PadP$1)") (class "Default")
      (node (ref "S189") (pin "P$1") (pinfunction "P$1_P$1") (pintype "bidirectional"))
      (node (ref "S189") (pin "P$2") (pinfunction "P$2_P$2") (pintype "bidirectional"))
      (node (ref "S189") (pin "P$3") (pinfunction "P$3_P$3") (pintype "bidirectional"))
      (node (ref "S189") (pin "P$4") (pinfunction "P$4_P$4") (pintype "bidirectional"))
      (node (ref "S189") (pin "P$5") (pinfunction "P$5_P$5") (pintype "bidirectional"))
    )
    (net (code "228") (name "Net-(S190-PadP$1)") (class "Default")
      (node (ref "S190") (pin "P$1") (pinfunction "P$1_P$1") (pintype "bidirectional"))
      (node (ref "S190") (pin "P$2") (pinfunction "P$2_P$2") (pintype "bidirectional"))
      (node (ref "S190") (pin "P$3") (pinfunction "P$3_P$3") (pintype "bidirectional"))
      (node (ref "S190") (pin "P$4") (pinfunction "P$4_P$4") (pintype "bidirectional"))
      (node (ref "S190") (pin "P$5") (pinfunction "P$5_P$5") (pintype "bidirectional"))
    )
    (net (code "229") (name "Net-(S191-PadP$1)") (class "Default")
      (node (ref "S191") (pin "P$1") (pinfunction "P$1_P$1") (pintype "bidirectional"))
      (node (ref "S191") (pin "P$2") (pinfunction "P$2_P$2") (pintype "bidirectional"))
      (node (ref "S191") (pin "P$3") (pinfunction "P$3_P$3") (pintype "bidirectional"))
      (node (ref "S191") (pin "P$4") (pinfunction "P$4_P$4") (pintype "bidirectional"))
      (node (ref "S191") (pin "P$5") (pinfunction "P$5_P$5") (pintype "bidirectional"))
    )
    (net (code "230") (name "Net-(S192-PadP$1)") (class "Default")
      (node (ref "S192") (pin "P$1") (pinfunction "P$1_P$1") (pintype "bidirectional"))
      (node (ref "S192") (pin "P$2") (pinfunction "P$2_P$2") (pintype "bidirectional"))
      (node (ref "S192") (pin "P$3") (pinfunction "P$3_P$3") (pintype "bidirectional"))
      (node (ref "S192") (pin "P$4") (pinfunction "P$4_P$4") (pintype "bidirectional"))
      (node (ref "S192") (pin "P$5") (pinfunction "P$5_P$5") (pintype "bidirectional"))
    )
    (net (code "231") (name "Net-(S193-PadP$1)") (class "Default")
      (node (ref "S193") (pin "P$1") (pinfunction "P$1_P$1") (pintype "bidirectional"))
      (node (ref "S193") (pin "P$2") (pinfunction "P$2_P$2") (pintype "bidirectional"))
      (node (ref "S193") (pin "P$3") (pinfunction "P$3_P$3") (pintype "bidirectional"))
      (node (ref "S193") (pin "P$4") (pinfunction "P$4_P$4") (pintype "bidirectional"))
      (node (ref "S193") (pin "P$5") (pinfunction "P$5_P$5") (pintype "bidirectional"))
    )
    (net (code "232") (name "Net-(S194-PadP$1)") (class "Default")
      (node (ref "S194") (pin "P$1") (pinfunction "P$1_P$1") (pintype "bidirectional"))
      (node (ref "S194") (pin "P$2") (pinfunction "P$2_P$2") (pintype "bidirectional"))
      (node (ref "S194") (pin "P$3") (pinfunction "P$3_P$3") (pintype "bidirectional"))
      (node (ref "S194") (pin "P$4") (pinfunction "P$4_P$4") (pintype "bidirectional"))
      (node (ref "S194") (pin "P$5") (pinfunction "P$5_P$5") (pintype "bidirectional"))
    )
    (net (code "233") (name "Net-(S195-PadP$1)") (class "Default")
      (node (ref "S195") (pin "P$1") (pinfunction "P$1_P$1") (pintype "bidirectional"))
      (node (ref "S195") (pin "P$2") (pinfunction "P$2_P$2") (pintype "bidirectional"))
      (node (ref "S195") (pin "P$3") (pinfunction "P$3_P$3") (pintype "bidirectional"))
      (node (ref "S195") (pin "P$4") (pinfunction "P$4_P$4") (pintype "bidirectional"))
      (node (ref "S195") (pin "P$5") (pinfunction "P$5_P$5") (pintype "bidirectional"))
    )
    (net (code "234") (name "Net-(S196-PadP$1)") (class "Default")
      (node (ref "S196") (pin "P$1") (pinfunction "P$1_P$1") (pintype "bidirectional"))
      (node (ref "S196") (pin "P$2") (pinfunction "P$2_P$2") (pintype "bidirectional"))
      (node (ref "S196") (pin "P$3") (pinfunction "P$3_P$3") (pintype "bidirectional"))
      (node (ref "S196") (pin "P$4") (pinfunction "P$4_P$4") (pintype "bidirectional"))
      (node (ref "S196") (pin "P$5") (pinfunction "P$5_P$5") (pintype "bidirectional"))
    )
    (net (code "235") (name "Net-(S197-PadP$1)") (class "Default")
      (node (ref "S197") (pin "P$1") (pinfunction "P$1_P$1") (pintype "bidirectional"))
      (node (ref "S197") (pin "P$2") (pinfunction "P$2_P$2") (pintype "bidirectional"))
      (node (ref "S197") (pin "P$3") (pinfunction "P$3_P$3") (pintype "bidirectional"))
      (node (ref "S197") (pin "P$4") (pinfunction "P$4_P$4") (pintype "bidirectional"))
      (node (ref "S197") (pin "P$5") (pinfunction "P$5_P$5") (pintype "bidirectional"))
    )
    (net (code "236") (name "Net-(S198-PadP$1)") (class "Default")
      (node (ref "S198") (pin "P$1") (pinfunction "P$1_P$1") (pintype "bidirectional"))
      (node (ref "S198") (pin "P$2") (pinfunction "P$2_P$2") (pintype "bidirectional"))
      (node (ref "S198") (pin "P$3") (pinfunction "P$3_P$3") (pintype "bidirectional"))
      (node (ref "S198") (pin "P$4") (pinfunction "P$4_P$4") (pintype "bidirectional"))
      (node (ref "S198") (pin "P$5") (pinfunction "P$5_P$5") (pintype "bidirectional"))
    )
    (net (code "237") (name "Net-(S199-PadP$1)") (class "Default")
      (node (ref "S199") (pin "P$1") (pinfunction "P$1_P$1") (pintype "bidirectional"))
      (node (ref "S199") (pin "P$2") (pinfunction "P$2_P$2") (pintype "bidirectional"))
      (node (ref "S199") (pin "P$3") (pinfunction "P$3_P$3") (pintype "bidirectional"))
      (node (ref "S199") (pin "P$4") (pinfunction "P$4_P$4") (pintype "bidirectional"))
      (node (ref "S199") (pin "P$5") (pinfunction "P$5_P$5") (pintype "bidirectional"))
    )
    (net (code "238") (name "Net-(S200-PadP$1)") (class "Default")
      (node (ref "S200") (pin "P$1") (pinfunction "P$1_P$1") (pintype "bidirectional"))
      (node (ref "S200") (pin "P$2") (pinfunction "P$2_P$2") (pintype "bidirectional"))
      (node (ref "S200") (pin "P$3") (pinfunction "P$3_P$3") (pintype "bidirectional"))
      (node (ref "S200") (pin "P$4") (pinfunction "P$4_P$4") (pintype "bidirectional"))
      (node (ref "S200") (pin "P$5") (pinfunction "P$5_P$5") (pintype "bidirectional"))
    )
    (net (code "239") (name "Net-(S201-PadP$1)") (class "Default")
      (node (ref "S201") (pin "P$1") (pinfunction "P$1_P$1") (pintype "bidirectional"))
      (node (ref "S201") (pin "P$2") (pinfunction "P$2_P$2") (pintype "bidirectional"))
      (node (ref "S201") (pin "P$3") (pinfunction "P$3_P$3") (pintype "bidirectional"))
      (node (ref "S201") (pin "P$4") (pinfunction "P$4_P$4") (pintype "bidirectional"))
      (node (ref "S201") (pin "P$5") (pinfunction "P$5_P$5") (pintype "bidirectional"))
    )
    (net (code "240") (name "Net-(S202-PadP$1)") (class "Default")
      (node (ref "S202") (pin "P$1") (pinfunction "P$1_P$1") (pintype "bidirectional"))
      (node (ref "S202") (pin "P$2") (pinfunction "P$2_P$2") (pintype "bidirectional"))
      (node (ref "S202") (pin "P$3") (pinfunction "P$3_P$3") (pintype "bidirectional"))
      (node (ref "S202") (pin "P$4") (pinfunction "P$4_P$4") (pintype "bidirectional"))
      (node (ref "S202") (pin "P$5") (pinfunction "P$5_P$5") (pintype "bidirectional"))
    )
    (net (code "241") (name "Net-(S203-PadP$1)") (class "Default")
      (node (ref "S203") (pin "P$1") (pinfunction "P$1_P$1") (pintype "bidirectional"))
      (node (ref "S203") (pin "P$2") (pinfunction "P$2_P$2") (pintype "bidirectional"))
      (node (ref "S203") (pin "P$3") (pinfunction "P$3_P$3") (pintype "bidirectional"))
      (node (ref "S203") (pin "P$4") (pinfunction "P$4_P$4") (pintype "bidirectional"))
      (node (ref "S203") (pin "P$5") (pinfunction "P$5_P$5") (pintype "bidirectional"))
    )
    (net (code "242") (name "Net-(S204-PadP$1)") (class "Default")
      (node (ref "S204") (pin "P$1") (pinfunction "P$1_P$1") (pintype "bidirectional"))
      (node (ref "S204") (pin "P$2") (pinfunction "P$2_P$2") (pintype "bidirectional"))
      (node (ref "S204") (pin "P$3") (pinfunction "P$3_P$3") (pintype "bidirectional"))
      (node (ref "S204") (pin "P$4") (pinfunction "P$4_P$4") (pintype "bidirectional"))
      (node (ref "S204") (pin "P$5") (pinfunction "P$5_P$5") (pintype "bidirectional"))
    )
    (net (code "243") (name "Net-(S205-PadP$1)") (class "Default")
      (node (ref "S205") (pin "P$1") (pinfunction "P$1_P$1") (pintype "bidirectional"))
      (node (ref "S205") (pin "P$2") (pinfunction "P$2_P$2") (pintype "bidirectional"))
      (node (ref "S205") (pin "P$3") (pinfunction "P$3_P$3") (pintype "bidirectional"))
      (node (ref "S205") (pin "P$4") (pinfunction "P$4_P$4") (pintype "bidirectional"))
      (node (ref "S205") (pin "P$5") (pinfunction "P$5_P$5") (pintype "bidirectional"))
    )
    (net (code "244") (name "Net-(S206-PadP$1)") (class "Default")
      (node (ref "S206") (pin "P$1") (pinfunction "P$1_P$1") (pintype "bidirectional"))
      (node (ref "S206") (pin "P$2") (pinfunction "P$2_P$2") (pintype "bidirectional"))
      (node (ref "S206") (pin "P$3") (pinfunction "P$3_P$3") (pintype "bidirectional"))
      (node (ref "S206") (pin "P$4") (pinfunction "P$4_P$4") (pintype "bidirectional"))
      (node (ref "S206") (pin "P$5") (pinfunction "P$5_P$5") (pintype "bidirectional"))
    )
    (net (code "245") (name "Net-(S207-PadP$1)") (class "Default")
      (node (ref "S207") (pin "P$1") (pinfunction "P$1_P$1") (pintype "bidirectional"))
      (node (ref "S207") (pin "P$2") (pinfunction "P$2_P$2") (pintype "bidirectional"))
      (node (ref "S207") (pin "P$3") (pinfunction "P$3_P$3") (pintype "bidirectional"))
      (node (ref "S207") (pin "P$4") (pinfunction "P$4_P$4") (pintype "bidirectional"))
      (node (ref "S207") (pin "P$5") (pinfunction "P$5_P$5") (pintype "bidirectional"))
    )
    (net (code "246") (name "Net-(S208-PadP$1)") (class "Default")
      (node (ref "S208") (pin "P$1") (pinfunction "P$1_P$1") (pintype "bidirectional"))
      (node (ref "S208") (pin "P$2") (pinfunction "P$2_P$2") (pintype "bidirectional"))
      (node (ref "S208") (pin "P$3") (pinfunction "P$3_P$3") (pintype "bidirectional"))
      (node (ref "S208") (pin "P$4") (pinfunction "P$4_P$4") (pintype "bidirectional"))
      (node (ref "S208") (pin "P$5") (pinfunction "P$5_P$5") (pintype "bidirectional"))
    )
    (net (code "247") (name "Net-(S209-PadP$1)") (class "Default")
      (node (ref "S209") (pin "P$1") (pinfunction "P$1_P$1") (pintype "bidirectional"))
      (node (ref "S209") (pin "P$2") (pinfunction "P$2_P$2") (pintype "bidirectional"))
      (node (ref "S209") (pin "P$3") (pinfunction "P$3_P$3") (pintype "bidirectional"))
      (node (ref "S209") (pin "P$4") (pinfunction "P$4_P$4") (pintype "bidirectional"))
      (node (ref "S209") (pin "P$5") (pinfunction "P$5_P$5") (pintype "bidirectional"))
    )
    (net (code "248") (name "Net-(S210-PadP$1)") (class "Default")
      (node (ref "S210") (pin "P$1") (pinfunction "P$1_P$1") (pintype "bidirectional"))
      (node (ref "S210") (pin "P$2") (pinfunction "P$2_P$2") (pintype "bidirectional"))
      (node (ref "S210") (pin "P$3") (pinfunction "P$3_P$3") (pintype "bidirectional"))
      (node (ref "S210") (pin "P$4") (pinfunction "P$4_P$4") (pintype "bidirectional"))
      (node (ref "S210") (pin "P$5") (pinfunction "P$5_P$5") (pintype "bidirectional"))
    )
    (net (code "249") (name "Net-(S211-PadP$1)") (class "Default")
      (node (ref "S211") (pin "P$1") (pinfunction "P$1_P$1") (pintype "bidirectional"))
      (node (ref "S211") (pin "P$2") (pinfunction "P$2_P$2") (pintype "bidirectional"))
      (node (ref "S211") (pin "P$3") (pinfunction "P$3_P$3") (pintype "bidirectional"))
      (node (ref "S211") (pin "P$4") (pinfunction "P$4_P$4") (pintype "bidirectional"))
      (node (ref "S211") (pin "P$5") (pinfunction "P$5_P$5") (pintype "bidirectional"))
    )
    (net (code "250") (name "Net-(S212-PadP$1)") (class "Default")
      (node (ref "S212") (pin "P$1") (pinfunction "P$1_P$1") (pintype "bidirectional"))
      (node (ref "S212") (pin "P$2") (pinfunction "P$2_P$2") (pintype "bidirectional"))
      (node (ref "S212") (pin "P$3") (pinfunction "P$3_P$3") (pintype "bidirectional"))
      (node (ref "S212") (pin "P$4") (pinfunction "P$4_P$4") (pintype "bidirectional"))
      (node (ref "S212") (pin "P$5") (pinfunction "P$5_P$5") (pintype "bidirectional"))
    )
    (net (code "251") (name "Net-(S213-PadP$1)") (class "Default")
      (node (ref "S213") (pin "P$1") (pinfunction "P$1_P$1") (pintype "bidirectional"))
      (node (ref "S213") (pin "P$2") (pinfunction "P$2_P$2") (pintype "bidirectional"))
      (node (ref "S213") (pin "P$3") (pinfunction "P$3_P$3") (pintype "bidirectional"))
      (node (ref "S213") (pin "P$4") (pinfunction "P$4_P$4") (pintype "bidirectional"))
      (node (ref "S213") (pin "P$5") (pinfunction "P$5_P$5") (pintype "bidirectional"))
    )
    (net (code "252") (name "Net-(S214-PadP$1)") (class "Default")
      (node (ref "S214") (pin "P$1") (pinfunction "P$1_P$1") (pintype "bidirectional"))
      (node (ref "S214") (pin "P$2") (pinfunction "P$2_P$2") (pintype "bidirectional"))
      (node (ref "S214") (pin "P$3") (pinfunction "P$3_P$3") (pintype "bidirectional"))
      (node (ref "S214") (pin "P$4") (pinfunction "P$4_P$4") (pintype "bidirectional"))
      (node (ref "S214") (pin "P$5") (pinfunction "P$5_P$5") (pintype "bidirectional"))
    )
    (net (code "253") (name "Net-(S215-PadP$1)") (class "Default")
      (node (ref "S215") (pin "P$1") (pinfunction "P$1_P$1") (pintype "bidirectional"))
      (node (ref "S215") (pin "P$2") (pinfunction "P$2_P$2") (pintype "bidirectional"))
      (node (ref "S215") (pin "P$3") (pinfunction "P$3_P$3") (pintype "bidirectional"))
      (node (ref "S215") (pin "P$4") (pinfunction "P$4_P$4") (pintype "bidirectional"))
      (node (ref "S215") (pin "P$5") (pinfunction "P$5_P$5") (pintype "bidirectional"))
    )
    (net (code "254") (name "Net-(S216-PadP$1)") (class "Default")
      (node (ref "S216") (pin "P$1") (pinfunction "P$1_P$1") (pintype "bidirectional"))
      (node (ref "S216") (pin "P$2") (pinfunction "P$2_P$2") (pintype "bidirectional"))
      (node (ref "S216") (pin "P$3") (pinfunction "P$3_P$3") (pintype "bidirectional"))
      (node (ref "S216") (pin "P$4") (pinfunction "P$4_P$4") (pintype "bidirectional"))
      (node (ref "S216") (pin "P$5") (pinfunction "P$5_P$5") (pintype "bidirectional"))
    )
    (net (code "255") (name "Net-(S217-PadP$1)") (class "Default")
      (node (ref "S217") (pin "P$1") (pinfunction "P$1_P$1") (pintype "bidirectional"))
      (node (ref "S217") (pin "P$2") (pinfunction "P$2_P$2") (pintype "bidirectional"))
      (node (ref "S217") (pin "P$3") (pinfunction "P$3_P$3") (pintype "bidirectional"))
      (node (ref "S217") (pin "P$4") (pinfunction "P$4_P$4") (pintype "bidirectional"))
      (node (ref "S217") (pin "P$5") (pinfunction "P$5_P$5") (pintype "bidirectional"))
    )
    (net (code "256") (name "Net-(S218-PadP$1)") (class "Default")
      (node (ref "S218") (pin "P$1") (pinfunction "P$1_P$1") (pintype "bidirectional"))
      (node (ref "S218") (pin "P$2") (pinfunction "P$2_P$2") (pintype "bidirectional"))
      (node (ref "S218") (pin "P$3") (pinfunction "P$3_P$3") (pintype "bidirectional"))
      (node (ref "S218") (pin "P$4") (pinfunction "P$4_P$4") (pintype "bidirectional"))
      (node (ref "S218") (pin "P$5") (pinfunction "P$5_P$5") (pintype "bidirectional"))
    )
    (net (code "257") (name "Net-(S219-PadP$1)") (class "Default")
      (node (ref "S219") (pin "P$1") (pinfunction "P$1_P$1") (pintype "bidirectional"))
      (node (ref "S219") (pin "P$2") (pinfunction "P$2_P$2") (pintype "bidirectional"))
      (node (ref "S219") (pin "P$3") (pinfunction "P$3_P$3") (pintype "bidirectional"))
      (node (ref "S219") (pin "P$4") (pinfunction "P$4_P$4") (pintype "bidirectional"))
      (node (ref "S219") (pin "P$5") (pinfunction "P$5_P$5") (pintype "bidirectional"))
    )
    (net (code "258") (name "Net-(S220-PadP$1)") (class "Default")
      (node (ref "S220") (pin "P$1") (pinfunction "P$1_P$1") (pintype "bidirectional"))
      (node (ref "S220") (pin "P$2") (pinfunction "P$2_P$2") (pintype "bidirectional"))
      (node (ref "S220") (pin "P$3") (pinfunction "P$3_P$3") (pintype "bidirectional"))
      (node (ref "S220") (pin "P$4") (pinfunction "P$4_P$4") (pintype "bidirectional"))
      (node (ref "S220") (pin "P$5") (pinfunction "P$5_P$5") (pintype "bidirectional"))
    )
    (net (code "259") (name "Net-(S221-PadP$1)") (class "Default")
      (node (ref "S221") (pin "P$1") (pinfunction "P$1_P$1") (pintype "bidirectional"))
      (node (ref "S221") (pin "P$2") (pinfunction "P$2_P$2") (pintype "bidirectional"))
      (node (ref "S221") (pin "P$3") (pinfunction "P$3_P$3") (pintype "bidirectional"))
      (node (ref "S221") (pin "P$4") (pinfunction "P$4_P$4") (pintype "bidirectional"))
      (node (ref "S221") (pin "P$5") (pinfunction "P$5_P$5") (pintype "bidirectional"))
    )
    (net (code "260") (name "Net-(S222-PadP$1)") (class "Default")
      (node (ref "S222") (pin "P$1") (pinfunction "P$1_P$1") (pintype "bidirectional"))
      (node (ref "S222") (pin "P$2") (pinfunction "P$2_P$2") (pintype "bidirectional"))
      (node (ref "S222") (pin "P$3") (pinfunction "P$3_P$3") (pintype "bidirectional"))
      (node (ref "S222") (pin "P$4") (pinfunction "P$4_P$4") (pintype "bidirectional"))
      (node (ref "S222") (pin "P$5") (pinfunction "P$5_P$5") (pintype "bidirectional"))
    )
    (net (code "261") (name "Net-(S223-PadP$1)") (class "Default")
      (node (ref "S223") (pin "P$1") (pinfunction "P$1_P$1") (pintype "bidirectional"))
      (node (ref "S223") (pin "P$2") (pinfunction "P$2_P$2") (pintype "bidirectional"))
      (node (ref "S223") (pin "P$3") (pinfunction "P$3_P$3") (pintype "bidirectional"))
      (node (ref "S223") (pin "P$4") (pinfunction "P$4_P$4") (pintype "bidirectional"))
      (node (ref "S223") (pin "P$5") (pinfunction "P$5_P$5") (pintype "bidirectional"))
    )
    (net (code "262") (name "Net-(S224-PadP$1)") (class "Default")
      (node (ref "S224") (pin "P$1") (pinfunction "P$1_P$1") (pintype "bidirectional"))
      (node (ref "S224") (pin "P$2") (pinfunction "P$2_P$2") (pintype "bidirectional"))
      (node (ref "S224") (pin "P$3") (pinfunction "P$3_P$3") (pintype "bidirectional"))
      (node (ref "S224") (pin "P$4") (pinfunction "P$4_P$4") (pintype "bidirectional"))
      (node (ref "S224") (pin "P$5") (pinfunction "P$5_P$5") (pintype "bidirectional"))
    )
    (net (code "263") (name "Net-(S225-PadP$1)") (class "Default")
      (node (ref "S225") (pin "P$1") (pinfunction "P$1_P$1") (pintype "bidirectional"))
      (node (ref "S225") (pin "P$2") (pinfunction "P$2_P$2") (pintype "bidirectional"))
      (node (ref "S225") (pin "P$3") (pinfunction "P$3_P$3") (pintype "bidirectional"))
      (node (ref "S225") (pin "P$4") (pinfunction "P$4_P$4") (pintype "bidirectional"))
      (node (ref "S225") (pin "P$5") (pinfunction "P$5_P$5") (pintype "bidirectional"))
    )
    (net (code "264") (name "Net-(S226-PadP$1)") (class "Default")
      (node (ref "S226") (pin "P$1") (pinfunction "P$1_P$1") (pintype "bidirectional"))
      (node (ref "S226") (pin "P$2") (pinfunction "P$2_P$2") (pintype "bidirectional"))
      (node (ref "S226") (pin "P$3") (pinfunction "P$3_P$3") (pintype "bidirectional"))
      (node (ref "S226") (pin "P$4") (pinfunction "P$4_P$4") (pintype "bidirectional"))
      (node (ref "S226") (pin "P$5") (pinfunction "P$5_P$5") (pintype "bidirectional"))
    )
    (net (code "265") (name "Net-(SV2-Pad5)") (class "Default")
      (node (ref "SV2") (pin "5") (pinfunction "5_5") (pintype "passive"))
      (node (ref "SV2") (pin "6") (pinfunction "6_6") (pintype "passive"))
    )
    (net (code "266") (name "Net-(SV2-Pad7)") (class "Default")
      (node (ref "SV2") (pin "7") (pinfunction "7_7") (pintype "passive"))
      (node (ref "SV2") (pin "8") (pinfunction "8_8") (pintype "passive"))
    )
    (net (code "267") (name "Net-(SV2-Pad10)") (class "Default")
      (node (ref "SV2") (pin "10") (pinfunction "10_10") (pintype "passive"))
      (node (ref "SV2") (pin "9") (pinfunction "9_9") (pintype "passive"))
    )
    (net (code "268") (name "Net-(SV2-Pad11)") (class "Default")
      (node (ref "SV2") (pin "11") (pinfunction "11_11") (pintype "passive"))
      (node (ref "SV2") (pin "12") (pinfunction "12_12") (pintype "passive"))
    )
    (net (code "269") (name "Net-(SV2-Pad15)") (class "Default")
      (node (ref "SV2") (pin "15") (pinfunction "15_15") (pintype "passive"))
      (node (ref "SV2") (pin "16") (pinfunction "16_16") (pintype "passive"))
    )
    (net (code "270") (name "Net-(SV2-Pad17)") (class "Default")
      (node (ref "SV2") (pin "17") (pinfunction "17_17") (pintype "passive"))
      (node (ref "SV2") (pin "18") (pinfunction "18_18") (pintype "passive"))
    )
    (net (code "271") (name "Net-(SV2-Pad21)") (class "Default")
      (node (ref "SV2") (pin "21") (pinfunction "21_21") (pintype "passive"))
      (node (ref "SV2") (pin "22") (pinfunction "22_22") (pintype "passive"))
    )
    (net (code "272") (name "Net-(SV2-Pad23)") (class "Default")
      (node (ref "SV2") (pin "23") (pinfunction "23_23") (pintype "passive"))
      (node (ref "SV2") (pin "24") (pinfunction "24_24") (pintype "passive"))
    )
    (net (code "273") (name "Net-(SV2-Pad25)") (class "Default")
      (node (ref "SV2") (pin "25") (pinfunction "25_25") (pintype "passive"))
      (node (ref "SV2") (pin "26") (pinfunction "26_26") (pintype "passive"))
    )
    (net (code "274") (name "Net-(SV2-Pad27)") (class "Default")
      (node (ref "SV2") (pin "27") (pinfunction "27_27") (pintype "passive"))
      (node (ref "SV2") (pin "28") (pinfunction "28_28") (pintype "passive"))
    )
    (net (code "275") (name "Net-(SV2-Pad31)") (class "Default")
      (node (ref "SV2") (pin "31") (pinfunction "31_31") (pintype "passive"))
      (node (ref "SV2") (pin "32") (pinfunction "32_32") (pintype "passive"))
    )
    (net (code "276") (name "Net-(SV2-Pad35)") (class "Default")
      (node (ref "SV2") (pin "35") (pinfunction "35_35") (pintype "passive"))
      (node (ref "SV2") (pin "36") (pinfunction "36_36") (pintype "passive"))
    )
    (net (code "277") (name "Net-(SV2-Pad37)") (class "Default")
      (node (ref "SV2") (pin "37") (pinfunction "37_37") (pintype "passive"))
      (node (ref "SV2") (pin "38") (pinfunction "38_38") (pintype "passive"))
    )
    (net (code "278") (name "Net-(SV2-Pad39)") (class "Default")
      (node (ref "SV2") (pin "39") (pinfunction "39_39") (pintype "passive"))
      (node (ref "SV2") (pin "40") (pinfunction "40_40") (pintype "passive"))
    )
    (net (code "279") (name "Net-(SV4-Pad1)") (class "Default")
      (node (ref "SV4") (pin "1") (pinfunction "1_1") (pintype "passive"))
      (node (ref "SV4") (pin "2") (pinfunction "2_2") (pintype "passive"))
    )
    (net (code "280") (name "Net-(SV4-Pad3)") (class "Default")
      (node (ref "SV4") (pin "3") (pinfunction "3_3") (pintype "passive"))
      (node (ref "SV4") (pin "4") (pinfunction "4_4") (pintype "passive"))
    )
    (net (code "281") (name "Net-(SV4-Pad5)") (class "Default")
      (node (ref "SV4") (pin "5") (pinfunction "5_5") (pintype "passive"))
      (node (ref "SV4") (pin "6") (pinfunction "6_6") (pintype "passive"))
    )
    (net (code "282") (name "Net-(SV4-Pad7)") (class "Default")
      (node (ref "SV4") (pin "7") (pinfunction "7_7") (pintype "passive"))
      (node (ref "SV4") (pin "8") (pinfunction "8_8") (pintype "passive"))
    )
    (net (code "283") (name "Net-(SV4-Pad11)") (class "Default")
      (node (ref "SV4") (pin "11") (pinfunction "11_11") (pintype "passive"))
      (node (ref "SV4") (pin "12") (pinfunction "12_12") (pintype "passive"))
    )
    (net (code "284") (name "Net-(SV4-Pad13)") (class "Default")
      (node (ref "SV4") (pin "13") (pinfunction "13_13") (pintype "passive"))
      (node (ref "SV4") (pin "14") (pinfunction "14_14") (pintype "passive"))
    )
    (net (code "285") (name "Net-(SV4-Pad15)") (class "Default")
      (node (ref "SV4") (pin "15") (pinfunction "15_15") (pintype "passive"))
      (node (ref "SV4") (pin "16") (pinfunction "16_16") (pintype "passive"))
    )
    (net (code "286") (name "Net-(SV4-Pad17)") (class "Default")
      (node (ref "SV4") (pin "17") (pinfunction "17_17") (pintype "passive"))
      (node (ref "SV4") (pin "18") (pinfunction "18_18") (pintype "passive"))
    )
    (net (code "287") (name "Net-(SV4-Pad19)") (class "Default")
      (node (ref "SV4") (pin "19") (pinfunction "19_19") (pintype "passive"))
      (node (ref "SV4") (pin "20") (pinfunction "20_20") (pintype "passive"))
    )
    (net (code "288") (name "Net-(SV4-Pad21)") (class "Default")
      (node (ref "SV4") (pin "21") (pinfunction "21_21") (pintype "passive"))
      (node (ref "SV4") (pin "22") (pinfunction "22_22") (pintype "passive"))
    )
    (net (code "289") (name "Net-(SV4-Pad23)") (class "Default")
      (node (ref "SV4") (pin "23") (pinfunction "23_23") (pintype "passive"))
      (node (ref "SV4") (pin "24") (pinfunction "24_24") (pintype "passive"))
    )
    (net (code "290") (name "Net-(SV4-Pad27)") (class "Default")
      (node (ref "SV4") (pin "27") (pinfunction "27_27") (pintype "passive"))
      (node (ref "SV4") (pin "28") (pinfunction "28_28") (pintype "passive"))
    )
    (net (code "291") (name "Net-(SV4-Pad29)") (class "Default")
      (node (ref "SV4") (pin "29") (pinfunction "29_29") (pintype "passive"))
      (node (ref "SV4") (pin "30") (pinfunction "30_30") (pintype "passive"))
    )
    (net (code "292") (name "Net-(SV4-Pad31)") (class "Default")
      (node (ref "SV4") (pin "31") (pinfunction "31_31") (pintype "passive"))
      (node (ref "SV4") (pin "32") (pinfunction "32_32") (pintype "passive"))
    )
    (net (code "293") (name "Net-(SV4-Pad33)") (class "Default")
      (node (ref "SV4") (pin "33") (pinfunction "33_33") (pintype "passive"))
      (node (ref "SV4") (pin "34") (pinfunction "34_34") (pintype "passive"))
    )
    (net (code "294") (name "Net-(SV4-Pad35)") (class "Default")
      (node (ref "SV4") (pin "35") (pinfunction "35_35") (pintype "passive"))
      (node (ref "SV4") (pin "36") (pinfunction "36_36") (pintype "passive"))
    )
    (net (code "295") (name "Net-(SV4-Pad37)") (class "Default")
      (node (ref "SV4") (pin "37") (pinfunction "37_37") (pintype "passive"))
      (node (ref "SV4") (pin "38") (pinfunction "38_38") (pintype "passive"))
    )
    (net (code "296") (name "Net-(SV5-Pad1)") (class "Default")
      (node (ref "SV5") (pin "1") (pinfunction "1_1") (pintype "passive"))
      (node (ref "SV5") (pin "2") (pinfunction "2_2") (pintype "passive"))
    )
    (net (code "297") (name "Net-(SV5-Pad3)") (class "Default")
      (node (ref "SV5") (pin "3") (pinfunction "3_3") (pintype "passive"))
      (node (ref "SV5") (pin "4") (pinfunction "4_4") (pintype "passive"))
    )
    (net (code "298") (name "Net-(SV5-Pad5)") (class "Default")
      (node (ref "SV5") (pin "5") (pinfunction "5_5") (pintype "passive"))
      (node (ref "SV5") (pin "6") (pinfunction "6_6") (pintype "passive"))
    )
    (net (code "299") (name "Net-(SV5-Pad7)") (class "Default")
      (node (ref "SV5") (pin "7") (pinfunction "7_7") (pintype "passive"))
      (node (ref "SV5") (pin "8") (pinfunction "8_8") (pintype "passive"))
    )
    (net (code "300") (name "Net-(SV5-Pad10)") (class "Default")
      (node (ref "SV5") (pin "10") (pinfunction "10_10") (pintype "passive"))
      (node (ref "SV5") (pin "9") (pinfunction "9_9") (pintype "passive"))
    )
    (net (code "301") (name "Net-(SV5-Pad11)") (class "Default")
      (node (ref "SV5") (pin "11") (pinfunction "11_11") (pintype "passive"))
      (node (ref "SV5") (pin "12") (pinfunction "12_12") (pintype "passive"))
    )
    (net (code "302") (name "Net-(SV6-Pad1)") (class "Default")
      (node (ref "SV6") (pin "1") (pinfunction "1_1") (pintype "passive"))
      (node (ref "SV6") (pin "2") (pinfunction "2_2") (pintype "passive"))
    )
    (net (code "303") (name "Net-(SV6-Pad3)") (class "Default")
      (node (ref "SV6") (pin "3") (pinfunction "3_3") (pintype "passive"))
      (node (ref "SV6") (pin "4") (pinfunction "4_4") (pintype "passive"))
    )
    (net (code "304") (name "Net-(SV6-Pad5)") (class "Default")
      (node (ref "SV6") (pin "5") (pinfunction "5_5") (pintype "passive"))
      (node (ref "SV6") (pin "6") (pinfunction "6_6") (pintype "passive"))
    )
    (net (code "305") (name "Net-(SV6-Pad7)") (class "Default")
      (node (ref "SV6") (pin "7") (pinfunction "7_7") (pintype "passive"))
      (node (ref "SV6") (pin "8") (pinfunction "8_8") (pintype "passive"))
    )
    (net (code "306") (name "Net-(SV6-Pad10)") (class "Default")
      (node (ref "SV6") (pin "10") (pinfunction "10_10") (pintype "passive"))
      (node (ref "SV6") (pin "9") (pinfunction "9_9") (pintype "passive"))
    )
    (net (code "307") (name "Net-(SV6-Pad11)") (class "Default")
      (node (ref "SV6") (pin "11") (pinfunction "11_11") (pintype "passive"))
      (node (ref "SV6") (pin "12") (pinfunction "12_12") (pintype "passive"))
    )
    (net (code "308") (name "Net-(T1-B)") (class "Default")
      (node (ref "R1") (pin "2") (pinfunction "2_2") (pintype "passive"))
      (node (ref "T1") (pin "1") (pinfunction "B_1") (pintype "passive"))
    )
    (net (code "309") (name "Net-(T1-C)") (class "Default")
      (node (ref "J4") (pin "P$1") (pinfunction "P$1_P$1") (pintype "bidirectional"))
      (node (ref "J4") (pin "P$2") (pinfunction "P$2_P$2") (pintype "bidirectional"))
      (node (ref "J4") (pin "P$3") (pinfunction "P$3_P$3") (pintype "bidirectional"))
      (node (ref "T1") (pin "2") (pinfunction "C_2") (pintype "passive"))
    )
    (net (code "310") (name "Net-(T2-B)") (class "Default")
      (node (ref "R2") (pin "2") (pinfunction "2_2") (pintype "passive"))
      (node (ref "T2") (pin "1") (pinfunction "B_1") (pintype "passive"))
    )
    (net (code "311") (name "Net-(T2-C)") (class "Default")
      (node (ref "J23") (pin "P$1") (pinfunction "P$1_P$1") (pintype "bidirectional"))
      (node (ref "J23") (pin "P$2") (pinfunction "P$2_P$2") (pintype "bidirectional"))
      (node (ref "J23") (pin "P$3") (pinfunction "P$3_P$3") (pintype "bidirectional"))
      (node (ref "T2") (pin "2") (pinfunction "C_2") (pintype "passive"))
    )
    (net (code "312") (name "Net-(U$1-P3_SCLK)") (class "Default")
      (node (ref "J125") (pin "P$1") (pinfunction "P$1_P$1") (pintype "bidirectional"))
      (node (ref "J125") (pin "P$2") (pinfunction "P$2_P$2") (pintype "bidirectional"))
      (node (ref "J125") (pin "P$3") (pinfunction "P$3_P$3") (pintype "bidirectional"))
      (node (ref "U$1") (pin "3") (pinfunction "P3_SCLK_3") (pintype "bidirectional"))
    )
    (net (code "313") (name "Net-(U$1-P4_SDA{slash}SPIMOSI)") (class "Default")
      (node (ref "J126") (pin "P$1") (pinfunction "P$1_P$1") (pintype "bidirectional"))
      (node (ref "J126") (pin "P$2") (pinfunction "P$2_P$2") (pintype "bidirectional"))
      (node (ref "J126") (pin "P$3") (pinfunction "P$3_P$3") (pintype "bidirectional"))
      (node (ref "U$1") (pin "4") (pinfunction "P4_SDA/SPIMOSI_4") (pintype "bidirectional"))
    )
    (net (code "314") (name "Net-(U$1-P5_EDA{slash}AUX-DA)") (class "Default")
      (node (ref "J127") (pin "P$1") (pinfunction "P$1_P$1") (pintype "bidirectional"))
      (node (ref "J127") (pin "P$2") (pinfunction "P$2_P$2") (pintype "bidirectional"))
      (node (ref "J127") (pin "P$3") (pinfunction "P$3_P$3") (pintype "bidirectional"))
      (node (ref "U$1") (pin "5") (pinfunction "P5_EDA/AUX-DA_5") (pintype "bidirectional"))
    )
    (net (code "315") (name "Net-(U$1-P6_ECL{slash}AUX-CL)") (class "Default")
      (node (ref "J128") (pin "P$1") (pinfunction "P$1_P$1") (pintype "bidirectional"))
      (node (ref "J128") (pin "P$2") (pinfunction "P$2_P$2") (pintype "bidirectional"))
      (node (ref "J128") (pin "P$3") (pinfunction "P$3_P$3") (pintype "bidirectional"))
      (node (ref "U$1") (pin "6") (pinfunction "P6_ECL/AUX-CL_6") (pintype "bidirectional"))
    )
    (net (code "316") (name "Net-(U$1-P7_ADO{slash}SPIMISO)") (class "Default")
      (node (ref "J129") (pin "P$1") (pinfunction "P$1_P$1") (pintype "bidirectional"))
      (node (ref "J129") (pin "P$2") (pinfunction "P$2_P$2") (pintype "bidirectional"))
      (node (ref "J129") (pin "P$3") (pinfunction "P$3_P$3") (pintype "bidirectional"))
      (node (ref "U$1") (pin "7") (pinfunction "P7_ADO/SPIMISO_7") (pintype "bidirectional"))
    )
    (net (code "317") (name "Net-(U$1-P8_INT)") (class "Default")
      (node (ref "J130") (pin "P$1") (pinfunction "P$1_P$1") (pintype "bidirectional"))
      (node (ref "J130") (pin "P$2") (pinfunction "P$2_P$2") (pintype "bidirectional"))
      (node (ref "J130") (pin "P$3") (pinfunction "P$3_P$3") (pintype "bidirectional"))
      (node (ref "U$1") (pin "8") (pinfunction "P8_INT_8") (pintype "bidirectional"))
    )
    (net (code "318") (name "Net-(U$1-P9_NCS)") (class "Default")
      (node (ref "J131") (pin "P$1") (pinfunction "P$1_P$1") (pintype "bidirectional"))
      (node (ref "J131") (pin "P$2") (pinfunction "P$2_P$2") (pintype "bidirectional"))
      (node (ref "J131") (pin "P$3") (pinfunction "P$3_P$3") (pintype "bidirectional"))
      (node (ref "U$1") (pin "9") (pinfunction "P9_NCS_9") (pintype "bidirectional"))
    )
    (net (code "319") (name "Net-(U$1-P10_FSYNC)") (class "Default")
      (node (ref "J132") (pin "P$1") (pinfunction "P$1_P$1") (pintype "bidirectional"))
      (node (ref "J132") (pin "P$2") (pinfunction "P$2_P$2") (pintype "bidirectional"))
      (node (ref "J132") (pin "P$3") (pinfunction "P$3_P$3") (pintype "bidirectional"))
      (node (ref "U$1") (pin "10") (pinfunction "P10_FSYNC_10") (pintype "bidirectional"))
    )
    (net (code "320") (name "Net-(U1-MODE)") (class "Default")
      (node (ref "JP2") (pin "1") (pinfunction "1_1") (pintype "passive"))
      (node (ref "R4") (pin "1") (pinfunction "1_1") (pintype "passive"))
      (node (ref "U1") (pin "14") (pinfunction "MODE_14") (pintype "bidirectional"))
    )
    (net (code "321") (name "Net-(U1-PHASE)") (class "Default")
      (node (ref "J196") (pin "P$1") (pinfunction "P$1_P$1") (pintype "bidirectional"))
      (node (ref "J196") (pin "P$2") (pinfunction "P$2_P$2") (pintype "bidirectional"))
      (node (ref "U1") (pin "7") (pinfunction "PHASE_7") (pintype "bidirectional"))
    )
    (net (code "322") (name "Net-(U1-RC)") (class "Default")
      (node (ref "C14") (pin "1") (pinfunction "1_1") (pintype "passive"))
      (node (ref "R3") (pin "2") (pinfunction "2_2") (pintype "passive"))
      (node (ref "U1") (pin "3") (pinfunction "RC_3") (pintype "bidirectional"))
    )
    (net (code "323") (name "Net-(U1-~{BRAKE})") (class "Default")
      (node (ref "R8") (pin "1") (pinfunction "1_1") (pintype "passive"))
      (node (ref "U1") (pin "1") (pinfunction "~{BRAKE}_1") (pintype "bidirectional"))
    )
    (net (code "324") (name "Net-(U2-CPH)") (class "Default")
      (node (ref "C19") (pin "2") (pinfunction "2_2") (pintype "passive"))
      (node (ref "U2") (pin "P$13") (pinfunction "CPH_P$13") (pintype "bidirectional"))
    )
    (net (code "325") (name "Net-(U2-CPL)") (class "Default")
      (node (ref "C19") (pin "1") (pinfunction "1_1") (pintype "passive"))
      (node (ref "U2") (pin "P$14") (pinfunction "CPL_P$14") (pintype "bidirectional"))
    )
    (net (code "326") (name "Net-(U2-IPROPI)") (class "Default")
      (node (ref "R41") (pin "1") (pinfunction "1_1") (pintype "passive"))
      (node (ref "U2") (pin "P$6") (pinfunction "IPROPI_P$6") (pintype "bidirectional"))
    )
    (net (code "327") (name "Net-(U2-NFAULT)") (class "Default")
      (node (ref "J78") (pin "P$1") (pinfunction "P$1_P$1") (pintype "bidirectional"))
      (node (ref "J78") (pin "P$2") (pinfunction "P$2_P$2") (pintype "bidirectional"))
      (node (ref "R42") (pin "2") (pinfunction "2_2") (pintype "passive"))
      (node (ref "U2") (pin "P$4") (pinfunction "NFAULT_P$4") (pintype "bidirectional"))
    )
    (net (code "328") (name "Net-(U2-VCP)") (class "Default")
      (node (ref "C17") (pin "1") (pinfunction "1_1") (pintype "passive"))
      (node (ref "U2") (pin "P$12") (pinfunction "VCP_P$12") (pintype "bidirectional"))
    )
    (net (code "329") (name "Net-(U2-VREF)") (class "Default")
      (node (ref "TRIMPOT1") (pin "3") (pinfunction "3_3") (pintype "passive"))
      (node (ref "TRIMPOT1") (pin "4") (pinfunction "4_4") (pintype "passive"))
      (node (ref "U2") (pin "P$5") (pinfunction "VREF_P$5") (pintype "bidirectional"))
    )
    (net (code "330") (name "Net-(U3-P1_OSCI)") (class "Default")
      (node (ref "Q1") (pin "2") (pinfunction "2_2") (pintype "passive"))
      (node (ref "U3") (pin "1") (pinfunction "P1_OSCI_1") (pintype "bidirectional"))
    )
    (net (code "331") (name "Net-(U3-P2_OSC0)") (class "Default")
      (node (ref "Q1") (pin "1") (pinfunction "1_1") (pintype "passive"))
      (node (ref "U3") (pin "2") (pinfunction "P2_OSC0_2") (pintype "bidirectional"))
    )
    (net (code "332") (name "Net-(U3-P3_VBACK)") (class "Default")
      (node (ref "G1") (pin "+") (pinfunction "+_+") (pintype "passive"))
      (node (ref "U3") (pin "3") (pinfunction "P3_VBACK_3") (pintype "bidirectional"))
    )
    (net (code "333") (name "Net-(U3-P7_IRQ)") (class "Default")
      (node (ref "J1") (pin "P$1") (pinfunction "P$1_P$1") (pintype "bidirectional"))
      (node (ref "J1") (pin "P$2") (pinfunction "P$2_P$2") (pintype "bidirectional"))
      (node (ref "J1") (pin "P$3") (pinfunction "P$3_P$3") (pintype "bidirectional"))
      (node (ref "U3") (pin "7") (pinfunction "P7_IRQ_7") (pintype "bidirectional"))
    )
    (net (code "334") (name "Net-(U4-CPH)") (class "Default")
      (node (ref "C24") (pin "2") (pinfunction "2_2") (pintype "passive"))
      (node (ref "U4") (pin "P$13") (pinfunction "CPH_P$13") (pintype "bidirectional"))
    )
    (net (code "335") (name "Net-(U4-CPL)") (class "Default")
      (node (ref "C24") (pin "1") (pinfunction "1_1") (pintype "passive"))
      (node (ref "U4") (pin "P$14") (pinfunction "CPL_P$14") (pintype "bidirectional"))
    )
    (net (code "336") (name "Net-(U4-IPROPI)") (class "Default")
      (node (ref "R43") (pin "1") (pinfunction "1_1") (pintype "passive"))
      (node (ref "U4") (pin "P$6") (pinfunction "IPROPI_P$6") (pintype "bidirectional"))
    )
    (net (code "337") (name "Net-(U4-NFAULT)") (class "Default")
      (node (ref "J81") (pin "P$1") (pinfunction "P$1_P$1") (pintype "bidirectional"))
      (node (ref "J81") (pin "P$2") (pinfunction "P$2_P$2") (pintype "bidirectional"))
      (node (ref "R44") (pin "2") (pinfunction "2_2") (pintype "passive"))
      (node (ref "U4") (pin "P$4") (pinfunction "NFAULT_P$4") (pintype "bidirectional"))
    )
    (net (code "338") (name "Net-(U4-VCP)") (class "Default")
      (node (ref "C23") (pin "1") (pinfunction "1_1") (pintype "passive"))
      (node (ref "U4") (pin "P$12") (pinfunction "VCP_P$12") (pintype "bidirectional"))
    )
    (net (code "339") (name "Net-(U4-VREF)") (class "Default")
      (node (ref "TRIMPOT2") (pin "3") (pinfunction "3_3") (pintype "passive"))
      (node (ref "TRIMPOT2") (pin "4") (pinfunction "4_4") (pintype "passive"))
      (node (ref "U4") (pin "P$5") (pinfunction "VREF_P$5") (pintype "bidirectional"))
    )
    (net (code "340") (name "Net-(U5-MODE)") (class "Default")
      (node (ref "JP3") (pin "1") (pinfunction "1_1") (pintype "passive"))
      (node (ref "R5") (pin "1") (pinfunction "1_1") (pintype "passive"))
      (node (ref "U5") (pin "14") (pinfunction "MODE_14") (pintype "bidirectional"))
    )
    (net (code "341") (name "Net-(U5-PHASE)") (class "Default")
      (node (ref "J197") (pin "P$1") (pinfunction "P$1_P$1") (pintype "bidirectional"))
      (node (ref "J197") (pin "P$2") (pinfunction "P$2_P$2") (pintype "bidirectional"))
      (node (ref "U5") (pin "7") (pinfunction "PHASE_7") (pintype "bidirectional"))
    )
    (net (code "342") (name "Net-(U5-RC)") (class "Default")
      (node (ref "C2") (pin "1") (pinfunction "1_1") (pintype "passive"))
      (node (ref "R7") (pin "2") (pinfunction "2_2") (pintype "passive"))
      (node (ref "U5") (pin "3") (pinfunction "RC_3") (pintype "bidirectional"))
    )
    (net (code "343") (name "Net-(U5-~{BRAKE})") (class "Default")
      (node (ref "R6") (pin "1") (pinfunction "1_1") (pintype "passive"))
      (node (ref "U5") (pin "1") (pinfunction "~{BRAKE}_1") (pintype "bidirectional"))
    )
    (net (code "344") (name "Net-(U7-ADJ)") (class "Default")
      (node (ref "R24") (pin "1") (pinfunction "1_1") (pintype "passive"))
      (node (ref "R25") (pin "2") (pinfunction "2_2") (pintype "passive"))
      (node (ref "U7") (pin "P$5") (pinfunction "ADJ_P$5") (pintype "bidirectional"))
    )
    (net (code "345") (name "Net-(U8-+IN)") (class "Default")
      (node (ref "J8") (pin "P$1") (pinfunction "P$1_P$1") (pintype "bidirectional"))
      (node (ref "J8") (pin "P$2") (pinfunction "P$2_P$2") (pintype "bidirectional"))
      (node (ref "U8") (pin "3") (pinfunction "+IN_3") (pintype "input"))
    )
    (net (code "346") (name "Net-(U8-GAIN1)") (class "Default")
      (node (ref "R10") (pin "2") (pinfunction "2_2") (pintype "passive"))
      (node (ref "U8") (pin "1") (pinfunction "GAIN1_1") (pintype "passive"))
    )
    (net (code "347") (name "Net-(U8-GAIN2)") (class "Default")
      (node (ref "C21") (pin "-") (pinfunction "-_-") (pintype "passive"))
      (node (ref "U8") (pin "8") (pinfunction "GAIN2_8") (pintype "passive"))
    )
    (net (code "348") (name "POWER") (class "Default")
      (node (ref "B2") (pin "P$1") (pinfunction "BAT+_P$1") (pintype "bidirectional"))
      (node (ref "C1") (pin "+") (pinfunction "+_+") (pintype "passive"))
      (node (ref "C12") (pin "+") (pinfunction "+_+") (pintype "passive"))
      (node (ref "C13") (pin "+") (pinfunction "+_+") (pintype "passive"))
      (node (ref "C15") (pin "+") (pinfunction "+_+") (pintype "passive"))
      (node (ref "C16") (pin "1") (pinfunction "1_1") (pintype "passive"))
      (node (ref "C17") (pin "2") (pinfunction "2_2") (pintype "passive"))
      (node (ref "C20") (pin "+") (pinfunction "+_+") (pintype "passive"))
      (node (ref "C22") (pin "1") (pinfunction "1_1") (pintype "passive"))
      (node (ref "C23") (pin "2") (pinfunction "2_2") (pintype "passive"))
      (node (ref "C25") (pin "+") (pinfunction "+_+") (pintype "passive"))
      (node (ref "C27") (pin "+") (pinfunction "+_+") (pintype "passive"))
      (node (ref "C28") (pin "+") (pinfunction "+_+") (pintype "passive"))
      (node (ref "C3") (pin "1") (pinfunction "1_1") (pintype "passive"))
      (node (ref "C5") (pin "1") (pinfunction "1_1") (pintype "passive"))
      (node (ref "DCDC3.3V") (pin "1") (pinfunction "1_1") (pintype "passive"))
      (node (ref "DCDC5V") (pin "1") (pinfunction "1_1") (pintype "passive"))
      (node (ref "J5") (pin "1") (pinfunction "1_1") (pintype "passive"))
      (node (ref "POWER") (pin "2") (pinfunction "2_2") (pintype "passive"))
      (node (ref "S141") (pin "P$1") (pinfunction "P$1_P$1") (pintype "bidirectional"))
      (node (ref "S141") (pin "P$2") (pinfunction "P$2_P$2") (pintype "bidirectional"))
      (node (ref "S141") (pin "P$3") (pinfunction "P$3_P$3") (pintype "bidirectional"))
      (node (ref "S141") (pin "P$4") (pinfunction "P$4_P$4") (pintype "bidirectional"))
      (node (ref "S141") (pin "P$5") (pinfunction "P$5_P$5") (pintype "bidirectional"))
      (node (ref "U1") (pin "16") (pinfunction "VBB_16") (pintype "bidirectional"))
      (node (ref "U1") (pin "9") (pinfunction "VBB_9") (pintype "bidirectional"))
      (node (ref "U2") (pin "P$11") (pinfunction "VM_P$11") (pintype "bidirectional"))
      (node (ref "U4") (pin "P$11") (pinfunction "VM_P$11") (pintype "bidirectional"))
      (node (ref "U5") (pin "16") (pinfunction "VBB_16") (pintype "bidirectional"))
      (node (ref "U5") (pin "9") (pinfunction "VBB_9") (pintype "bidirectional"))
      (node (ref "U6") (pin "P$1") (pinfunction "~{SHDN}_P$1") (pintype "bidirectional"))
      (node (ref "U6") (pin "P$2") (pinfunction "IN_P$2") (pintype "bidirectional"))
      (node (ref "U7") (pin "P$1") (pinfunction "~{SHDN}_P$1") (pintype "bidirectional"))
      (node (ref "U7") (pin "P$2") (pinfunction "IN_P$2") (pintype "bidirectional"))
    )
    (net (code "349") (name "RCPWR") (class "Default")
      (node (ref "S139") (pin "P$1") (pinfunction "P$1_P$1") (pintype "bidirectional"))
      (node (ref "S139") (pin "P$2") (pinfunction "P$2_P$2") (pintype "bidirectional"))
      (node (ref "S139") (pin "P$3") (pinfunction "P$3_P$3") (pintype "bidirectional"))
      (node (ref "S139") (pin "P$4") (pinfunction "P$4_P$4") (pintype "bidirectional"))
      (node (ref "S139") (pin "P$5") (pinfunction "P$5_P$5") (pintype "bidirectional"))
      (node (ref "S147") (pin "P$1") (pinfunction "P$1_P$1") (pintype "bidirectional"))
      (node (ref "S147") (pin "P$2") (pinfunction "P$2_P$2") (pintype "bidirectional"))
      (node (ref "S147") (pin "P$3") (pinfunction "P$3_P$3") (pintype "bidirectional"))
      (node (ref "S147") (pin "P$4") (pinfunction "P$4_P$4") (pintype "bidirectional"))
      (node (ref "S147") (pin "P$5") (pinfunction "P$5_P$5") (pintype "bidirectional"))
    )
    (net (code "350") (name "RESET") (class "Default")
      (node (ref "J98") (pin "P$1") (pinfunction "P$1_P$1") (pintype "bidirectional"))
      (node (ref "J98") (pin "P$2") (pinfunction "P$2_P$2") (pintype "bidirectional"))
      (node (ref "J98") (pin "P$3") (pinfunction "P$3_P$3") (pintype "bidirectional"))
      (node (ref "L1") (pin "P$16") (pinfunction "RST_P$16") (pintype "bidirectional"))
    )
    (net (code "351") (name "RESET_2") (class "Default")
      (node (ref "J157") (pin "P$1") (pinfunction "P$1_P$1") (pintype "bidirectional"))
      (node (ref "J157") (pin "P$2") (pinfunction "P$2_P$2") (pintype "bidirectional"))
      (node (ref "J157") (pin "P$3") (pinfunction "P$3_P$3") (pintype "bidirectional"))
      (node (ref "L1") (pin "P$56") (pinfunction "RST_2_P$56") (pintype "bidirectional"))
    )
    (net (code "352") (name "SCL") (class "Default")
      (node (ref "J2") (pin "P$1") (pinfunction "P$1_P$1") (pintype "bidirectional"))
      (node (ref "J2") (pin "P$2") (pinfunction "P$2_P$2") (pintype "bidirectional"))
      (node (ref "J2") (pin "P$3") (pinfunction "P$3_P$3") (pintype "bidirectional"))
      (node (ref "U3") (pin "6") (pinfunction "P6_SCL_6") (pintype "bidirectional"))
    )
    (net (code "353") (name "SDA") (class "Default")
      (node (ref "J3") (pin "P$1") (pinfunction "P$1_P$1") (pintype "bidirectional"))
      (node (ref "J3") (pin "P$2") (pinfunction "P$2_P$2") (pintype "bidirectional"))
      (node (ref "J3") (pin "P$3") (pinfunction "P$3_P$3") (pintype "bidirectional"))
      (node (ref "U3") (pin "5") (pinfunction "P5_SDA_5") (pintype "bidirectional"))
    )
    (net (code "354") (name "VCC") (class "Default")
      (node (ref "C10") (pin "1") (pinfunction "1_1") (pintype "passive"))
      (node (ref "C11") (pin "1") (pinfunction "1_1") (pintype "passive"))
      (node (ref "C26") (pin "1") (pinfunction "1_1") (pintype "passive"))
      (node (ref "C6") (pin "1") (pinfunction "1_1") (pintype "passive"))
      (node (ref "C7") (pin "+") (pinfunction "+_+") (pintype "passive"))
      (node (ref "C9") (pin "1") (pinfunction "1_1") (pintype "passive"))
      (node (ref "IC1") (pin "14") (pinfunction "VCC_14") (pintype "power_in"))
      (node (ref "IC2") (pin "14") (pinfunction "VCC_14") (pintype "power_in"))
      (node (ref "IC3") (pin "14") (pinfunction "VCC_14") (pintype "power_in"))
      (node (ref "IC4") (pin "14") (pinfunction "VCC_14") (pintype "power_in"))
      (node (ref "J10") (pin "P$1") (pinfunction "P$1_P$1") (pintype "bidirectional"))
      (node (ref "J10") (pin "P$2") (pinfunction "P$2_P$2") (pintype "bidirectional"))
      (node (ref "J10") (pin "P$3") (pinfunction "P$3_P$3") (pintype "bidirectional"))
      (node (ref "J123") (pin "P$1") (pinfunction "P$1_P$1") (pintype "bidirectional"))
      (node (ref "J123") (pin "P$2") (pinfunction "P$2_P$2") (pintype "bidirectional"))
      (node (ref "J123") (pin "P$3") (pinfunction "P$3_P$3") (pintype "bidirectional"))
      (node (ref "J177") (pin "P$1") (pinfunction "P$1_P$1") (pintype "bidirectional"))
      (node (ref "J177") (pin "P$2") (pinfunction "P$2_P$2") (pintype "bidirectional"))
      (node (ref "J177") (pin "P$3") (pinfunction "P$3_P$3") (pintype "bidirectional"))
      (node (ref "J65") (pin "P$1") (pinfunction "P$1_P$1") (pintype "bidirectional"))
      (node (ref "J65") (pin "P$2") (pinfunction "P$2_P$2") (pintype "bidirectional"))
      (node (ref "JP1") (pin "2") (pinfunction "2_2") (pintype "passive"))
      (node (ref "L1") (pin "P$1") (pinfunction "3.3V_1_P$1") (pintype "bidirectional"))
      (node (ref "L1") (pin "P$41") (pinfunction "3.3V_2_P$41") (pintype "bidirectional"))
      (node (ref "R11") (pin "2") (pinfunction "2_2") (pintype "passive"))
      (node (ref "R12") (pin "2") (pinfunction "2_2") (pintype "passive"))
      (node (ref "R13") (pin "2") (pinfunction "2_2") (pintype "passive"))
      (node (ref "R14") (pin "2") (pinfunction "2_2") (pintype "passive"))
      (node (ref "R15") (pin "2") (pinfunction "2_2") (pintype "passive"))
      (node (ref "R16") (pin "2") (pinfunction "2_2") (pintype "passive"))
      (node (ref "R17") (pin "2") (pinfunction "2_2") (pintype "passive"))
      (node (ref "R18") (pin "2") (pinfunction "2_2") (pintype "passive"))
      (node (ref "R19") (pin "2") (pinfunction "2_2") (pintype "passive"))
      (node (ref "R20") (pin "2") (pinfunction "2_2") (pintype "passive"))
      (node (ref "R21") (pin "2") (pinfunction "2_2") (pintype "passive"))
      (node (ref "R22") (pin "2") (pinfunction "2_2") (pintype "passive"))
      (node (ref "R23") (pin "2") (pinfunction "2_2") (pintype "passive"))
      (node (ref "R27") (pin "2") (pinfunction "2_2") (pintype "passive"))
      (node (ref "R28") (pin "2") (pinfunction "2_2") (pintype "passive"))
      (node (ref "R29") (pin "2") (pinfunction "2_2") (pintype "passive"))
      (node (ref "R30") (pin "2") (pinfunction "2_2") (pintype "passive"))
      (node (ref "R31") (pin "2") (pinfunction "2_2") (pintype "passive"))
      (node (ref "R32") (pin "2") (pinfunction "2_2") (pintype "passive"))
      (node (ref "R33") (pin "2") (pinfunction "2_2") (pintype "passive"))
      (node (ref "R34") (pin "2") (pinfunction "2_2") (pintype "passive"))
      (node (ref "R35") (pin "2") (pinfunction "2_2") (pintype "passive"))
      (node (ref "R36") (pin "2") (pinfunction "2_2") (pintype "passive"))
      (node (ref "R37") (pin "2") (pinfunction "2_2") (pintype "passive"))
      (node (ref "R38") (pin "2") (pinfunction "2_2") (pintype "passive"))
      (node (ref "R39") (pin "2") (pinfunction "2_2") (pintype "passive"))
      (node (ref "R4") (pin "2") (pinfunction "2_2") (pintype "passive"))
      (node (ref "R42") (pin "1") (pinfunction "1_1") (pintype "passive"))
      (node (ref "R44") (pin "1") (pinfunction "1_1") (pintype "passive"))
      (node (ref "R5") (pin "2") (pinfunction "2_2") (pintype "passive"))
      (node (ref "R6") (pin "2") (pinfunction "2_2") (pintype "passive"))
      (node (ref "R8") (pin "2") (pinfunction "2_2") (pintype "passive"))
      (node (ref "R9") (pin "1") (pinfunction "1_1") (pintype "passive"))
      (node (ref "S42") (pin "P$1") (pinfunction "P$1_P$1") (pintype "bidirectional"))
      (node (ref "S42") (pin "P$10") (pinfunction "P$10_P$10") (pintype "bidirectional"))
      (node (ref "S42") (pin "P$2") (pinfunction "P$2_P$2") (pintype "bidirectional"))
      (node (ref "S42") (pin "P$3") (pinfunction "P$3_P$3") (pintype "bidirectional"))
      (node (ref "S42") (pin "P$4") (pinfunction "P$4_P$4") (pintype "bidirectional"))
      (node (ref "S42") (pin "P$5") (pinfunction "P$5_P$5") (pintype "bidirectional"))
      (node (ref "S42") (pin "P$6") (pinfunction "P$6_P$6") (pintype "bidirectional"))
      (node (ref "S42") (pin "P$7") (pinfunction "P$7_P$7") (pintype "bidirectional"))
      (node (ref "S42") (pin "P$8") (pinfunction "P$8_P$8") (pintype "bidirectional"))
      (node (ref "S42") (pin "P$9") (pinfunction "P$9_P$9") (pintype "bidirectional"))
      (node (ref "S50") (pin "P$1") (pinfunction "P$1_P$1") (pintype "bidirectional"))
      (node (ref "S50") (pin "P$10") (pinfunction "P$10_P$10") (pintype "bidirectional"))
      (node (ref "S50") (pin "P$2") (pinfunction "P$2_P$2") (pintype "bidirectional"))
      (node (ref "S50") (pin "P$3") (pinfunction "P$3_P$3") (pintype "bidirectional"))
      (node (ref "S50") (pin "P$4") (pinfunction "P$4_P$4") (pintype "bidirectional"))
      (node (ref "S50") (pin "P$5") (pinfunction "P$5_P$5") (pintype "bidirectional"))
      (node (ref "S50") (pin "P$6") (pinfunction "P$6_P$6") (pintype "bidirectional"))
      (node (ref "S50") (pin "P$7") (pinfunction "P$7_P$7") (pintype "bidirectional"))
      (node (ref "S50") (pin "P$8") (pinfunction "P$8_P$8") (pintype "bidirectional"))
      (node (ref "S50") (pin "P$9") (pinfunction "P$9_P$9") (pintype "bidirectional"))
      (node (ref "S53") (pin "P$1") (pinfunction "P$1_P$1") (pintype "bidirectional"))
      (node (ref "S53") (pin "P$10") (pinfunction "P$10_P$10") (pintype "bidirectional"))
      (node (ref "S53") (pin "P$2") (pinfunction "P$2_P$2") (pintype "bidirectional"))
      (node (ref "S53") (pin "P$3") (pinfunction "P$3_P$3") (pintype "bidirectional"))
      (node (ref "S53") (pin "P$4") (pinfunction "P$4_P$4") (pintype "bidirectional"))
      (node (ref "S53") (pin "P$5") (pinfunction "P$5_P$5") (pintype "bidirectional"))
      (node (ref "S53") (pin "P$6") (pinfunction "P$6_P$6") (pintype "bidirectional"))
      (node (ref "S53") (pin "P$7") (pinfunction "P$7_P$7") (pintype "bidirectional"))
      (node (ref "S53") (pin "P$8") (pinfunction "P$8_P$8") (pintype "bidirectional"))
      (node (ref "S53") (pin "P$9") (pinfunction "P$9_P$9") (pintype "bidirectional"))
      (node (ref "S58") (pin "P$1") (pinfunction "P$1_P$1") (pintype "bidirectional"))
      (node (ref "S58") (pin "P$10") (pinfunction "P$10_P$10") (pintype "bidirectional"))
      (node (ref "S58") (pin "P$2") (pinfunction "P$2_P$2") (pintype "bidirectional"))
      (node (ref "S58") (pin "P$3") (pinfunction "P$3_P$3") (pintype "bidirectional"))
      (node (ref "S58") (pin "P$4") (pinfunction "P$4_P$4") (pintype "bidirectional"))
      (node (ref "S58") (pin "P$5") (pinfunction "P$5_P$5") (pintype "bidirectional"))
      (node (ref "S58") (pin "P$6") (pinfunction "P$6_P$6") (pintype "bidirectional"))
      (node (ref "S58") (pin "P$7") (pinfunction "P$7_P$7") (pintype "bidirectional"))
      (node (ref "S58") (pin "P$8") (pinfunction "P$8_P$8") (pintype "bidirectional"))
      (node (ref "S58") (pin "P$9") (pinfunction "P$9_P$9") (pintype "bidirectional"))
      (node (ref "TRIMPOT1") (pin "1") (pinfunction "1_1") (pintype "passive"))
      (node (ref "TRIMPOT1") (pin "2") (pinfunction "2_2") (pintype "passive"))
      (node (ref "TRIMPOT2") (pin "1") (pinfunction "1_1") (pintype "passive"))
      (node (ref "TRIMPOT2") (pin "2") (pinfunction "2_2") (pintype "passive"))
      (node (ref "U$1") (pin "1") (pinfunction "P1_VCC_1") (pintype "bidirectional"))
      (node (ref "U1") (pin "2") (pinfunction "REF_2") (pintype "bidirectional"))
      (node (ref "U1") (pin "6") (pinfunction "VCC_6") (pintype "bidirectional"))
      (node (ref "U3") (pin "8") (pinfunction "P8_VCC_8") (pintype "bidirectional"))
      (node (ref "U5") (pin "2") (pinfunction "REF_2") (pintype "bidirectional"))
      (node (ref "U5") (pin "6") (pinfunction "VCC_6") (pintype "bidirectional"))
      (node (ref "U8") (pin "6") (pinfunction "VS_6") (pintype "power_in"))
    )
    (net (code "355") (name "V_REG") (class "Default")
      (node (ref "C4") (pin "1") (pinfunction "1_1") (pintype "passive"))
      (node (ref "DCDC3.3V") (pin "3") (pinfunction "3_3") (pintype "passive"))
      (node (ref "JP1") (pin "1") (pinfunction "1_1") (pintype "passive"))
      (node (ref "U6") (pin "P$4") (pinfunction "OUT_P$4") (pintype "bidirectional"))
      (node (ref "U6") (pin "P$5") (pinfunction "SENSE_P$5") (pintype "bidirectional"))
    )
    (net (code "356") (name "unconnected-(G1-+-Pad+@1)") (class "Default")
      (node (ref "G1") (pin "+@1") (pinfunction "+_+@1") (pintype "passive"))
    )
    (net (code "357") (name "unconnected-(JP1-Pad3)") (class "Default")
      (node (ref "JP1") (pin "3") (pinfunction "3_3") (pintype "passive"))
    )
    (net (code "358") (name "unconnected-(U8-BYPASS-Pad7)") (class "Default")
      (node (ref "U8") (pin "7") (pinfunction "BYPASS_7") (pintype "passive"))
    )
  )
)
